# Sheet1.net
KiCad netlist of a schematic drawn in Altium Designer
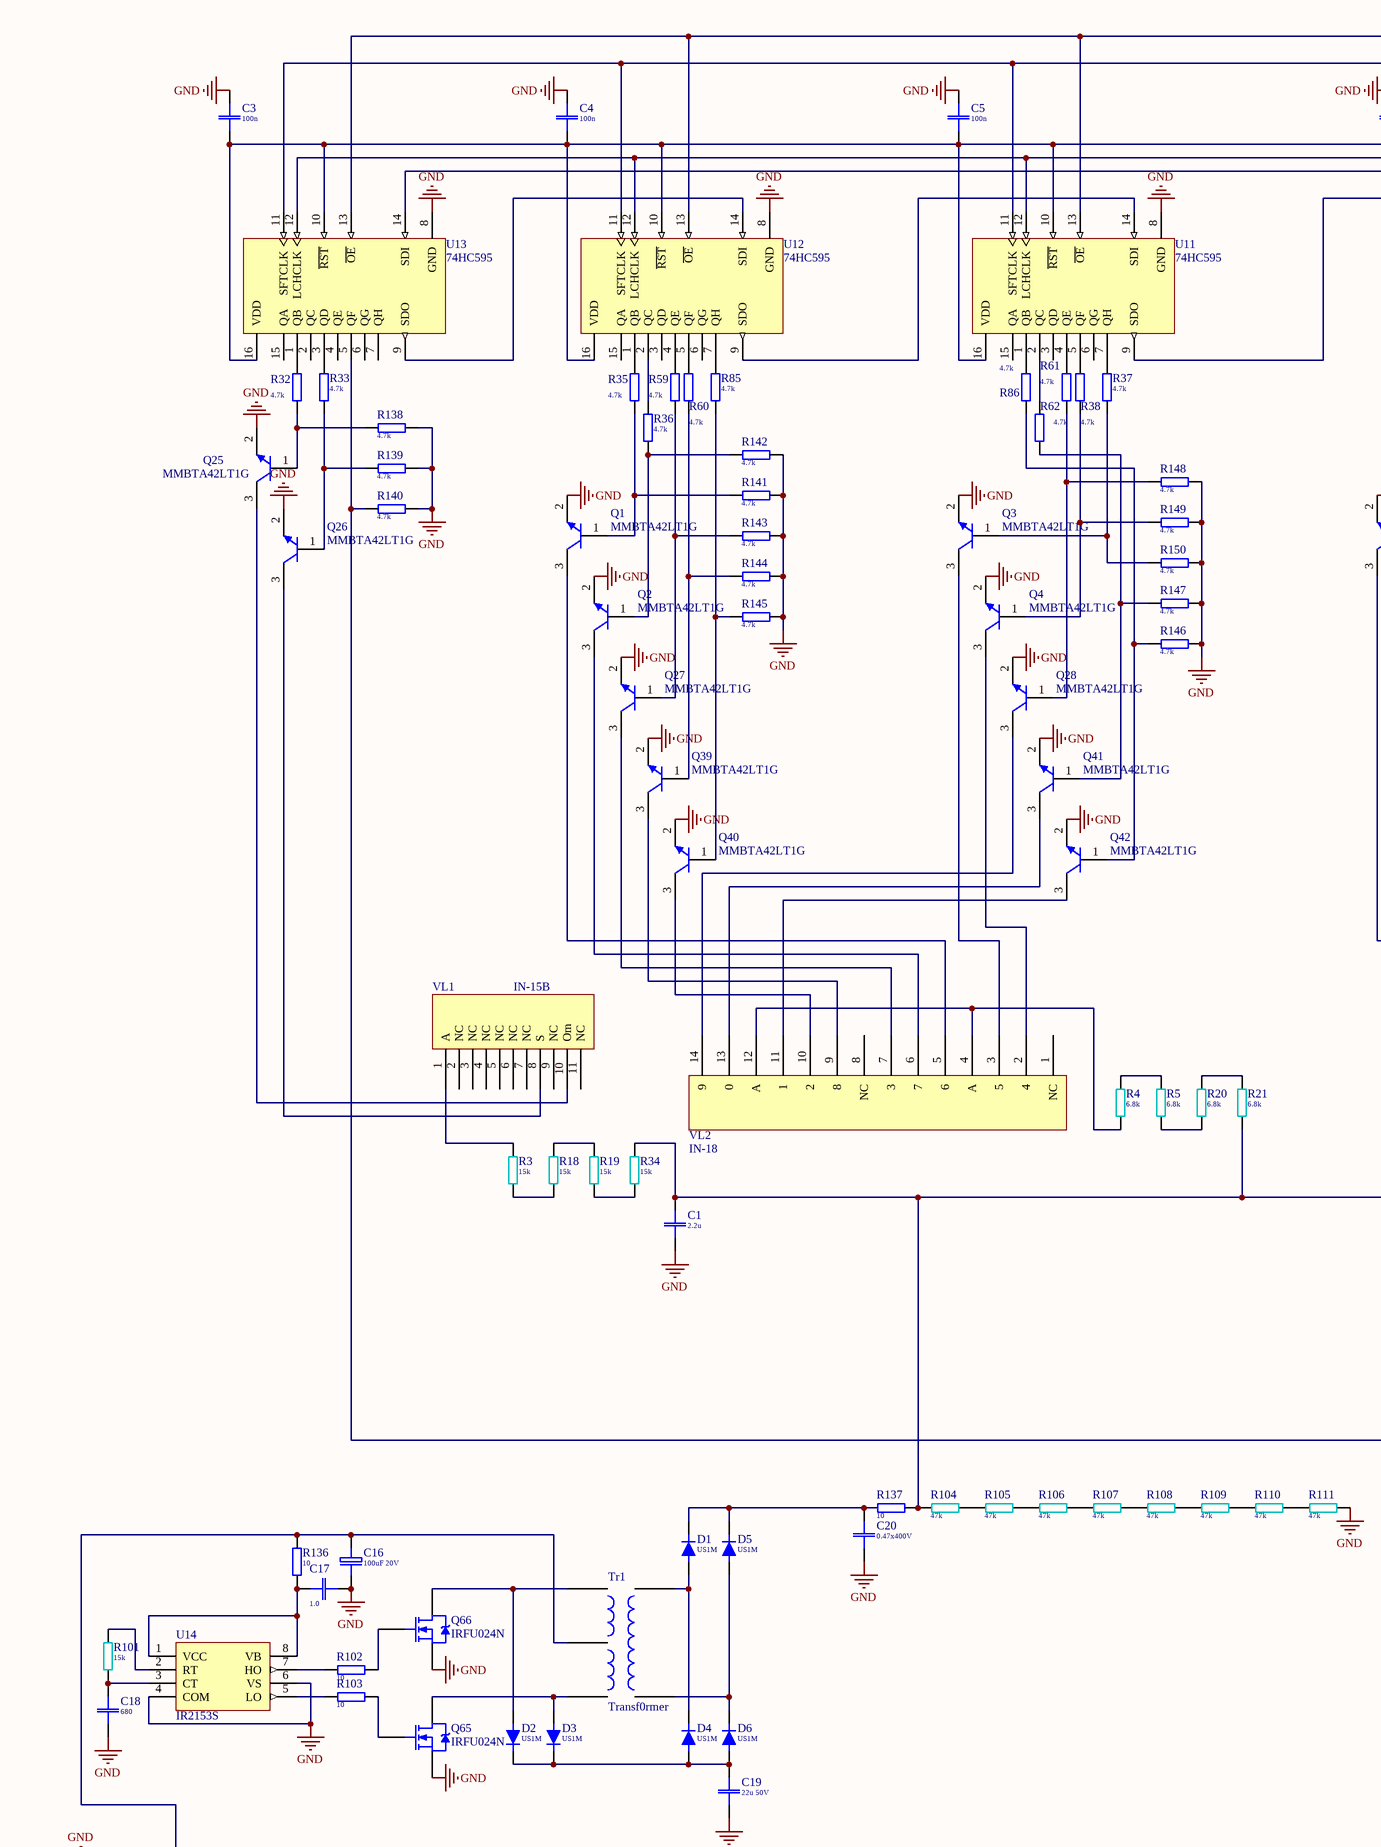
[diagram p0: Sheet1.SchDoc, top left]
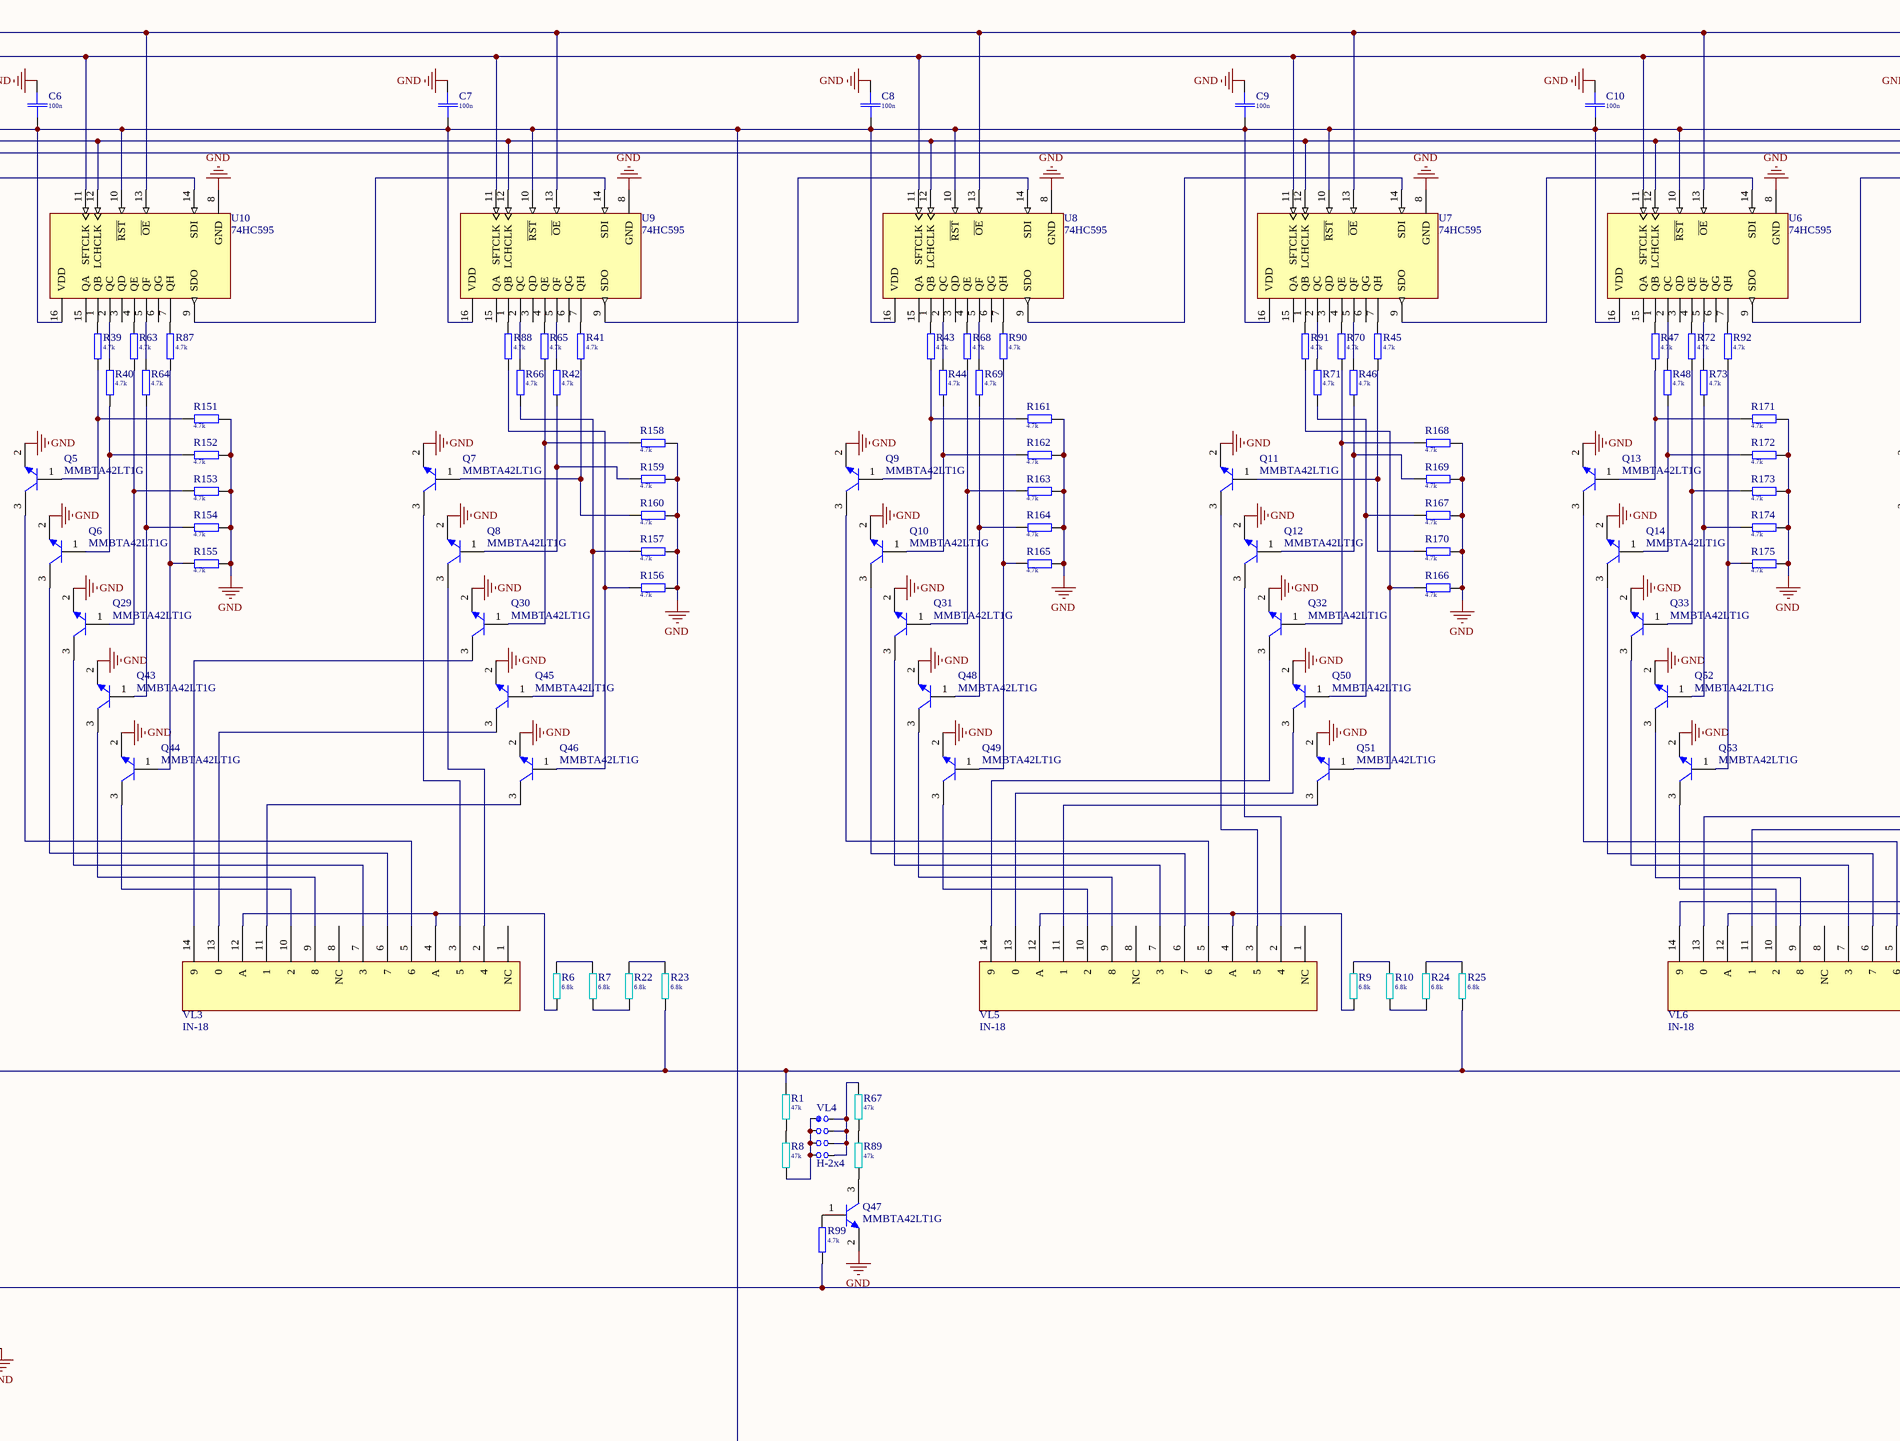
[diagram p1: Sheet1.SchDoc, top middle]
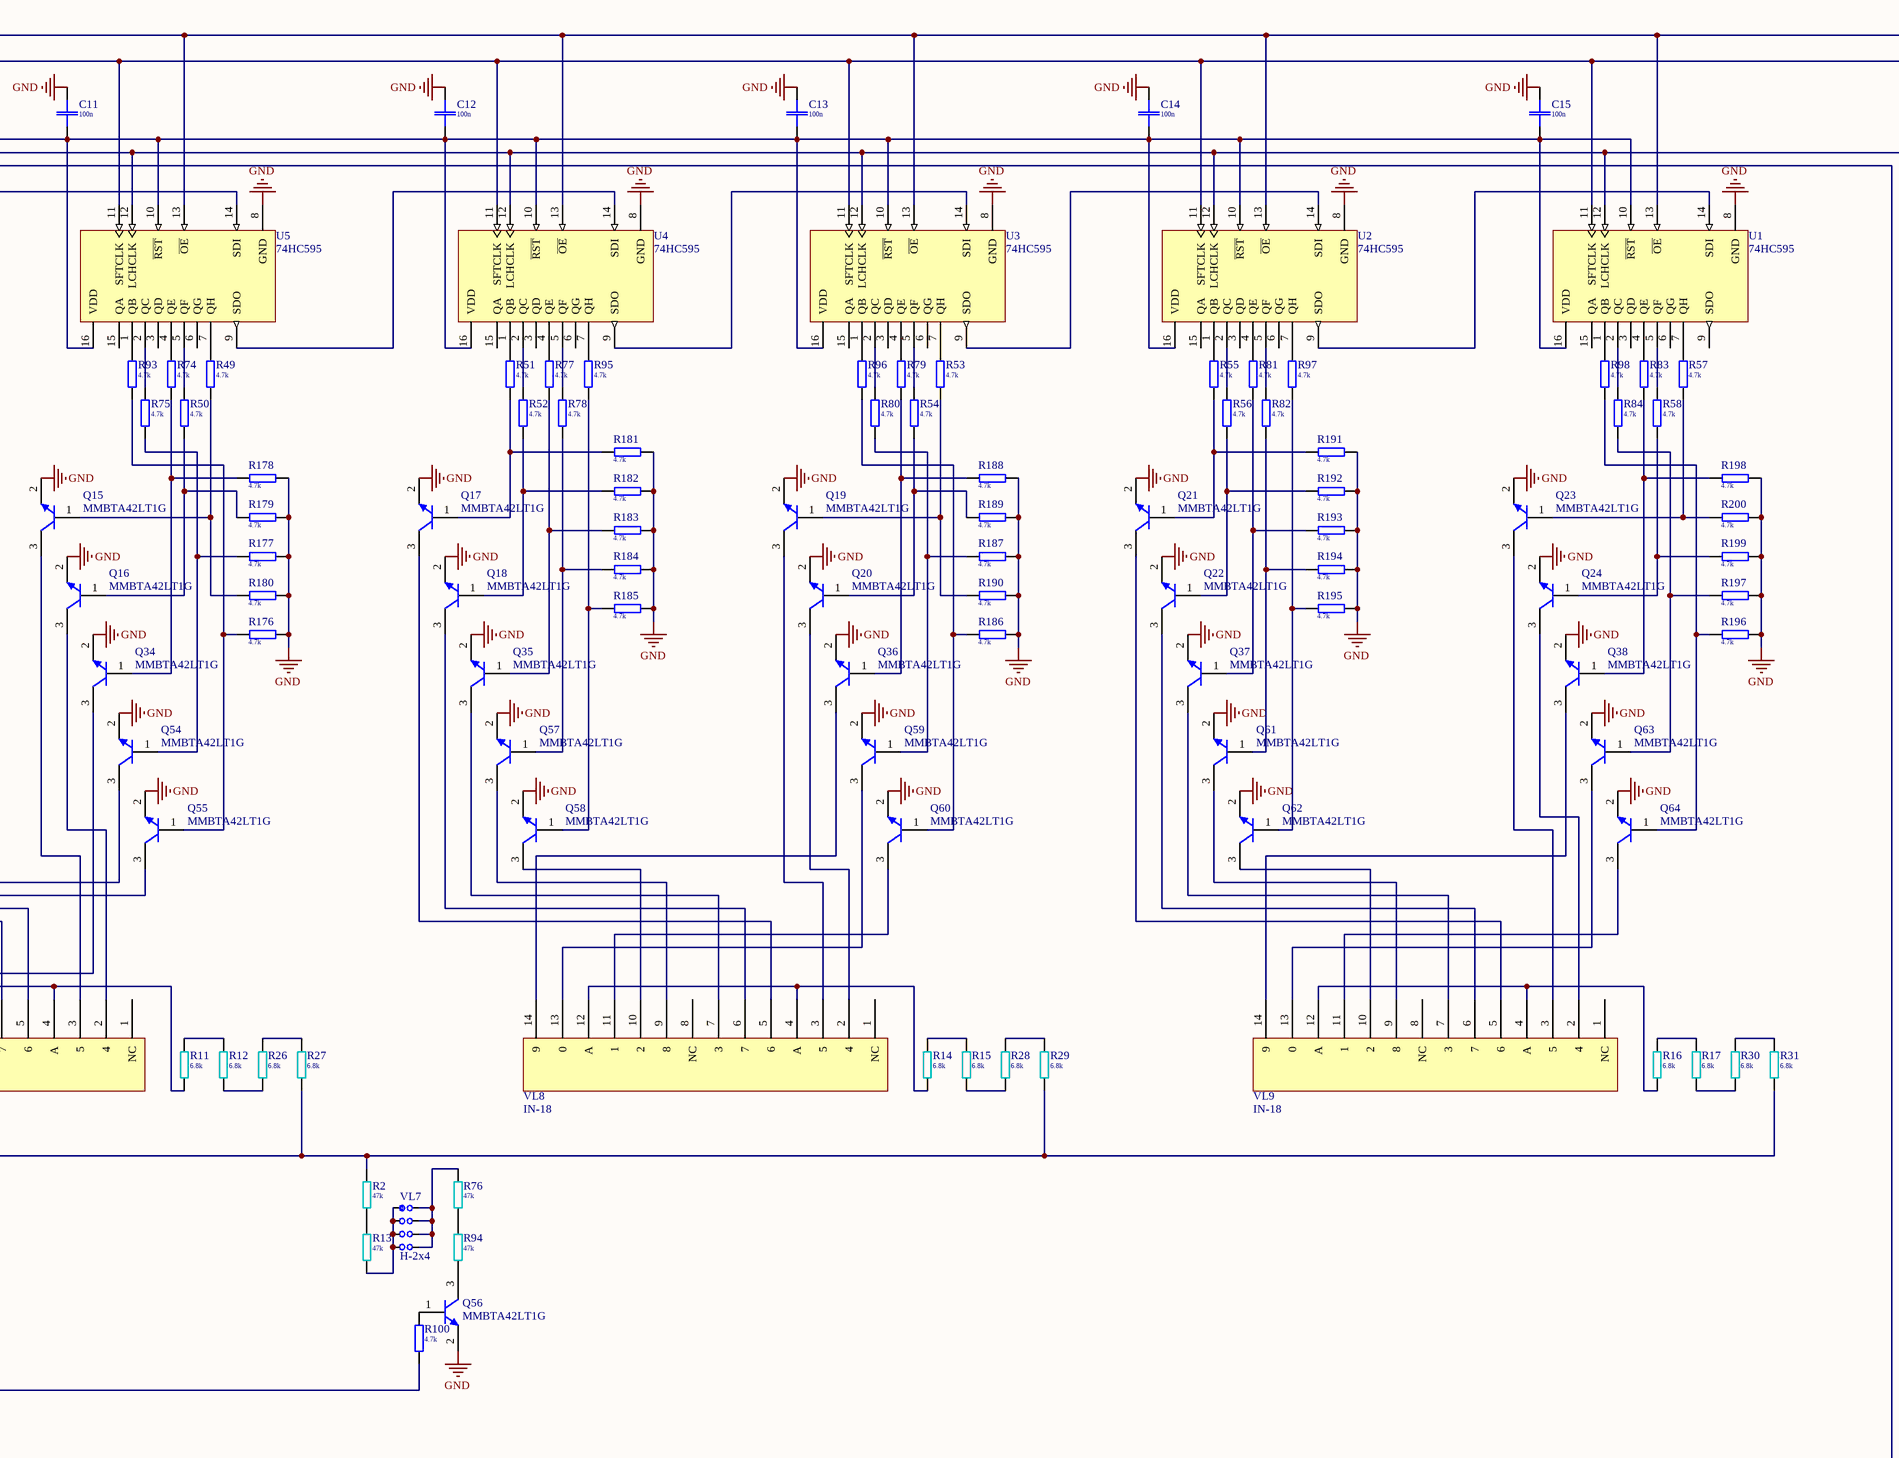
[diagram p2: Sheet1.SchDoc, top right]
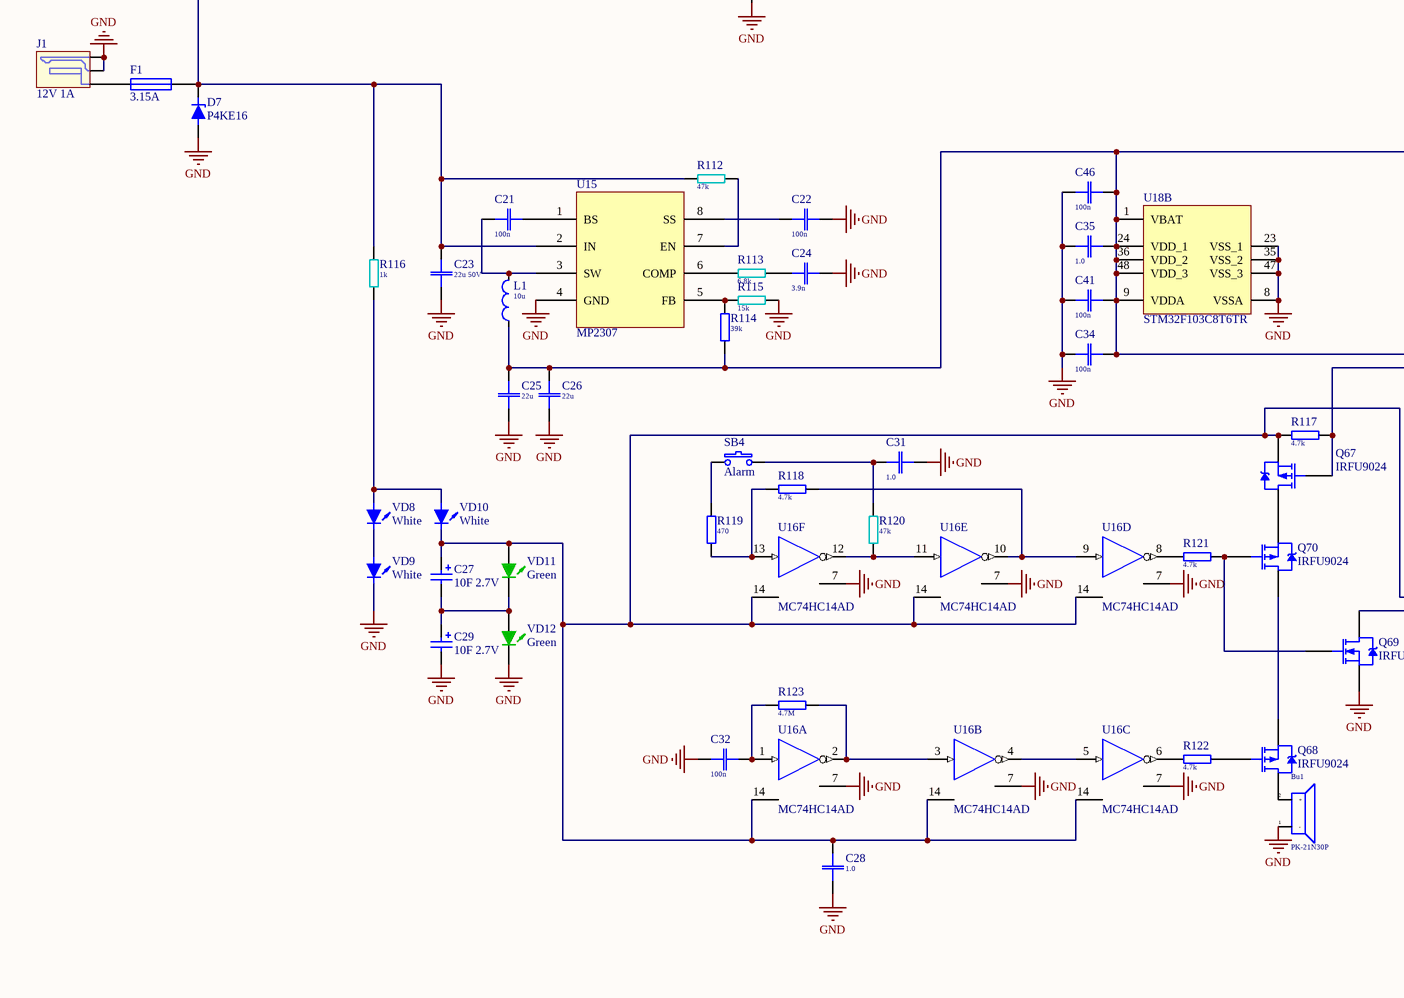
[diagram p3: Sheet1.SchDoc, bottom left]
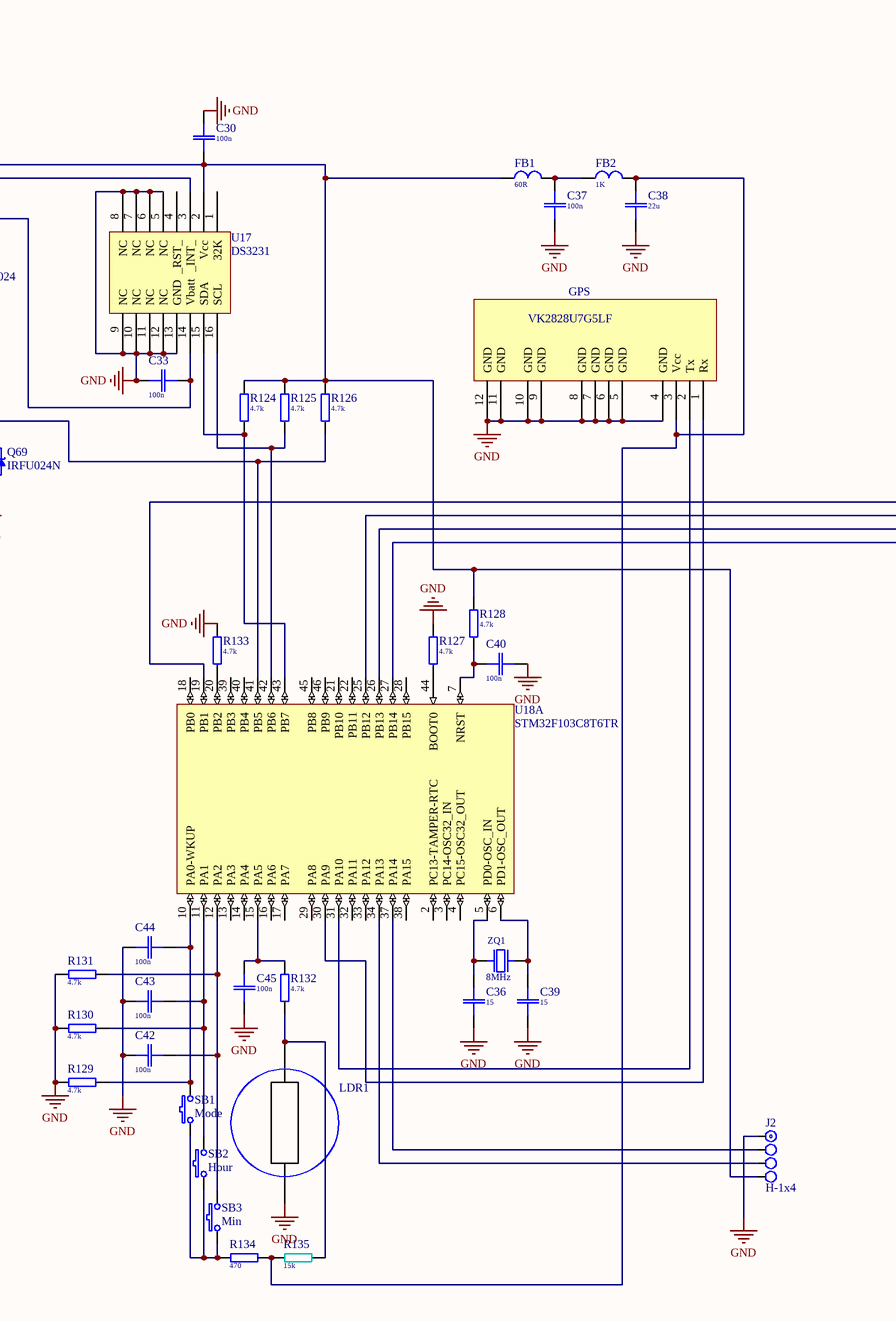
[diagram p4: Sheet1.SchDoc, bottom middle]

(export (version "E")
  (design (tool "Eeschema 10.0.6"))
  (components
    (comp (ref "Bu1")
      (value "PK-21N30P")
      (footprint "Buzzer")
      (libsource (lib "PCB_Project_4") (part "Buz PK-21N30P"))
    )
    (comp (ref "C1")
      (value "2.2u")
      (footprint "CBB22")
      (description "MER 1uF 250V")
      (libsource (lib "PCB_Project_2") (part "MER 1uF 250V"))
    )
    (comp (ref "C3")
      (value "100n")
      (footprint "C0805(2013)")
      (description "SMD-0805")
      (libsource (lib "SMD-RCL") (part "C-0805"))
    )
    (comp (ref "C4")
      (value "100n")
      (footprint "C0805(2013)")
      (description "SMD-0805")
      (libsource (lib "SMD-RCL") (part "C-0805"))
    )
    (comp (ref "C5")
      (value "100n")
      (footprint "C0805(2013)")
      (description "SMD-0805")
      (libsource (lib "SMD-RCL") (part "C-0805"))
    )
    (comp (ref "C6")
      (value "100n")
      (footprint "C0805(2013)")
      (description "SMD-0805")
      (libsource (lib "SMD-RCL") (part "C-0805"))
    )
    (comp (ref "C7")
      (value "100n")
      (footprint "C0805(2013)")
      (description "SMD-0805")
      (libsource (lib "SMD-RCL") (part "C-0805"))
    )
    (comp (ref "C8")
      (value "100n")
      (footprint "C0805(2013)")
      (description "SMD-0805")
      (libsource (lib "SMD-RCL") (part "C-0805"))
    )
    (comp (ref "C9")
      (value "100n")
      (footprint "C0805(2013)")
      (description "SMD-0805")
      (libsource (lib "SMD-RCL") (part "C-0805"))
    )
    (comp (ref "C10")
      (value "100n")
      (footprint "C0805(2013)")
      (description "SMD-0805")
      (libsource (lib "SMD-RCL") (part "C-0805"))
    )
    (comp (ref "C11")
      (value "100n")
      (footprint "C0805(2013)")
      (description "SMD-0805")
      (libsource (lib "SMD-RCL") (part "C-0805"))
    )
    (comp (ref "C12")
      (value "100n")
      (footprint "C0805(2013)")
      (description "SMD-0805")
      (libsource (lib "SMD-RCL") (part "C-0805"))
    )
    (comp (ref "C13")
      (value "100n")
      (footprint "C0805(2013)")
      (description "SMD-0805")
      (libsource (lib "SMD-RCL") (part "C-0805"))
    )
    (comp (ref "C14")
      (value "100n")
      (footprint "C0805(2013)")
      (description "SMD-0805")
      (libsource (lib "SMD-RCL") (part "C-0805"))
    )
    (comp (ref "C15")
      (value "100n")
      (footprint "C0805(2013)")
      (description "SMD-0805")
      (libsource (lib "SMD-RCL") (part "C-0805"))
    )
    (comp (ref "C16")
      (value "100uF 20V")
      (footprint "100.0x20V pol")
      (description "400V 105F")
      (libsource (lib "Cap-El") (part "1u-400V-105F"))
    )
    (comp (ref "C17")
      (value "1.0")
      (footprint "C0805(2013)")
      (description "SMD-0805")
      (libsource (lib "SMD-RCL") (part "C-0805"))
    )
    (comp (ref "C18")
      (value "680")
      (footprint "C0805(2013)")
      (description "SMD-0805")
      (libsource (lib "SMD-RCL") (part "C-0805"))
    )
    (comp (ref "C19")
      (value "22u 50V")
      (footprint "C1210(3225)")
      (description "SMD-1210 100V X7R 10%")
      (libsource (lib "SMD-RCL") (part "C-1210  100V 2.2u"))
    )
    (comp (ref "C20")
      (value "0.47x400V")
      (footprint "MKP 18x7 h14 R15.24")
      (description "MKS4 3.3u 63V")
      (fields (field (name "Comment") "3,3u"))
      (libsource (lib "Cap") (part "MKS4 3.3u 63V"))
    )
    (comp (ref "C21")
      (value "100n")
      (footprint "C0805(2013)")
      (description "SMD-0805")
      (libsource (lib "SMD-RCL") (part "C-0805"))
    )
    (comp (ref "C22")
      (value "100n")
      (footprint "C0805(2013)")
      (description "SMD-0805")
      (libsource (lib "SMD-RCL") (part "C-0805"))
    )
    (comp (ref "C23")
      (value "22u 50V")
      (footprint "C1210(3225)")
      (description "SMD-1210 100V X7R 10%")
      (libsource (lib "SMD-RCL") (part "C-1210  100V 2.2u"))
    )
    (comp (ref "C24")
      (value "3.9n")
      (footprint "C0805(2013)")
      (description "SMD-0805")
      (libsource (lib "SMD-RCL") (part "C-0805"))
    )
    (comp (ref "C25")
      (value "22u")
      (footprint "C1210(3225)")
      (description "SMD-1210 100V X7R 10%")
      (libsource (lib "SMD-RCL") (part "C-1210  100V 2.2u"))
    )
    (comp (ref "C26")
      (value "22u")
      (footprint "C1210(3225)")
      (description "SMD-1210 100V X7R 10%")
      (libsource (lib "SMD-RCL") (part "C-1210  100V 2.2u"))
    )
    (comp (ref "C27")
      (value "10F 2.7V")
      (footprint "10F2.7V")
      (description "Polarized Capacitor (Axial)")
      (fields (field (name "Comment") "Cap Pol2") (field (name "PUBLISHER") "Altium Limited"))
      (libsource (lib "Miscellaneous Devices") (part "Cap Pol2"))
    )
    (comp (ref "C28")
      (value "1.0")
      (footprint "C0805(2013)")
      (description "SMD-0805")
      (libsource (lib "SMD-RCL") (part "C-0805"))
    )
    (comp (ref "C29")
      (value "10F 2.7V")
      (footprint "10F2.7V")
      (description "Polarized Capacitor (Axial)")
      (fields (field (name "Comment") "Cap Pol2") (field (name "PUBLISHER") "Altium Limited"))
      (libsource (lib "Miscellaneous Devices") (part "Cap Pol2"))
    )
    (comp (ref "C30")
      (value "100n")
      (footprint "C0805(2013)")
      (description "SMD-0805")
      (libsource (lib "SMD-RCL") (part "C-0805"))
    )
    (comp (ref "C31")
      (value "1.0")
      (footprint "C0805(2013)")
      (description "SMD-0805")
      (libsource (lib "SMD-RCL") (part "C-0805"))
    )
    (comp (ref "C32")
      (value "100n")
      (footprint "C0805(2013)")
      (description "SMD-0805")
      (libsource (lib "SMD-RCL") (part "C-0805"))
    )
    (comp (ref "C33")
      (value "100n")
      (footprint "C0805(2013)")
      (description "SMD-0805")
      (libsource (lib "SMD-RCL") (part "C-0805"))
    )
    (comp (ref "C34")
      (value "100n")
      (footprint "C0805(2013)")
      (description "SMD-0805")
      (libsource (lib "SMD-RCL") (part "C-0805"))
    )
    (comp (ref "C35")
      (value "1.0")
      (footprint "C0805(2013)")
      (description "SMD-0805")
      (libsource (lib "SMD-RCL") (part "C-0805"))
    )
    (comp (ref "C36")
      (value "15")
      (footprint "C0805(2013)")
      (description "SMD-0805")
      (libsource (lib "SMD-RCL") (part "C-0805"))
    )
    (comp (ref "C37")
      (value "100n")
      (footprint "C0805(2013)")
      (description "SMD-0805")
      (libsource (lib "SMD-RCL") (part "C-0805"))
    )
    (comp (ref "C38")
      (value "22u")
      (footprint "C1210(3225)")
      (description "SMD-1210 100V X7R 10%")
      (libsource (lib "SMD-RCL") (part "C-1210  100V 2.2u"))
    )
    (comp (ref "C39")
      (value "15")
      (footprint "C0805(2013)")
      (description "SMD-0805")
      (libsource (lib "SMD-RCL") (part "C-0805"))
    )
    (comp (ref "C40")
      (value "100n")
      (footprint "C0805(2013)")
      (description "SMD-0805")
      (libsource (lib "SMD-RCL") (part "C-0805"))
    )
    (comp (ref "C41")
      (value "100n")
      (footprint "C0805(2013)")
      (description "SMD-0805")
      (libsource (lib "SMD-RCL") (part "C-0805"))
    )
    (comp (ref "C42")
      (value "100n")
      (footprint "C0805(2013)")
      (description "SMD-0805")
      (libsource (lib "SMD-RCL") (part "C-0805"))
    )
    (comp (ref "C43")
      (value "100n")
      (footprint "C0805(2013)")
      (description "SMD-0805")
      (libsource (lib "SMD-RCL") (part "C-0805"))
    )
    (comp (ref "C44")
      (value "100n")
      (footprint "C0805(2013)")
      (description "SMD-0805")
      (libsource (lib "SMD-RCL") (part "C-0805"))
    )
    (comp (ref "C45")
      (value "100n")
      (footprint "C0805(2013)")
      (description "SMD-0805")
      (libsource (lib "SMD-RCL") (part "C-0805"))
    )
    (comp (ref "C46")
      (value "100n")
      (footprint "C0805(2013)")
      (description "SMD-0805")
      (libsource (lib "SMD-RCL") (part "C-0805"))
    )
    (comp (ref "D1")
      (value "US1M")
      (footprint "DO-214AC (SMA)")
      (description "SMD SMA 1A 1000V 75nS")
      (libsource (lib "Diodes-Power") (part "US1M"))
    )
    (comp (ref "D2")
      (value "US1M")
      (footprint "DO-214AC (SMA)")
      (description "SMD SMA 1A 1000V 75nS")
      (libsource (lib "Diodes-Power") (part "US1M"))
    )
    (comp (ref "D3")
      (value "US1M")
      (footprint "DO-214AC (SMA)")
      (description "SMD SMA 1A 1000V 75nS")
      (libsource (lib "Diodes-Power") (part "US1M"))
    )
    (comp (ref "D4")
      (value "US1M")
      (footprint "DO-214AC (SMA)")
      (description "SMD SMA 1A 1000V 75nS")
      (libsource (lib "Diodes-Power") (part "US1M"))
    )
    (comp (ref "D5")
      (value "US1M")
      (footprint "DO-214AC (SMA)")
      (description "SMD SMA 1A 1000V 75nS")
      (libsource (lib "Diodes-Power") (part "US1M"))
    )
    (comp (ref "D6")
      (value "US1M")
      (footprint "DO-214AC (SMA)")
      (description "SMD SMA 1A 1000V 75nS")
      (libsource (lib "Diodes-Power") (part "US1M"))
    )
    (comp (ref "D7")
      (value "P4KE16")
      (footprint "DO-15-400")
      (description "TVS DO-15 600W 200V")
      (libsource (lib "Diodes") (part "P6KE200"))
    )
    (comp (ref "F1")
      (value "3.15A")
      (footprint "PIN-W2/E2.8")
      (description "Fuse")
      (fields (field (name "PUBLISHER") "Altium Limited"))
      (libsource (lib "Miscellaneous Devices") (part "Fuse 1"))
    )
    (comp (ref "FB1") (value "60R") (footprint "C1206") (libsource (lib "SMD-RCL") (part "L2")))
    (comp (ref "FB2") (value "1K") (footprint "C1206") (libsource (lib "SMD-RCL") (part "L2")))
    (comp (ref "GPS")
      (value "VK2828U7G5LF")
      (footprint "GPSmodule")
      (description "Amt02 GPS antenna")
      (libsource (lib "PCB_Project_4") (part "GPS_ant"))
    )
    (comp (ref "J1")
      (value "12V 1A")
      (footprint "Power-Jack")
      (description "Power-Jack")
      (libsource (lib "Connektor") (part "Power-Jack"))
    )
    (comp (ref "J2") (value "H-1x4") (footprint "J1x4") (libsource (lib "Connektor") (part "H-1x4")))
    (comp (ref "L1")
      (value "10u")
      (footprint "Dr-SD-75")
      (description "1.2A 0.15om 7.3x7.3x5mm")
      (libsource (lib "SMD-RCL") (part "L-SD-75 33uH"))
    )
    (comp (ref "LDR1")
      (value "LDR")
      (footprint "CAPPR250-630X1120")
      (libsource (lib "PCB_Project_2") (part "LDR"))
    )
    (comp (ref "Q1")
      (value "MMBTA42LT1G")
      (footprint "ONSC-SOT-23-3-318-08_V")
      (description "High Voltage Transistor, NPN Silicon, 3-Pin SOT-23, Pb-Free, Tape and Reel")
      (fields (field (name "MANUFACTURER") "On Semiconductor"))
      (libsource (lib "ON Semi General Purpose Transistors") (part "MMBTA42LT1G"))
    )
    (comp (ref "Q2")
      (value "MMBTA42LT1G")
      (footprint "ONSC-SOT-23-3-318-08_V")
      (description "High Voltage Transistor, NPN Silicon, 3-Pin SOT-23, Pb-Free, Tape and Reel")
      (fields (field (name "MANUFACTURER") "On Semiconductor"))
      (libsource (lib "ON Semi General Purpose Transistors") (part "MMBTA42LT1G"))
    )
    (comp (ref "Q3")
      (value "MMBTA42LT1G")
      (footprint "ONSC-SOT-23-3-318-08_V")
      (description "High Voltage Transistor, NPN Silicon, 3-Pin SOT-23, Pb-Free, Tape and Reel")
      (fields (field (name "MANUFACTURER") "On Semiconductor"))
      (libsource (lib "ON Semi General Purpose Transistors") (part "MMBTA42LT1G"))
    )
    (comp (ref "Q4")
      (value "MMBTA42LT1G")
      (footprint "ONSC-SOT-23-3-318-08_V")
      (description "High Voltage Transistor, NPN Silicon, 3-Pin SOT-23, Pb-Free, Tape and Reel")
      (fields (field (name "MANUFACTURER") "On Semiconductor"))
      (libsource (lib "ON Semi General Purpose Transistors") (part "MMBTA42LT1G"))
    )
    (comp (ref "Q5")
      (value "MMBTA42LT1G")
      (footprint "ONSC-SOT-23-3-318-08_V")
      (description "High Voltage Transistor, NPN Silicon, 3-Pin SOT-23, Pb-Free, Tape and Reel")
      (fields (field (name "MANUFACTURER") "On Semiconductor"))
      (libsource (lib "ON Semi General Purpose Transistors") (part "MMBTA42LT1G"))
    )
    (comp (ref "Q6")
      (value "MMBTA42LT1G")
      (footprint "ONSC-SOT-23-3-318-08_V")
      (description "High Voltage Transistor, NPN Silicon, 3-Pin SOT-23, Pb-Free, Tape and Reel")
      (fields (field (name "MANUFACTURER") "On Semiconductor"))
      (libsource (lib "ON Semi General Purpose Transistors") (part "MMBTA42LT1G"))
    )
    (comp (ref "Q7")
      (value "MMBTA42LT1G")
      (footprint "ONSC-SOT-23-3-318-08_V")
      (description "High Voltage Transistor, NPN Silicon, 3-Pin SOT-23, Pb-Free, Tape and Reel")
      (fields (field (name "MANUFACTURER") "On Semiconductor"))
      (libsource (lib "ON Semi General Purpose Transistors") (part "MMBTA42LT1G"))
    )
    (comp (ref "Q8")
      (value "MMBTA42LT1G")
      (footprint "ONSC-SOT-23-3-318-08_V")
      (description "High Voltage Transistor, NPN Silicon, 3-Pin SOT-23, Pb-Free, Tape and Reel")
      (fields (field (name "MANUFACTURER") "On Semiconductor"))
      (libsource (lib "ON Semi General Purpose Transistors") (part "MMBTA42LT1G"))
    )
    (comp (ref "Q9")
      (value "MMBTA42LT1G")
      (footprint "ONSC-SOT-23-3-318-08_V")
      (description "High Voltage Transistor, NPN Silicon, 3-Pin SOT-23, Pb-Free, Tape and Reel")
      (fields (field (name "MANUFACTURER") "On Semiconductor"))
      (libsource (lib "ON Semi General Purpose Transistors") (part "MMBTA42LT1G"))
    )
    (comp (ref "Q10")
      (value "MMBTA42LT1G")
      (footprint "ONSC-SOT-23-3-318-08_V")
      (description "High Voltage Transistor, NPN Silicon, 3-Pin SOT-23, Pb-Free, Tape and Reel")
      (fields (field (name "MANUFACTURER") "On Semiconductor"))
      (libsource (lib "ON Semi General Purpose Transistors") (part "MMBTA42LT1G"))
    )
    (comp (ref "Q11")
      (value "MMBTA42LT1G")
      (footprint "ONSC-SOT-23-3-318-08_V")
      (description "High Voltage Transistor, NPN Silicon, 3-Pin SOT-23, Pb-Free, Tape and Reel")
      (fields (field (name "MANUFACTURER") "On Semiconductor"))
      (libsource (lib "ON Semi General Purpose Transistors") (part "MMBTA42LT1G"))
    )
    (comp (ref "Q12")
      (value "MMBTA42LT1G")
      (footprint "ONSC-SOT-23-3-318-08_V")
      (description "High Voltage Transistor, NPN Silicon, 3-Pin SOT-23, Pb-Free, Tape and Reel")
      (fields (field (name "MANUFACTURER") "On Semiconductor"))
      (libsource (lib "ON Semi General Purpose Transistors") (part "MMBTA42LT1G"))
    )
    (comp (ref "Q13")
      (value "MMBTA42LT1G")
      (footprint "ONSC-SOT-23-3-318-08_V")
      (description "High Voltage Transistor, NPN Silicon, 3-Pin SOT-23, Pb-Free, Tape and Reel")
      (fields (field (name "MANUFACTURER") "On Semiconductor"))
      (libsource (lib "ON Semi General Purpose Transistors") (part "MMBTA42LT1G"))
    )
    (comp (ref "Q14")
      (value "MMBTA42LT1G")
      (footprint "ONSC-SOT-23-3-318-08_V")
      (description "High Voltage Transistor, NPN Silicon, 3-Pin SOT-23, Pb-Free, Tape and Reel")
      (fields (field (name "MANUFACTURER") "On Semiconductor"))
      (libsource (lib "ON Semi General Purpose Transistors") (part "MMBTA42LT1G"))
    )
    (comp (ref "Q15")
      (value "MMBTA42LT1G")
      (footprint "ONSC-SOT-23-3-318-08_V")
      (description "High Voltage Transistor, NPN Silicon, 3-Pin SOT-23, Pb-Free, Tape and Reel")
      (fields (field (name "MANUFACTURER") "On Semiconductor"))
      (libsource (lib "ON Semi General Purpose Transistors") (part "MMBTA42LT1G"))
    )
    (comp (ref "Q16")
      (value "MMBTA42LT1G")
      (footprint "ONSC-SOT-23-3-318-08_V")
      (description "High Voltage Transistor, NPN Silicon, 3-Pin SOT-23, Pb-Free, Tape and Reel")
      (fields (field (name "MANUFACTURER") "On Semiconductor"))
      (libsource (lib "ON Semi General Purpose Transistors") (part "MMBTA42LT1G"))
    )
    (comp (ref "Q17")
      (value "MMBTA42LT1G")
      (footprint "ONSC-SOT-23-3-318-08_V")
      (description "High Voltage Transistor, NPN Silicon, 3-Pin SOT-23, Pb-Free, Tape and Reel")
      (fields (field (name "MANUFACTURER") "On Semiconductor"))
      (libsource (lib "ON Semi General Purpose Transistors") (part "MMBTA42LT1G"))
    )
    (comp (ref "Q18")
      (value "MMBTA42LT1G")
      (footprint "ONSC-SOT-23-3-318-08_V")
      (description "High Voltage Transistor, NPN Silicon, 3-Pin SOT-23, Pb-Free, Tape and Reel")
      (fields (field (name "MANUFACTURER") "On Semiconductor"))
      (libsource (lib "ON Semi General Purpose Transistors") (part "MMBTA42LT1G"))
    )
    (comp (ref "Q19")
      (value "MMBTA42LT1G")
      (footprint "ONSC-SOT-23-3-318-08_V")
      (description "High Voltage Transistor, NPN Silicon, 3-Pin SOT-23, Pb-Free, Tape and Reel")
      (fields (field (name "MANUFACTURER") "On Semiconductor"))
      (libsource (lib "ON Semi General Purpose Transistors") (part "MMBTA42LT1G"))
    )
    (comp (ref "Q20")
      (value "MMBTA42LT1G")
      (footprint "ONSC-SOT-23-3-318-08_V")
      (description "High Voltage Transistor, NPN Silicon, 3-Pin SOT-23, Pb-Free, Tape and Reel")
      (fields (field (name "MANUFACTURER") "On Semiconductor"))
      (libsource (lib "ON Semi General Purpose Transistors") (part "MMBTA42LT1G"))
    )
    (comp (ref "Q21")
      (value "MMBTA42LT1G")
      (footprint "ONSC-SOT-23-3-318-08_V")
      (description "High Voltage Transistor, NPN Silicon, 3-Pin SOT-23, Pb-Free, Tape and Reel")
      (fields (field (name "MANUFACTURER") "On Semiconductor"))
      (libsource (lib "ON Semi General Purpose Transistors") (part "MMBTA42LT1G"))
    )
    (comp (ref "Q22")
      (value "MMBTA42LT1G")
      (footprint "ONSC-SOT-23-3-318-08_V")
      (description "High Voltage Transistor, NPN Silicon, 3-Pin SOT-23, Pb-Free, Tape and Reel")
      (fields (field (name "MANUFACTURER") "On Semiconductor"))
      (libsource (lib "ON Semi General Purpose Transistors") (part "MMBTA42LT1G"))
    )
    (comp (ref "Q23")
      (value "MMBTA42LT1G")
      (footprint "ONSC-SOT-23-3-318-08_V")
      (description "High Voltage Transistor, NPN Silicon, 3-Pin SOT-23, Pb-Free, Tape and Reel")
      (fields (field (name "MANUFACTURER") "On Semiconductor"))
      (libsource (lib "ON Semi General Purpose Transistors") (part "MMBTA42LT1G"))
    )
    (comp (ref "Q24")
      (value "MMBTA42LT1G")
      (footprint "ONSC-SOT-23-3-318-08_V")
      (description "High Voltage Transistor, NPN Silicon, 3-Pin SOT-23, Pb-Free, Tape and Reel")
      (fields (field (name "MANUFACTURER") "On Semiconductor"))
      (libsource (lib "ON Semi General Purpose Transistors") (part "MMBTA42LT1G"))
    )
    (comp (ref "Q25")
      (value "MMBTA42LT1G")
      (footprint "ONSC-SOT-23-3-318-08_V")
      (description "High Voltage Transistor, NPN Silicon, 3-Pin SOT-23, Pb-Free, Tape and Reel")
      (fields (field (name "MANUFACTURER") "On Semiconductor"))
      (libsource (lib "ON Semi General Purpose Transistors") (part "MMBTA42LT1G"))
    )
    (comp (ref "Q26")
      (value "MMBTA42LT1G")
      (footprint "ONSC-SOT-23-3-318-08_V")
      (description "High Voltage Transistor, NPN Silicon, 3-Pin SOT-23, Pb-Free, Tape and Reel")
      (fields (field (name "MANUFACTURER") "On Semiconductor"))
      (libsource (lib "ON Semi General Purpose Transistors") (part "MMBTA42LT1G"))
    )
    (comp (ref "Q27")
      (value "MMBTA42LT1G")
      (footprint "ONSC-SOT-23-3-318-08_V")
      (description "High Voltage Transistor, NPN Silicon, 3-Pin SOT-23, Pb-Free, Tape and Reel")
      (fields (field (name "MANUFACTURER") "On Semiconductor"))
      (libsource (lib "ON Semi General Purpose Transistors") (part "MMBTA42LT1G"))
    )
    (comp (ref "Q28")
      (value "MMBTA42LT1G")
      (footprint "ONSC-SOT-23-3-318-08_V")
      (description "High Voltage Transistor, NPN Silicon, 3-Pin SOT-23, Pb-Free, Tape and Reel")
      (fields (field (name "MANUFACTURER") "On Semiconductor"))
      (libsource (lib "ON Semi General Purpose Transistors") (part "MMBTA42LT1G"))
    )
    (comp (ref "Q29")
      (value "MMBTA42LT1G")
      (footprint "ONSC-SOT-23-3-318-08_V")
      (description "High Voltage Transistor, NPN Silicon, 3-Pin SOT-23, Pb-Free, Tape and Reel")
      (fields (field (name "MANUFACTURER") "On Semiconductor"))
      (libsource (lib "ON Semi General Purpose Transistors") (part "MMBTA42LT1G"))
    )
    (comp (ref "Q30")
      (value "MMBTA42LT1G")
      (footprint "ONSC-SOT-23-3-318-08_V")
      (description "High Voltage Transistor, NPN Silicon, 3-Pin SOT-23, Pb-Free, Tape and Reel")
      (fields (field (name "MANUFACTURER") "On Semiconductor"))
      (libsource (lib "ON Semi General Purpose Transistors") (part "MMBTA42LT1G"))
    )
    (comp (ref "Q31")
      (value "MMBTA42LT1G")
      (footprint "ONSC-SOT-23-3-318-08_V")
      (description "High Voltage Transistor, NPN Silicon, 3-Pin SOT-23, Pb-Free, Tape and Reel")
      (fields (field (name "MANUFACTURER") "On Semiconductor"))
      (libsource (lib "ON Semi General Purpose Transistors") (part "MMBTA42LT1G"))
    )
    (comp (ref "Q32")
      (value "MMBTA42LT1G")
      (footprint "ONSC-SOT-23-3-318-08_V")
      (description "High Voltage Transistor, NPN Silicon, 3-Pin SOT-23, Pb-Free, Tape and Reel")
      (fields (field (name "MANUFACTURER") "On Semiconductor"))
      (libsource (lib "ON Semi General Purpose Transistors") (part "MMBTA42LT1G"))
    )
    (comp (ref "Q33")
      (value "MMBTA42LT1G")
      (footprint "ONSC-SOT-23-3-318-08_V")
      (description "High Voltage Transistor, NPN Silicon, 3-Pin SOT-23, Pb-Free, Tape and Reel")
      (fields (field (name "MANUFACTURER") "On Semiconductor"))
      (libsource (lib "ON Semi General Purpose Transistors") (part "MMBTA42LT1G"))
    )
    (comp (ref "Q34")
      (value "MMBTA42LT1G")
      (footprint "ONSC-SOT-23-3-318-08_V")
      (description "High Voltage Transistor, NPN Silicon, 3-Pin SOT-23, Pb-Free, Tape and Reel")
      (fields (field (name "MANUFACTURER") "On Semiconductor"))
      (libsource (lib "ON Semi General Purpose Transistors") (part "MMBTA42LT1G"))
    )
    (comp (ref "Q35")
      (value "MMBTA42LT1G")
      (footprint "ONSC-SOT-23-3-318-08_V")
      (description "High Voltage Transistor, NPN Silicon, 3-Pin SOT-23, Pb-Free, Tape and Reel")
      (fields (field (name "MANUFACTURER") "On Semiconductor"))
      (libsource (lib "ON Semi General Purpose Transistors") (part "MMBTA42LT1G"))
    )
    (comp (ref "Q36")
      (value "MMBTA42LT1G")
      (footprint "ONSC-SOT-23-3-318-08_V")
      (description "High Voltage Transistor, NPN Silicon, 3-Pin SOT-23, Pb-Free, Tape and Reel")
      (fields (field (name "MANUFACTURER") "On Semiconductor"))
      (libsource (lib "ON Semi General Purpose Transistors") (part "MMBTA42LT1G"))
    )
    (comp (ref "Q37")
      (value "MMBTA42LT1G")
      (footprint "ONSC-SOT-23-3-318-08_V")
      (description "High Voltage Transistor, NPN Silicon, 3-Pin SOT-23, Pb-Free, Tape and Reel")
      (fields (field (name "MANUFACTURER") "On Semiconductor"))
      (libsource (lib "ON Semi General Purpose Transistors") (part "MMBTA42LT1G"))
    )
    (comp (ref "Q38")
      (value "MMBTA42LT1G")
      (footprint "ONSC-SOT-23-3-318-08_V")
      (description "High Voltage Transistor, NPN Silicon, 3-Pin SOT-23, Pb-Free, Tape and Reel")
      (fields (field (name "MANUFACTURER") "On Semiconductor"))
      (libsource (lib "ON Semi General Purpose Transistors") (part "MMBTA42LT1G"))
    )
    (comp (ref "Q39")
      (value "MMBTA42LT1G")
      (footprint "ONSC-SOT-23-3-318-08_V")
      (description "High Voltage Transistor, NPN Silicon, 3-Pin SOT-23, Pb-Free, Tape and Reel")
      (fields (field (name "MANUFACTURER") "On Semiconductor"))
      (libsource (lib "ON Semi General Purpose Transistors") (part "MMBTA42LT1G"))
    )
    (comp (ref "Q40")
      (value "MMBTA42LT1G")
      (footprint "ONSC-SOT-23-3-318-08_V")
      (description "High Voltage Transistor, NPN Silicon, 3-Pin SOT-23, Pb-Free, Tape and Reel")
      (fields (field (name "MANUFACTURER") "On Semiconductor"))
      (libsource (lib "ON Semi General Purpose Transistors") (part "MMBTA42LT1G"))
    )
    (comp (ref "Q41")
      (value "MMBTA42LT1G")
      (footprint "ONSC-SOT-23-3-318-08_V")
      (description "High Voltage Transistor, NPN Silicon, 3-Pin SOT-23, Pb-Free, Tape and Reel")
      (fields (field (name "MANUFACTURER") "On Semiconductor"))
      (libsource (lib "ON Semi General Purpose Transistors") (part "MMBTA42LT1G"))
    )
    (comp (ref "Q42")
      (value "MMBTA42LT1G")
      (footprint "ONSC-SOT-23-3-318-08_V")
      (description "High Voltage Transistor, NPN Silicon, 3-Pin SOT-23, Pb-Free, Tape and Reel")
      (fields (field (name "MANUFACTURER") "On Semiconductor"))
      (libsource (lib "ON Semi General Purpose Transistors") (part "MMBTA42LT1G"))
    )
    (comp (ref "Q43")
      (value "MMBTA42LT1G")
      (footprint "ONSC-SOT-23-3-318-08_V")
      (description "High Voltage Transistor, NPN Silicon, 3-Pin SOT-23, Pb-Free, Tape and Reel")
      (fields (field (name "MANUFACTURER") "On Semiconductor"))
      (libsource (lib "ON Semi General Purpose Transistors") (part "MMBTA42LT1G"))
    )
    (comp (ref "Q44")
      (value "MMBTA42LT1G")
      (footprint "ONSC-SOT-23-3-318-08_V")
      (description "High Voltage Transistor, NPN Silicon, 3-Pin SOT-23, Pb-Free, Tape and Reel")
      (fields (field (name "MANUFACTURER") "On Semiconductor"))
      (libsource (lib "ON Semi General Purpose Transistors") (part "MMBTA42LT1G"))
    )
    (comp (ref "Q45")
      (value "MMBTA42LT1G")
      (footprint "ONSC-SOT-23-3-318-08_V")
      (description "High Voltage Transistor, NPN Silicon, 3-Pin SOT-23, Pb-Free, Tape and Reel")
      (fields (field (name "MANUFACTURER") "On Semiconductor"))
      (libsource (lib "ON Semi General Purpose Transistors") (part "MMBTA42LT1G"))
    )
    (comp (ref "Q46")
      (value "MMBTA42LT1G")
      (footprint "ONSC-SOT-23-3-318-08_V")
      (description "High Voltage Transistor, NPN Silicon, 3-Pin SOT-23, Pb-Free, Tape and Reel")
      (fields (field (name "MANUFACTURER") "On Semiconductor"))
      (libsource (lib "ON Semi General Purpose Transistors") (part "MMBTA42LT1G"))
    )
    (comp (ref "Q47")
      (value "MMBTA42LT1G")
      (footprint "ONSC-SOT-23-3-318-08_V")
      (description "High Voltage Transistor, NPN Silicon, 3-Pin SOT-23, Pb-Free, Tape and Reel")
      (fields (field (name "MANUFACTURER") "On Semiconductor"))
      (libsource (lib "ON Semi General Purpose Transistors") (part "MMBTA42LT1G"))
    )
    (comp (ref "Q48")
      (value "MMBTA42LT1G")
      (footprint "ONSC-SOT-23-3-318-08_V")
      (description "High Voltage Transistor, NPN Silicon, 3-Pin SOT-23, Pb-Free, Tape and Reel")
      (fields (field (name "MANUFACTURER") "On Semiconductor"))
      (libsource (lib "ON Semi General Purpose Transistors") (part "MMBTA42LT1G"))
    )
    (comp (ref "Q49")
      (value "MMBTA42LT1G")
      (footprint "ONSC-SOT-23-3-318-08_V")
      (description "High Voltage Transistor, NPN Silicon, 3-Pin SOT-23, Pb-Free, Tape and Reel")
      (fields (field (name "MANUFACTURER") "On Semiconductor"))
      (libsource (lib "ON Semi General Purpose Transistors") (part "MMBTA42LT1G"))
    )
    (comp (ref "Q50")
      (value "MMBTA42LT1G")
      (footprint "ONSC-SOT-23-3-318-08_V")
      (description "High Voltage Transistor, NPN Silicon, 3-Pin SOT-23, Pb-Free, Tape and Reel")
      (fields (field (name "MANUFACTURER") "On Semiconductor"))
      (libsource (lib "ON Semi General Purpose Transistors") (part "MMBTA42LT1G"))
    )
    (comp (ref "Q51")
      (value "MMBTA42LT1G")
      (footprint "ONSC-SOT-23-3-318-08_V")
      (description "High Voltage Transistor, NPN Silicon, 3-Pin SOT-23, Pb-Free, Tape and Reel")
      (fields (field (name "MANUFACTURER") "On Semiconductor"))
      (libsource (lib "ON Semi General Purpose Transistors") (part "MMBTA42LT1G"))
    )
    (comp (ref "Q52")
      (value "MMBTA42LT1G")
      (footprint "ONSC-SOT-23-3-318-08_V")
      (description "High Voltage Transistor, NPN Silicon, 3-Pin SOT-23, Pb-Free, Tape and Reel")
      (fields (field (name "MANUFACTURER") "On Semiconductor"))
      (libsource (lib "ON Semi General Purpose Transistors") (part "MMBTA42LT1G"))
    )
    (comp (ref "Q53")
      (value "MMBTA42LT1G")
      (footprint "ONSC-SOT-23-3-318-08_V")
      (description "High Voltage Transistor, NPN Silicon, 3-Pin SOT-23, Pb-Free, Tape and Reel")
      (fields (field (name "MANUFACTURER") "On Semiconductor"))
      (libsource (lib "ON Semi General Purpose Transistors") (part "MMBTA42LT1G"))
    )
    (comp (ref "Q54")
      (value "MMBTA42LT1G")
      (footprint "ONSC-SOT-23-3-318-08_V")
      (description "High Voltage Transistor, NPN Silicon, 3-Pin SOT-23, Pb-Free, Tape and Reel")
      (fields (field (name "MANUFACTURER") "On Semiconductor"))
      (libsource (lib "ON Semi General Purpose Transistors") (part "MMBTA42LT1G"))
    )
    (comp (ref "Q55")
      (value "MMBTA42LT1G")
      (footprint "ONSC-SOT-23-3-318-08_V")
      (description "High Voltage Transistor, NPN Silicon, 3-Pin SOT-23, Pb-Free, Tape and Reel")
      (fields (field (name "MANUFACTURER") "On Semiconductor"))
      (libsource (lib "ON Semi General Purpose Transistors") (part "MMBTA42LT1G"))
    )
    (comp (ref "Q56")
      (value "MMBTA42LT1G")
      (footprint "ONSC-SOT-23-3-318-08_V")
      (description "High Voltage Transistor, NPN Silicon, 3-Pin SOT-23, Pb-Free, Tape and Reel")
      (fields (field (name "MANUFACTURER") "On Semiconductor"))
      (libsource (lib "ON Semi General Purpose Transistors") (part "MMBTA42LT1G"))
    )
    (comp (ref "Q57")
      (value "MMBTA42LT1G")
      (footprint "ONSC-SOT-23-3-318-08_V")
      (description "High Voltage Transistor, NPN Silicon, 3-Pin SOT-23, Pb-Free, Tape and Reel")
      (fields (field (name "MANUFACTURER") "On Semiconductor"))
      (libsource (lib "ON Semi General Purpose Transistors") (part "MMBTA42LT1G"))
    )
    (comp (ref "Q58")
      (value "MMBTA42LT1G")
      (footprint "ONSC-SOT-23-3-318-08_V")
      (description "High Voltage Transistor, NPN Silicon, 3-Pin SOT-23, Pb-Free, Tape and Reel")
      (fields (field (name "MANUFACTURER") "On Semiconductor"))
      (libsource (lib "ON Semi General Purpose Transistors") (part "MMBTA42LT1G"))
    )
    (comp (ref "Q59")
      (value "MMBTA42LT1G")
      (footprint "ONSC-SOT-23-3-318-08_V")
      (description "High Voltage Transistor, NPN Silicon, 3-Pin SOT-23, Pb-Free, Tape and Reel")
      (fields (field (name "MANUFACTURER") "On Semiconductor"))
      (libsource (lib "ON Semi General Purpose Transistors") (part "MMBTA42LT1G"))
    )
    (comp (ref "Q60")
      (value "MMBTA42LT1G")
      (footprint "ONSC-SOT-23-3-318-08_V")
      (description "High Voltage Transistor, NPN Silicon, 3-Pin SOT-23, Pb-Free, Tape and Reel")
      (fields (field (name "MANUFACTURER") "On Semiconductor"))
      (libsource (lib "ON Semi General Purpose Transistors") (part "MMBTA42LT1G"))
    )
    (comp (ref "Q61")
      (value "MMBTA42LT1G")
      (footprint "ONSC-SOT-23-3-318-08_V")
      (description "High Voltage Transistor, NPN Silicon, 3-Pin SOT-23, Pb-Free, Tape and Reel")
      (fields (field (name "MANUFACTURER") "On Semiconductor"))
      (libsource (lib "ON Semi General Purpose Transistors") (part "MMBTA42LT1G"))
    )
    (comp (ref "Q62")
      (value "MMBTA42LT1G")
      (footprint "ONSC-SOT-23-3-318-08_V")
      (description "High Voltage Transistor, NPN Silicon, 3-Pin SOT-23, Pb-Free, Tape and Reel")
      (fields (field (name "MANUFACTURER") "On Semiconductor"))
      (libsource (lib "ON Semi General Purpose Transistors") (part "MMBTA42LT1G"))
    )
    (comp (ref "Q63")
      (value "MMBTA42LT1G")
      (footprint "ONSC-SOT-23-3-318-08_V")
      (description "High Voltage Transistor, NPN Silicon, 3-Pin SOT-23, Pb-Free, Tape and Reel")
      (fields (field (name "MANUFACTURER") "On Semiconductor"))
      (libsource (lib "ON Semi General Purpose Transistors") (part "MMBTA42LT1G"))
    )
    (comp (ref "Q64")
      (value "MMBTA42LT1G")
      (footprint "ONSC-SOT-23-3-318-08_V")
      (description "High Voltage Transistor, NPN Silicon, 3-Pin SOT-23, Pb-Free, Tape and Reel")
      (fields (field (name "MANUFACTURER") "On Semiconductor"))
      (libsource (lib "ON Semi General Purpose Transistors") (part "MMBTA42LT1G"))
    )
    (comp (ref "Q65")
      (value "IRFU024N")
      (footprint "TO-251AA")
      (description "HEXFET Power MOSFET")
      (fields (field (name "PUBLISHER") "Altium Limited"))
      (libsource (lib "IR Discrete MOSFET - Power") (part "IRFU024N"))
    )
    (comp (ref "Q66")
      (value "IRFU024N")
      (footprint "TO-251AA")
      (description "HEXFET Power MOSFET")
      (fields (field (name "PUBLISHER") "Altium Limited"))
      (libsource (lib "IR Discrete MOSFET - Power") (part "IRFU024N"))
    )
    (comp (ref "Q67")
      (value "IRFU9024")
      (footprint "TO-251AA")
      (description "HEXFET Power MOSFET")
      (fields (field (name "PUBLISHER") "Altium Limited"))
      (libsource (lib "IR Discrete MOSFET - Power") (part "IRFU9024"))
    )
    (comp (ref "Q68")
      (value "IRFU9024")
      (footprint "TO-251AA")
      (description "HEXFET Power MOSFET")
      (fields (field (name "PUBLISHER") "Altium Limited"))
      (libsource (lib "IR Discrete MOSFET - Power") (part "IRFU9024"))
    )
    (comp (ref "Q69")
      (value "IRFU024N")
      (footprint "TO-251AA")
      (description "HEXFET Power MOSFET")
      (fields (field (name "PUBLISHER") "Altium Limited"))
      (libsource (lib "IR Discrete MOSFET - Power") (part "IRFU024N"))
    )
    (comp (ref "Q70")
      (value "IRFU9024")
      (footprint "TO-251AA")
      (description "HEXFET Power MOSFET")
      (fields (field (name "PUBLISHER") "Altium Limited"))
      (libsource (lib "IR Discrete MOSFET - Power") (part "IRFU9024"))
    )
    (comp (ref "R1")
      (value "47k")
      (footprint "R1206")
      (description "SMD 1206 0.125W 5% 200V")
      (libsource (lib "SMD-RCL") (part "R-1206"))
    )
    (comp (ref "R2")
      (value "47k")
      (footprint "R1206")
      (description "SMD 1206 0.125W 5% 200V")
      (libsource (lib "SMD-RCL") (part "R-1206"))
    )
    (comp (ref "R3")
      (value "15k")
      (footprint "R1206")
      (description "SMD 1206 0.125W 5% 200V")
      (libsource (lib "SMD-RCL") (part "R-1206"))
    )
    (comp (ref "R4")
      (value "6.8k")
      (footprint "R1206")
      (description "SMD 1206 0.125W 5% 200V")
      (libsource (lib "SMD-RCL") (part "R-1206"))
    )
    (comp (ref "R5")
      (value "6.8k")
      (footprint "R1206")
      (description "SMD 1206 0.125W 5% 200V")
      (libsource (lib "SMD-RCL") (part "R-1206"))
    )
    (comp (ref "R6")
      (value "6.8k")
      (footprint "R1206")
      (description "SMD 1206 0.125W 5% 200V")
      (libsource (lib "SMD-RCL") (part "R-1206"))
    )
    (comp (ref "R7")
      (value "6.8k")
      (footprint "R1206")
      (description "SMD 1206 0.125W 5% 200V")
      (libsource (lib "SMD-RCL") (part "R-1206"))
    )
    (comp (ref "R8")
      (value "47k")
      (footprint "R1206")
      (description "SMD 1206 0.125W 5% 200V")
      (libsource (lib "SMD-RCL") (part "R-1206"))
    )
    (comp (ref "R9")
      (value "6.8k")
      (footprint "R1206")
      (description "SMD 1206 0.125W 5% 200V")
      (libsource (lib "SMD-RCL") (part "R-1206"))
    )
    (comp (ref "R10")
      (value "6.8k")
      (footprint "R1206")
      (description "SMD 1206 0.125W 5% 200V")
      (libsource (lib "SMD-RCL") (part "R-1206"))
    )
    (comp (ref "R11")
      (value "6.8k")
      (footprint "R1206")
      (description "SMD 1206 0.125W 5% 200V")
      (libsource (lib "SMD-RCL") (part "R-1206"))
    )
    (comp (ref "R12")
      (value "6.8k")
      (footprint "R1206")
      (description "SMD 1206 0.125W 5% 200V")
      (libsource (lib "SMD-RCL") (part "R-1206"))
    )
    (comp (ref "R13")
      (value "47k")
      (footprint "R1206")
      (description "SMD 1206 0.125W 5% 200V")
      (libsource (lib "SMD-RCL") (part "R-1206"))
    )
    (comp (ref "R14")
      (value "6.8k")
      (footprint "R1206")
      (description "SMD 1206 0.125W 5% 200V")
      (libsource (lib "SMD-RCL") (part "R-1206"))
    )
    (comp (ref "R15")
      (value "6.8k")
      (footprint "R1206")
      (description "SMD 1206 0.125W 5% 200V")
      (libsource (lib "SMD-RCL") (part "R-1206"))
    )
    (comp (ref "R16")
      (value "6.8k")
      (footprint "R1206")
      (description "SMD 1206 0.125W 5% 200V")
      (libsource (lib "SMD-RCL") (part "R-1206"))
    )
    (comp (ref "R17")
      (value "6.8k")
      (footprint "R1206")
      (description "SMD 1206 0.125W 5% 200V")
      (libsource (lib "SMD-RCL") (part "R-1206"))
    )
    (comp (ref "R18")
      (value "15k")
      (footprint "R1206")
      (description "SMD 1206 0.125W 5% 200V")
      (libsource (lib "SMD-RCL") (part "R-1206"))
    )
    (comp (ref "R19")
      (value "15k")
      (footprint "R1206")
      (description "SMD 1206 0.125W 5% 200V")
      (libsource (lib "SMD-RCL") (part "R-1206"))
    )
    (comp (ref "R20")
      (value "6.8k")
      (footprint "R1206")
      (description "SMD 1206 0.125W 5% 200V")
      (libsource (lib "SMD-RCL") (part "R-1206"))
    )
    (comp (ref "R21")
      (value "6.8k")
      (footprint "R1206")
      (description "SMD 1206 0.125W 5% 200V")
      (libsource (lib "SMD-RCL") (part "R-1206"))
    )
    (comp (ref "R22")
      (value "6.8k")
      (footprint "R1206")
      (description "SMD 1206 0.125W 5% 200V")
      (libsource (lib "SMD-RCL") (part "R-1206"))
    )
    (comp (ref "R23")
      (value "6.8k")
      (footprint "R1206")
      (description "SMD 1206 0.125W 5% 200V")
      (libsource (lib "SMD-RCL") (part "R-1206"))
    )
    (comp (ref "R24")
      (value "6.8k")
      (footprint "R1206")
      (description "SMD 1206 0.125W 5% 200V")
      (libsource (lib "SMD-RCL") (part "R-1206"))
    )
    (comp (ref "R25")
      (value "6.8k")
      (footprint "R1206")
      (description "SMD 1206 0.125W 5% 200V")
      (libsource (lib "SMD-RCL") (part "R-1206"))
    )
    (comp (ref "R26")
      (value "6.8k")
      (footprint "R1206")
      (description "SMD 1206 0.125W 5% 200V")
      (libsource (lib "SMD-RCL") (part "R-1206"))
    )
    (comp (ref "R27")
      (value "6.8k")
      (footprint "R1206")
      (description "SMD 1206 0.125W 5% 200V")
      (libsource (lib "SMD-RCL") (part "R-1206"))
    )
    (comp (ref "R28")
      (value "6.8k")
      (footprint "R1206")
      (description "SMD 1206 0.125W 5% 200V")
      (libsource (lib "SMD-RCL") (part "R-1206"))
    )
    (comp (ref "R29")
      (value "6.8k")
      (footprint "R1206")
      (description "SMD 1206 0.125W 5% 200V")
      (libsource (lib "SMD-RCL") (part "R-1206"))
    )
    (comp (ref "R30")
      (value "6.8k")
      (footprint "R1206")
      (description "SMD 1206 0.125W 5% 200V")
      (libsource (lib "SMD-RCL") (part "R-1206"))
    )
    (comp (ref "R31")
      (value "6.8k")
      (footprint "R1206")
      (description "SMD 1206 0.125W 5% 200V")
      (libsource (lib "SMD-RCL") (part "R-1206"))
    )
    (comp (ref "R32")
      (value "4.7k")
      (footprint "R0805")
      (description "SMD 0805 0.1W 5% 150V")
      (libsource (lib "SMD-RCL") (part "R-0805"))
    )
    (comp (ref "R33")
      (value "4.7k")
      (footprint "R0805")
      (description "SMD 0805 0.1W 5% 150V")
      (libsource (lib "SMD-RCL") (part "R-0805"))
    )
    (comp (ref "R34")
      (value "15k")
      (footprint "R1206")
      (description "SMD 1206 0.125W 5% 200V")
      (libsource (lib "SMD-RCL") (part "R-1206"))
    )
    (comp (ref "R35")
      (value "4.7k")
      (footprint "R0805")
      (description "SMD 0805 0.1W 5% 150V")
      (libsource (lib "SMD-RCL") (part "R-0805"))
    )
    (comp (ref "R36")
      (value "4.7k")
      (footprint "R0805")
      (description "SMD 0805 0.1W 5% 150V")
      (libsource (lib "SMD-RCL") (part "R-0805"))
    )
    (comp (ref "R37")
      (value "4.7k")
      (footprint "R0805")
      (description "SMD 0805 0.1W 5% 150V")
      (libsource (lib "SMD-RCL") (part "R-0805"))
    )
    (comp (ref "R38")
      (value "4.7k")
      (footprint "R0805")
      (description "SMD 0805 0.1W 5% 150V")
      (libsource (lib "SMD-RCL") (part "R-0805"))
    )
    (comp (ref "R39")
      (value "4.7k")
      (footprint "R0805")
      (description "SMD 0805 0.1W 5% 150V")
      (libsource (lib "SMD-RCL") (part "R-0805"))
    )
    (comp (ref "R40")
      (value "4.7k")
      (footprint "R0805")
      (description "SMD 0805 0.1W 5% 150V")
      (libsource (lib "SMD-RCL") (part "R-0805"))
    )
    (comp (ref "R41")
      (value "4.7k")
      (footprint "R0805")
      (description "SMD 0805 0.1W 5% 150V")
      (libsource (lib "SMD-RCL") (part "R-0805"))
    )
    (comp (ref "R42")
      (value "4.7k")
      (footprint "R0805")
      (description "SMD 0805 0.1W 5% 150V")
      (libsource (lib "SMD-RCL") (part "R-0805"))
    )
    (comp (ref "R43")
      (value "4.7k")
      (footprint "R0805")
      (description "SMD 0805 0.1W 5% 150V")
      (libsource (lib "SMD-RCL") (part "R-0805"))
    )
    (comp (ref "R44")
      (value "4.7k")
      (footprint "R0805")
      (description "SMD 0805 0.1W 5% 150V")
      (libsource (lib "SMD-RCL") (part "R-0805"))
    )
    (comp (ref "R45")
      (value "4.7k")
      (footprint "R0805")
      (description "SMD 0805 0.1W 5% 150V")
      (libsource (lib "SMD-RCL") (part "R-0805"))
    )
    (comp (ref "R46")
      (value "4.7k")
      (footprint "R0805")
      (description "SMD 0805 0.1W 5% 150V")
      (libsource (lib "SMD-RCL") (part "R-0805"))
    )
    (comp (ref "R47")
      (value "4.7k")
      (footprint "R0805")
      (description "SMD 0805 0.1W 5% 150V")
      (libsource (lib "SMD-RCL") (part "R-0805"))
    )
    (comp (ref "R48")
      (value "4.7k")
      (footprint "R0805")
      (description "SMD 0805 0.1W 5% 150V")
      (libsource (lib "SMD-RCL") (part "R-0805"))
    )
    (comp (ref "R49")
      (value "4.7k")
      (footprint "R0805")
      (description "SMD 0805 0.1W 5% 150V")
      (libsource (lib "SMD-RCL") (part "R-0805"))
    )
    (comp (ref "R50")
      (value "4.7k")
      (footprint "R0805")
      (description "SMD 0805 0.1W 5% 150V")
      (libsource (lib "SMD-RCL") (part "R-0805"))
    )
    (comp (ref "R51")
      (value "4.7k")
      (footprint "R0805")
      (description "SMD 0805 0.1W 5% 150V")
      (libsource (lib "SMD-RCL") (part "R-0805"))
    )
    (comp (ref "R52")
      (value "4.7k")
      (footprint "R0805")
      (description "SMD 0805 0.1W 5% 150V")
      (libsource (lib "SMD-RCL") (part "R-0805"))
    )
    (comp (ref "R53")
      (value "4.7k")
      (footprint "R0805")
      (description "SMD 0805 0.1W 5% 150V")
      (libsource (lib "SMD-RCL") (part "R-0805"))
    )
    (comp (ref "R54")
      (value "4.7k")
      (footprint "R0805")
      (description "SMD 0805 0.1W 5% 150V")
      (libsource (lib "SMD-RCL") (part "R-0805"))
    )
    (comp (ref "R55")
      (value "4.7k")
      (footprint "R0805")
      (description "SMD 0805 0.1W 5% 150V")
      (libsource (lib "SMD-RCL") (part "R-0805"))
    )
    (comp (ref "R56")
      (value "4.7k")
      (footprint "R0805")
      (description "SMD 0805 0.1W 5% 150V")
      (libsource (lib "SMD-RCL") (part "R-0805"))
    )
    (comp (ref "R57")
      (value "4.7k")
      (footprint "R0805")
      (description "SMD 0805 0.1W 5% 150V")
      (libsource (lib "SMD-RCL") (part "R-0805"))
    )
    (comp (ref "R58")
      (value "4.7k")
      (footprint "R0805")
      (description "SMD 0805 0.1W 5% 150V")
      (libsource (lib "SMD-RCL") (part "R-0805"))
    )
    (comp (ref "R59")
      (value "4.7k")
      (footprint "R0805")
      (description "SMD 0805 0.1W 5% 150V")
      (libsource (lib "SMD-RCL") (part "R-0805"))
    )
    (comp (ref "R60")
      (value "4.7k")
      (footprint "R0805")
      (description "SMD 0805 0.1W 5% 150V")
      (libsource (lib "SMD-RCL") (part "R-0805"))
    )
    (comp (ref "R61")
      (value "4.7k")
      (footprint "R0805")
      (description "SMD 0805 0.1W 5% 150V")
      (libsource (lib "SMD-RCL") (part "R-0805"))
    )
    (comp (ref "R62")
      (value "4.7k")
      (footprint "R0805")
      (description "SMD 0805 0.1W 5% 150V")
      (libsource (lib "SMD-RCL") (part "R-0805"))
    )
    (comp (ref "R63")
      (value "4.7k")
      (footprint "R0805")
      (description "SMD 0805 0.1W 5% 150V")
      (libsource (lib "SMD-RCL") (part "R-0805"))
    )
    (comp (ref "R64")
      (value "4.7k")
      (footprint "R0805")
      (description "SMD 0805 0.1W 5% 150V")
      (libsource (lib "SMD-RCL") (part "R-0805"))
    )
    (comp (ref "R65")
      (value "4.7k")
      (footprint "R0805")
      (description "SMD 0805 0.1W 5% 150V")
      (libsource (lib "SMD-RCL") (part "R-0805"))
    )
    (comp (ref "R66")
      (value "4.7k")
      (footprint "R0805")
      (description "SMD 0805 0.1W 5% 150V")
      (libsource (lib "SMD-RCL") (part "R-0805"))
    )
    (comp (ref "R67")
      (value "47k")
      (footprint "R1206")
      (description "SMD 1206 0.125W 5% 200V")
      (libsource (lib "SMD-RCL") (part "R-1206"))
    )
    (comp (ref "R68")
      (value "4.7k")
      (footprint "R0805")
      (description "SMD 0805 0.1W 5% 150V")
      (libsource (lib "SMD-RCL") (part "R-0805"))
    )
    (comp (ref "R69")
      (value "4.7k")
      (footprint "R0805")
      (description "SMD 0805 0.1W 5% 150V")
      (libsource (lib "SMD-RCL") (part "R-0805"))
    )
    (comp (ref "R70")
      (value "4.7k")
      (footprint "R0805")
      (description "SMD 0805 0.1W 5% 150V")
      (libsource (lib "SMD-RCL") (part "R-0805"))
    )
    (comp (ref "R71")
      (value "4.7k")
      (footprint "R0805")
      (description "SMD 0805 0.1W 5% 150V")
      (libsource (lib "SMD-RCL") (part "R-0805"))
    )
    (comp (ref "R72")
      (value "4.7k")
      (footprint "R0805")
      (description "SMD 0805 0.1W 5% 150V")
      (libsource (lib "SMD-RCL") (part "R-0805"))
    )
    (comp (ref "R73")
      (value "4.7k")
      (footprint "R0805")
      (description "SMD 0805 0.1W 5% 150V")
      (libsource (lib "SMD-RCL") (part "R-0805"))
    )
    (comp (ref "R74")
      (value "4.7k")
      (footprint "R0805")
      (description "SMD 0805 0.1W 5% 150V")
      (libsource (lib "SMD-RCL") (part "R-0805"))
    )
    (comp (ref "R75")
      (value "4.7k")
      (footprint "R0805")
      (description "SMD 0805 0.1W 5% 150V")
      (libsource (lib "SMD-RCL") (part "R-0805"))
    )
    (comp (ref "R76")
      (value "47k")
      (footprint "R1206")
      (description "SMD 1206 0.125W 5% 200V")
      (libsource (lib "SMD-RCL") (part "R-1206"))
    )
    (comp (ref "R77")
      (value "4.7k")
      (footprint "R0805")
      (description "SMD 0805 0.1W 5% 150V")
      (libsource (lib "SMD-RCL") (part "R-0805"))
    )
    (comp (ref "R78")
      (value "4.7k")
      (footprint "R0805")
      (description "SMD 0805 0.1W 5% 150V")
      (libsource (lib "SMD-RCL") (part "R-0805"))
    )
    (comp (ref "R79")
      (value "4.7k")
      (footprint "R0805")
      (description "SMD 0805 0.1W 5% 150V")
      (libsource (lib "SMD-RCL") (part "R-0805"))
    )
    (comp (ref "R80")
      (value "4.7k")
      (footprint "R0805")
      (description "SMD 0805 0.1W 5% 150V")
      (libsource (lib "SMD-RCL") (part "R-0805"))
    )
    (comp (ref "R81")
      (value "4.7k")
      (footprint "R0805")
      (description "SMD 0805 0.1W 5% 150V")
      (libsource (lib "SMD-RCL") (part "R-0805"))
    )
    (comp (ref "R82")
      (value "4.7k")
      (footprint "R0805")
      (description "SMD 0805 0.1W 5% 150V")
      (libsource (lib "SMD-RCL") (part "R-0805"))
    )
    (comp (ref "R83")
      (value "4.7k")
      (footprint "R0805")
      (description "SMD 0805 0.1W 5% 150V")
      (libsource (lib "SMD-RCL") (part "R-0805"))
    )
    (comp (ref "R84")
      (value "4.7k")
      (footprint "R0805")
      (description "SMD 0805 0.1W 5% 150V")
      (libsource (lib "SMD-RCL") (part "R-0805"))
    )
    (comp (ref "R85")
      (value "4.7k")
      (footprint "R0805")
      (description "SMD 0805 0.1W 5% 150V")
      (libsource (lib "SMD-RCL") (part "R-0805"))
    )
    (comp (ref "R86")
      (value "4.7k")
      (footprint "R0805")
      (description "SMD 0805 0.1W 5% 150V")
      (libsource (lib "SMD-RCL") (part "R-0805"))
    )
    (comp (ref "R87")
      (value "4.7k")
      (footprint "R0805")
      (description "SMD 0805 0.1W 5% 150V")
      (libsource (lib "SMD-RCL") (part "R-0805"))
    )
    (comp (ref "R88")
      (value "4.7k")
      (footprint "R0805")
      (description "SMD 0805 0.1W 5% 150V")
      (libsource (lib "SMD-RCL") (part "R-0805"))
    )
    (comp (ref "R89")
      (value "47k")
      (footprint "R1206")
      (description "SMD 1206 0.125W 5% 200V")
      (libsource (lib "SMD-RCL") (part "R-1206"))
    )
    (comp (ref "R90")
      (value "4.7k")
      (footprint "R0805")
      (description "SMD 0805 0.1W 5% 150V")
      (libsource (lib "SMD-RCL") (part "R-0805"))
    )
    (comp (ref "R91")
      (value "4.7k")
      (footprint "R0805")
      (description "SMD 0805 0.1W 5% 150V")
      (libsource (lib "SMD-RCL") (part "R-0805"))
    )
    (comp (ref "R92")
      (value "4.7k")
      (footprint "R0805")
      (description "SMD 0805 0.1W 5% 150V")
      (libsource (lib "SMD-RCL") (part "R-0805"))
    )
    (comp (ref "R93")
      (value "4.7k")
      (footprint "R0805")
      (description "SMD 0805 0.1W 5% 150V")
      (libsource (lib "SMD-RCL") (part "R-0805"))
    )
    (comp (ref "R94")
      (value "47k")
      (footprint "R1206")
      (description "SMD 1206 0.125W 5% 200V")
      (libsource (lib "SMD-RCL") (part "R-1206"))
    )
    (comp (ref "R95")
      (value "4.7k")
      (footprint "R0805")
      (description "SMD 0805 0.1W 5% 150V")
      (libsource (lib "SMD-RCL") (part "R-0805"))
    )
    (comp (ref "R96")
      (value "4.7k")
      (footprint "R0805")
      (description "SMD 0805 0.1W 5% 150V")
      (libsource (lib "SMD-RCL") (part "R-0805"))
    )
    (comp (ref "R97")
      (value "4.7k")
      (footprint "R0805")
      (description "SMD 0805 0.1W 5% 150V")
      (libsource (lib "SMD-RCL") (part "R-0805"))
    )
    (comp (ref "R98")
      (value "4.7k")
      (footprint "R0805")
      (description "SMD 0805 0.1W 5% 150V")
      (libsource (lib "SMD-RCL") (part "R-0805"))
    )
    (comp (ref "R99")
      (value "4.7k")
      (footprint "R0805")
      (description "SMD 0805 0.1W 5% 150V")
      (libsource (lib "SMD-RCL") (part "R-0805"))
    )
    (comp (ref "R100")
      (value "4.7k")
      (footprint "R0805")
      (description "SMD 0805 0.1W 5% 150V")
      (libsource (lib "SMD-RCL") (part "R-0805"))
    )
    (comp (ref "R101")
      (value "15k")
      (footprint "R1206")
      (description "SMD 1206 0.125W 5% 200V")
      (libsource (lib "SMD-RCL") (part "R-1206"))
    )
    (comp (ref "R102")
      (value "10")
      (footprint "R0805")
      (description "SMD 0805 0.1W 5% 150V")
      (libsource (lib "SMD-RCL") (part "R-0805"))
    )
    (comp (ref "R103")
      (value "10")
      (footprint "R0805")
      (description "SMD 0805 0.1W 5% 150V")
      (libsource (lib "SMD-RCL") (part "R-0805"))
    )
    (comp (ref "R104")
      (value "47k")
      (footprint "R1206")
      (description "SMD 1206 0.125W 5% 200V")
      (libsource (lib "SMD-RCL") (part "R-1206"))
    )
    (comp (ref "R105")
      (value "47k")
      (footprint "R1206")
      (description "SMD 1206 0.125W 5% 200V")
      (libsource (lib "SMD-RCL") (part "R-1206"))
    )
    (comp (ref "R106")
      (value "47k")
      (footprint "R1206")
      (description "SMD 1206 0.125W 5% 200V")
      (libsource (lib "SMD-RCL") (part "R-1206"))
    )
    (comp (ref "R107")
      (value "47k")
      (footprint "R1206")
      (description "SMD 1206 0.125W 5% 200V")
      (libsource (lib "SMD-RCL") (part "R-1206"))
    )
    (comp (ref "R108")
      (value "47k")
      (footprint "R1206")
      (description "SMD 1206 0.125W 5% 200V")
      (libsource (lib "SMD-RCL") (part "R-1206"))
    )
    (comp (ref "R109")
      (value "47k")
      (footprint "R1206")
      (description "SMD 1206 0.125W 5% 200V")
      (libsource (lib "SMD-RCL") (part "R-1206"))
    )
    (comp (ref "R110")
      (value "47k")
      (footprint "R1206")
      (description "SMD 1206 0.125W 5% 200V")
      (libsource (lib "SMD-RCL") (part "R-1206"))
    )
    (comp (ref "R111")
      (value "47k")
      (footprint "R1206")
      (description "SMD 1206 0.125W 5% 200V")
      (libsource (lib "SMD-RCL") (part "R-1206"))
    )
    (comp (ref "R112")
      (value "47k")
      (footprint "R1206")
      (description "SMD 1206 0.125W 5% 200V")
      (libsource (lib "SMD-RCL") (part "R-1206"))
    )
    (comp (ref "R113")
      (value "6.8k")
      (footprint "R1206")
      (description "SMD 1206 0.125W 5% 200V")
      (libsource (lib "SMD-RCL") (part "R-1206"))
    )
    (comp (ref "R114")
      (value "39k")
      (footprint "R0805")
      (description "SMD 0805 0.1W 5% 150V")
      (libsource (lib "SMD-RCL") (part "R-0805"))
    )
    (comp (ref "R115")
      (value "15k")
      (footprint "R1206")
      (description "SMD 1206 0.125W 5% 200V")
      (libsource (lib "SMD-RCL") (part "R-1206"))
    )
    (comp (ref "R116")
      (value "1k")
      (footprint "R1206")
      (description "SMD 1206 0.125W 5% 200V")
      (libsource (lib "SMD-RCL") (part "R-1206"))
    )
    (comp (ref "R117")
      (value "4.7k")
      (footprint "R0805")
      (description "SMD 0805 0.1W 5% 150V")
      (libsource (lib "SMD-RCL") (part "R-0805"))
    )
    (comp (ref "R118")
      (value "4.7k")
      (footprint "R0805")
      (description "SMD 0805 0.1W 5% 150V")
      (libsource (lib "SMD-RCL") (part "R-0805"))
    )
    (comp (ref "R119")
      (value "470")
      (footprint "R0805")
      (description "SMD 0805 0.1W 5% 150V")
      (libsource (lib "SMD-RCL") (part "R-0805"))
    )
    (comp (ref "R120")
      (value "47k")
      (footprint "R1206")
      (description "SMD 1206 0.125W 5% 200V")
      (libsource (lib "SMD-RCL") (part "R-1206"))
    )
    (comp (ref "R121")
      (value "4.7k")
      (footprint "R0805")
      (description "SMD 0805 0.1W 5% 150V")
      (libsource (lib "SMD-RCL") (part "R-0805"))
    )
    (comp (ref "R122")
      (value "4.7k")
      (footprint "R0805")
      (description "SMD 0805 0.1W 5% 150V")
      (libsource (lib "SMD-RCL") (part "R-0805"))
    )
    (comp (ref "R123")
      (value "4.7M")
      (footprint "R0805")
      (description "SMD 0805 0.1W 5% 150V")
      (libsource (lib "SMD-RCL") (part "R-0805"))
    )
    (comp (ref "R124")
      (value "4.7k")
      (footprint "R0805")
      (description "SMD 0805 0.1W 5% 150V")
      (libsource (lib "SMD-RCL") (part "R-0805"))
    )
    (comp (ref "R125")
      (value "4.7k")
      (footprint "R0805")
      (description "SMD 0805 0.1W 5% 150V")
      (libsource (lib "SMD-RCL") (part "R-0805"))
    )
    (comp (ref "R126")
      (value "4.7k")
      (footprint "R0805")
      (description "SMD 0805 0.1W 5% 150V")
      (libsource (lib "SMD-RCL") (part "R-0805"))
    )
    (comp (ref "R127")
      (value "4.7k")
      (footprint "R0805")
      (description "SMD 0805 0.1W 5% 150V")
      (libsource (lib "SMD-RCL") (part "R-0805"))
    )
    (comp (ref "R128")
      (value "4.7k")
      (footprint "R0805")
      (description "SMD 0805 0.1W 5% 150V")
      (libsource (lib "SMD-RCL") (part "R-0805"))
    )
    (comp (ref "R129")
      (value "4.7k")
      (footprint "R0805")
      (description "SMD 0805 0.1W 5% 150V")
      (libsource (lib "SMD-RCL") (part "R-0805"))
    )
    (comp (ref "R130")
      (value "4.7k")
      (footprint "R0805")
      (description "SMD 0805 0.1W 5% 150V")
      (libsource (lib "SMD-RCL") (part "R-0805"))
    )
    (comp (ref "R131")
      (value "4.7k")
      (footprint "R0805")
      (description "SMD 0805 0.1W 5% 150V")
      (libsource (lib "SMD-RCL") (part "R-0805"))
    )
    (comp (ref "R132")
      (value "4.7k")
      (footprint "R0805")
      (description "SMD 0805 0.1W 5% 150V")
      (libsource (lib "SMD-RCL") (part "R-0805"))
    )
    (comp (ref "R133")
      (value "4.7k")
      (footprint "R0805")
      (description "SMD 0805 0.1W 5% 150V")
      (libsource (lib "SMD-RCL") (part "R-0805"))
    )
    (comp (ref "R134")
      (value "470")
      (footprint "R0805")
      (description "SMD 0805 0.1W 5% 150V")
      (libsource (lib "SMD-RCL") (part "R-0805"))
    )
    (comp (ref "R135")
      (value "15k")
      (footprint "R1206")
      (description "SMD 1206 0.125W 5% 200V")
      (libsource (lib "SMD-RCL") (part "R-1206"))
    )
    (comp (ref "R136")
      (value "10")
      (footprint "R0805")
      (description "SMD 0805 0.1W 5% 150V")
      (libsource (lib "SMD-RCL") (part "R-0805"))
    )
    (comp (ref "R137")
      (value "10")
      (footprint "R0805")
      (description "SMD 0805 0.1W 5% 150V")
      (libsource (lib "SMD-RCL") (part "R-0805"))
    )
    (comp (ref "R138")
      (value "4.7k")
      (footprint "R0805")
      (description "SMD 0805 0.1W 5% 150V")
      (libsource (lib "SMD-RCL") (part "R-0805"))
    )
    (comp (ref "R139")
      (value "4.7k")
      (footprint "R0805")
      (description "SMD 0805 0.1W 5% 150V")
      (libsource (lib "SMD-RCL") (part "R-0805"))
    )
    (comp (ref "R140")
      (value "4.7k")
      (footprint "R0805")
      (description "SMD 0805 0.1W 5% 150V")
      (libsource (lib "SMD-RCL") (part "R-0805"))
    )
    (comp (ref "R141")
      (value "4.7k")
      (footprint "R0805")
      (description "SMD 0805 0.1W 5% 150V")
      (libsource (lib "SMD-RCL") (part "R-0805"))
    )
    (comp (ref "R142")
      (value "4.7k")
      (footprint "R0805")
      (description "SMD 0805 0.1W 5% 150V")
      (libsource (lib "SMD-RCL") (part "R-0805"))
    )
    (comp (ref "R143")
      (value "4.7k")
      (footprint "R0805")
      (description "SMD 0805 0.1W 5% 150V")
      (libsource (lib "SMD-RCL") (part "R-0805"))
    )
    (comp (ref "R144")
      (value "4.7k")
      (footprint "R0805")
      (description "SMD 0805 0.1W 5% 150V")
      (libsource (lib "SMD-RCL") (part "R-0805"))
    )
    (comp (ref "R145")
      (value "4.7k")
      (footprint "R0805")
      (description "SMD 0805 0.1W 5% 150V")
      (libsource (lib "SMD-RCL") (part "R-0805"))
    )
    (comp (ref "R146")
      (value "4.7k")
      (footprint "R0805")
      (description "SMD 0805 0.1W 5% 150V")
      (libsource (lib "SMD-RCL") (part "R-0805"))
    )
    (comp (ref "R147")
      (value "4.7k")
      (footprint "R0805")
      (description "SMD 0805 0.1W 5% 150V")
      (libsource (lib "SMD-RCL") (part "R-0805"))
    )
    (comp (ref "R148")
      (value "4.7k")
      (footprint "R0805")
      (description "SMD 0805 0.1W 5% 150V")
      (libsource (lib "SMD-RCL") (part "R-0805"))
    )
    (comp (ref "R149")
      (value "4.7k")
      (footprint "R0805")
      (description "SMD 0805 0.1W 5% 150V")
      (libsource (lib "SMD-RCL") (part "R-0805"))
    )
    (comp (ref "R150")
      (value "4.7k")
      (footprint "R0805")
      (description "SMD 0805 0.1W 5% 150V")
      (libsource (lib "SMD-RCL") (part "R-0805"))
    )
    (comp (ref "R151")
      (value "4.7k")
      (footprint "R0805")
      (description "SMD 0805 0.1W 5% 150V")
      (libsource (lib "SMD-RCL") (part "R-0805"))
    )
    (comp (ref "R152")
      (value "4.7k")
      (footprint "R0805")
      (description "SMD 0805 0.1W 5% 150V")
      (libsource (lib "SMD-RCL") (part "R-0805"))
    )
    (comp (ref "R153")
      (value "4.7k")
      (footprint "R0805")
      (description "SMD 0805 0.1W 5% 150V")
      (libsource (lib "SMD-RCL") (part "R-0805"))
    )
    (comp (ref "R154")
      (value "4.7k")
      (footprint "R0805")
      (description "SMD 0805 0.1W 5% 150V")
      (libsource (lib "SMD-RCL") (part "R-0805"))
    )
    (comp (ref "R155")
      (value "4.7k")
      (footprint "R0805")
      (description "SMD 0805 0.1W 5% 150V")
      (libsource (lib "SMD-RCL") (part "R-0805"))
    )
    (comp (ref "R156")
      (value "4.7k")
      (footprint "R0805")
      (description "SMD 0805 0.1W 5% 150V")
      (libsource (lib "SMD-RCL") (part "R-0805"))
    )
    (comp (ref "R157")
      (value "4.7k")
      (footprint "R0805")
      (description "SMD 0805 0.1W 5% 150V")
      (libsource (lib "SMD-RCL") (part "R-0805"))
    )
    (comp (ref "R158")
      (value "4.7k")
      (footprint "R0805")
      (description "SMD 0805 0.1W 5% 150V")
      (libsource (lib "SMD-RCL") (part "R-0805"))
    )
    (comp (ref "R159")
      (value "4.7k")
      (footprint "R0805")
      (description "SMD 0805 0.1W 5% 150V")
      (libsource (lib "SMD-RCL") (part "R-0805"))
    )
    (comp (ref "R160")
      (value "4.7k")
      (footprint "R0805")
      (description "SMD 0805 0.1W 5% 150V")
      (libsource (lib "SMD-RCL") (part "R-0805"))
    )
    (comp (ref "R161")
      (value "4.7k")
      (footprint "R0805")
      (description "SMD 0805 0.1W 5% 150V")
      (libsource (lib "SMD-RCL") (part "R-0805"))
    )
    (comp (ref "R162")
      (value "4.7k")
      (footprint "R0805")
      (description "SMD 0805 0.1W 5% 150V")
      (libsource (lib "SMD-RCL") (part "R-0805"))
    )
    (comp (ref "R163")
      (value "4.7k")
      (footprint "R0805")
      (description "SMD 0805 0.1W 5% 150V")
      (libsource (lib "SMD-RCL") (part "R-0805"))
    )
    (comp (ref "R164")
      (value "4.7k")
      (footprint "R0805")
      (description "SMD 0805 0.1W 5% 150V")
      (libsource (lib "SMD-RCL") (part "R-0805"))
    )
    (comp (ref "R165")
      (value "4.7k")
      (footprint "R0805")
      (description "SMD 0805 0.1W 5% 150V")
      (libsource (lib "SMD-RCL") (part "R-0805"))
    )
    (comp (ref "R166")
      (value "4.7k")
      (footprint "R0805")
      (description "SMD 0805 0.1W 5% 150V")
      (libsource (lib "SMD-RCL") (part "R-0805"))
    )
    (comp (ref "R167")
      (value "4.7k")
      (footprint "R0805")
      (description "SMD 0805 0.1W 5% 150V")
      (libsource (lib "SMD-RCL") (part "R-0805"))
    )
    (comp (ref "R168")
      (value "4.7k")
      (footprint "R0805")
      (description "SMD 0805 0.1W 5% 150V")
      (libsource (lib "SMD-RCL") (part "R-0805"))
    )
    (comp (ref "R169")
      (value "4.7k")
      (footprint "R0805")
      (description "SMD 0805 0.1W 5% 150V")
      (libsource (lib "SMD-RCL") (part "R-0805"))
    )
    (comp (ref "R170")
      (value "4.7k")
      (footprint "R0805")
      (description "SMD 0805 0.1W 5% 150V")
      (libsource (lib "SMD-RCL") (part "R-0805"))
    )
    (comp (ref "R171")
      (value "4.7k")
      (footprint "R0805")
      (description "SMD 0805 0.1W 5% 150V")
      (libsource (lib "SMD-RCL") (part "R-0805"))
    )
    (comp (ref "R172")
      (value "4.7k")
      (footprint "R0805")
      (description "SMD 0805 0.1W 5% 150V")
      (libsource (lib "SMD-RCL") (part "R-0805"))
    )
    (comp (ref "R173")
      (value "4.7k")
      (footprint "R0805")
      (description "SMD 0805 0.1W 5% 150V")
      (libsource (lib "SMD-RCL") (part "R-0805"))
    )
    (comp (ref "R174")
      (value "4.7k")
      (footprint "R0805")
      (description "SMD 0805 0.1W 5% 150V")
      (libsource (lib "SMD-RCL") (part "R-0805"))
    )
    (comp (ref "R175")
      (value "4.7k")
      (footprint "R0805")
      (description "SMD 0805 0.1W 5% 150V")
      (libsource (lib "SMD-RCL") (part "R-0805"))
    )
    (comp (ref "R176")
      (value "4.7k")
      (footprint "R0805")
      (description "SMD 0805 0.1W 5% 150V")
      (libsource (lib "SMD-RCL") (part "R-0805"))
    )
    (comp (ref "R177")
      (value "4.7k")
      (footprint "R0805")
      (description "SMD 0805 0.1W 5% 150V")
      (libsource (lib "SMD-RCL") (part "R-0805"))
    )
    (comp (ref "R178")
      (value "4.7k")
      (footprint "R0805")
      (description "SMD 0805 0.1W 5% 150V")
      (libsource (lib "SMD-RCL") (part "R-0805"))
    )
    (comp (ref "R179")
      (value "4.7k")
      (footprint "R0805")
      (description "SMD 0805 0.1W 5% 150V")
      (libsource (lib "SMD-RCL") (part "R-0805"))
    )
    (comp (ref "R180")
      (value "4.7k")
      (footprint "R0805")
      (description "SMD 0805 0.1W 5% 150V")
      (libsource (lib "SMD-RCL") (part "R-0805"))
    )
    (comp (ref "R181")
      (value "4.7k")
      (footprint "R0805")
      (description "SMD 0805 0.1W 5% 150V")
      (libsource (lib "SMD-RCL") (part "R-0805"))
    )
    (comp (ref "R182")
      (value "4.7k")
      (footprint "R0805")
      (description "SMD 0805 0.1W 5% 150V")
      (libsource (lib "SMD-RCL") (part "R-0805"))
    )
    (comp (ref "R183")
      (value "4.7k")
      (footprint "R0805")
      (description "SMD 0805 0.1W 5% 150V")
      (libsource (lib "SMD-RCL") (part "R-0805"))
    )
    (comp (ref "R184")
      (value "4.7k")
      (footprint "R0805")
      (description "SMD 0805 0.1W 5% 150V")
      (libsource (lib "SMD-RCL") (part "R-0805"))
    )
    (comp (ref "R185")
      (value "4.7k")
      (footprint "R0805")
      (description "SMD 0805 0.1W 5% 150V")
      (libsource (lib "SMD-RCL") (part "R-0805"))
    )
    (comp (ref "R186")
      (value "4.7k")
      (footprint "R0805")
      (description "SMD 0805 0.1W 5% 150V")
      (libsource (lib "SMD-RCL") (part "R-0805"))
    )
    (comp (ref "R187")
      (value "4.7k")
      (footprint "R0805")
      (description "SMD 0805 0.1W 5% 150V")
      (libsource (lib "SMD-RCL") (part "R-0805"))
    )
    (comp (ref "R188")
      (value "4.7k")
      (footprint "R0805")
      (description "SMD 0805 0.1W 5% 150V")
      (libsource (lib "SMD-RCL") (part "R-0805"))
    )
    (comp (ref "R189")
      (value "4.7k")
      (footprint "R0805")
      (description "SMD 0805 0.1W 5% 150V")
      (libsource (lib "SMD-RCL") (part "R-0805"))
    )
    (comp (ref "R190")
      (value "4.7k")
      (footprint "R0805")
      (description "SMD 0805 0.1W 5% 150V")
      (libsource (lib "SMD-RCL") (part "R-0805"))
    )
    (comp (ref "R191")
      (value "4.7k")
      (footprint "R0805")
      (description "SMD 0805 0.1W 5% 150V")
      (libsource (lib "SMD-RCL") (part "R-0805"))
    )
    (comp (ref "R192")
      (value "4.7k")
      (footprint "R0805")
      (description "SMD 0805 0.1W 5% 150V")
      (libsource (lib "SMD-RCL") (part "R-0805"))
    )
    (comp (ref "R193")
      (value "4.7k")
      (footprint "R0805")
      (description "SMD 0805 0.1W 5% 150V")
      (libsource (lib "SMD-RCL") (part "R-0805"))
    )
    (comp (ref "R194")
      (value "4.7k")
      (footprint "R0805")
      (description "SMD 0805 0.1W 5% 150V")
      (libsource (lib "SMD-RCL") (part "R-0805"))
    )
    (comp (ref "R195")
      (value "4.7k")
      (footprint "R0805")
      (description "SMD 0805 0.1W 5% 150V")
      (libsource (lib "SMD-RCL") (part "R-0805"))
    )
    (comp (ref "R196")
      (value "4.7k")
      (footprint "R0805")
      (description "SMD 0805 0.1W 5% 150V")
      (libsource (lib "SMD-RCL") (part "R-0805"))
    )
    (comp (ref "R197")
      (value "4.7k")
      (footprint "R0805")
      (description "SMD 0805 0.1W 5% 150V")
      (libsource (lib "SMD-RCL") (part "R-0805"))
    )
    (comp (ref "R198")
      (value "4.7k")
      (footprint "R0805")
      (description "SMD 0805 0.1W 5% 150V")
      (libsource (lib "SMD-RCL") (part "R-0805"))
    )
    (comp (ref "R199")
      (value "4.7k")
      (footprint "R0805")
      (description "SMD 0805 0.1W 5% 150V")
      (libsource (lib "SMD-RCL") (part "R-0805"))
    )
    (comp (ref "R200")
      (value "4.7k")
      (footprint "R0805")
      (description "SMD 0805 0.1W 5% 150V")
      (libsource (lib "SMD-RCL") (part "R-0805"))
    )
    (comp (ref "SB1") (value "Mode") (footprint "TS-06") (libsource (lib "Devise") (part "Buton TS-06")))
    (comp (ref "SB2") (value "Hour") (footprint "TS-06") (libsource (lib "Devise") (part "Buton TS-06")))
    (comp (ref "SB3") (value "Min") (footprint "TS-06") (libsource (lib "Devise") (part "Buton TS-06")))
    (comp (ref "SB4") (value "Alarm") (footprint "TS-06") (libsource (lib "Devise") (part "Buton TS-06")))
    (comp (ref "Tr1")
      (value "Transf0rmer")
      (footprint "PCBComponent_1 - duplicate1")
      (libsource (lib "Schlib1") (part "Transf0rmer"))
    )
    (comp (ref "U1")
      (value "74HC595")
      (footprint "SO-16_N")
      (description "8-Bit Serial-Input/Serial-or-Parallel-Output Shift Register with Latched 3-State Outputs")
      (fields (field (name "PUBLISHER") "Altium Limited"))
      (libsource (lib "PCB_Project") (part "74HC595"))
    )
    (comp (ref "U2")
      (value "74HC595")
      (footprint "SO-16_N")
      (description "8-Bit Serial-Input/Serial-or-Parallel-Output Shift Register with Latched 3-State Outputs")
      (fields (field (name "PUBLISHER") "Altium Limited"))
      (libsource (lib "PCB_Project") (part "74HC595"))
    )
    (comp (ref "U3")
      (value "74HC595")
      (footprint "SO-16_N")
      (description "8-Bit Serial-Input/Serial-or-Parallel-Output Shift Register with Latched 3-State Outputs")
      (fields (field (name "PUBLISHER") "Altium Limited"))
      (libsource (lib "PCB_Project") (part "74HC595"))
    )
    (comp (ref "U4")
      (value "74HC595")
      (footprint "SO-16_N")
      (description "8-Bit Serial-Input/Serial-or-Parallel-Output Shift Register with Latched 3-State Outputs")
      (fields (field (name "PUBLISHER") "Altium Limited"))
      (libsource (lib "PCB_Project") (part "74HC595"))
    )
    (comp (ref "U5")
      (value "74HC595")
      (footprint "SO-16_N")
      (description "8-Bit Serial-Input/Serial-or-Parallel-Output Shift Register with Latched 3-State Outputs")
      (fields (field (name "PUBLISHER") "Altium Limited"))
      (libsource (lib "PCB_Project") (part "74HC595"))
    )
    (comp (ref "U6")
      (value "74HC595")
      (footprint "SO-16_N")
      (description "8-Bit Serial-Input/Serial-or-Parallel-Output Shift Register with Latched 3-State Outputs")
      (fields (field (name "PUBLISHER") "Altium Limited"))
      (libsource (lib "PCB_Project") (part "74HC595"))
    )
    (comp (ref "U7")
      (value "74HC595")
      (footprint "SO-16_N")
      (description "8-Bit Serial-Input/Serial-or-Parallel-Output Shift Register with Latched 3-State Outputs")
      (fields (field (name "PUBLISHER") "Altium Limited"))
      (libsource (lib "PCB_Project") (part "74HC595"))
    )
    (comp (ref "U8")
      (value "74HC595")
      (footprint "SO-16_N")
      (description "8-Bit Serial-Input/Serial-or-Parallel-Output Shift Register with Latched 3-State Outputs")
      (fields (field (name "PUBLISHER") "Altium Limited"))
      (libsource (lib "PCB_Project") (part "74HC595"))
    )
    (comp (ref "U9")
      (value "74HC595")
      (footprint "SO-16_N")
      (description "8-Bit Serial-Input/Serial-or-Parallel-Output Shift Register with Latched 3-State Outputs")
      (fields (field (name "PUBLISHER") "Altium Limited"))
      (libsource (lib "PCB_Project") (part "74HC595"))
    )
    (comp (ref "U10")
      (value "74HC595")
      (footprint "SO-16_N")
      (description "8-Bit Serial-Input/Serial-or-Parallel-Output Shift Register with Latched 3-State Outputs")
      (fields (field (name "PUBLISHER") "Altium Limited"))
      (libsource (lib "PCB_Project") (part "74HC595"))
    )
    (comp (ref "U11")
      (value "74HC595")
      (footprint "SO-16_N")
      (description "8-Bit Serial-Input/Serial-or-Parallel-Output Shift Register with Latched 3-State Outputs")
      (fields (field (name "PUBLISHER") "Altium Limited"))
      (libsource (lib "PCB_Project") (part "74HC595"))
    )
    (comp (ref "U12")
      (value "74HC595")
      (footprint "SO-16_N")
      (description "8-Bit Serial-Input/Serial-or-Parallel-Output Shift Register with Latched 3-State Outputs")
      (fields (field (name "PUBLISHER") "Altium Limited"))
      (libsource (lib "PCB_Project") (part "74HC595"))
    )
    (comp (ref "U13")
      (value "74HC595")
      (footprint "SO-16_N")
      (description "8-Bit Serial-Input/Serial-or-Parallel-Output Shift Register with Latched 3-State Outputs")
      (fields (field (name "PUBLISHER") "Altium Limited"))
      (libsource (lib "PCB_Project") (part "74HC595"))
    )
    (comp (ref "U14")
      (value "IR2153S")
      (footprint "SO-8_M")
      (description "Self-Oscillating Half-Bridge Driver")
      (fields (field (name "PUBLISHER") "Altium Limited"))
      (libsource (lib "IR Interface Bridge Driver") (part "IR2153S"))
    )
    (comp (ref "U15") (value "MP2307") (footprint "SO8_M") (libsource (lib "Schlib1") (part "MP2307")))
    (comp (ref "U16")
      (value "MC74HC14AD")
      (footprint "751A-02_N")
      (description "Hex Schmitt Trigger Inverter")
      (fields (field (name "PUBLISHER") "Altium Limited"))
      (libsource (lib "Motorola Logic Gate") (part "MC74HC14AD"))
    )
    (comp (ref "U17") (value "DS3231") (footprint "ADI-RW-16_M") (libsource (lib "Schlib1") (part "DS3231")))
    (comp (ref "U18")
      (value "STM32F103C8T6TR")
      (footprint "STM-LQFP48_N")
      (libsource (lib "") (part "STM32F103C8T6TR_1"))
    )
    (comp (ref "VD8")
      (value "White")
      (footprint "LED 3.1x1.4mm Duris E3")
      (description "30mA 1.94-2.8cd (20ma)")
      (libsource (lib "Ind LED-LCD") (part "LED 3x1.4mm Duris E3"))
    )
    (comp (ref "VD9")
      (value "White")
      (footprint "LED 3.1x1.4mm Duris E3")
      (description "30mA 1.94-2.8cd (20ma)")
      (libsource (lib "Ind LED-LCD") (part "LED 3x1.4mm Duris E3"))
    )
    (comp (ref "VD10")
      (value "White")
      (footprint "LED 3.1x1.4mm Duris E3")
      (description "30mA 1.94-2.8cd (20ma)")
      (libsource (lib "Ind LED-LCD") (part "LED 3x1.4mm Duris E3"))
    )
    (comp (ref "VD11")
      (value "Green")
      (footprint "C1210")
      (description "Green 565nm 15mcd")
      (libsource (lib "Ind LED-LCD") (part "Led 0805 KP-2012SGC"))
    )
    (comp (ref "VD12")
      (value "Green")
      (footprint "C1210")
      (description "Green 565nm 15mcd")
      (libsource (lib "Ind LED-LCD") (part "Led 0805 KP-2012SGC"))
    )
    (comp (ref "VL1") (value "IN-15B") (footprint "IN-12") (libsource (lib "PCB_Project_4") (part "IN-15B")))
    (comp (ref "VL2") (value "IN-18") (footprint "IN-18") (libsource (lib "PCB_Project_4") (part "IN-18")))
    (comp (ref "VL3") (value "IN-18") (footprint "IN-18") (libsource (lib "PCB_Project_4") (part "IN-18")))
    (comp (ref "VL4") (value "H-2x4") (footprint "J2x4") (libsource (lib "Connektor") (part "H-2x4")))
    (comp (ref "VL5") (value "IN-18") (footprint "IN-18") (libsource (lib "PCB_Project_4") (part "IN-18")))
    (comp (ref "VL6") (value "IN-18") (footprint "IN-18") (libsource (lib "PCB_Project_4") (part "IN-18")))
    (comp (ref "VL7") (value "H-2x4") (footprint "J2x4") (libsource (lib "Connektor") (part "H-2x4")))
    (comp (ref "VL8") (value "IN-18") (footprint "IN-18") (libsource (lib "PCB_Project_4") (part "IN-18")))
    (comp (ref "VL9") (value "IN-18") (footprint "IN-18") (libsource (lib "PCB_Project_4") (part "IN-18")))
    (comp (ref "ZQ1") (value "8MHz") (footprint "HC49S") (libsource (lib "Devise") (part "Q")))
  )
  (nets
    (net (code "1") (name "GND") (class "Default")
      (node (ref "Bu1") (pin "1") (pinfunction "-_1") (pintype "passive"))
      (node (ref "C1") (pin "2") (pinfunction "2_2") (pintype "passive"))
      (node (ref "C10") (pin "1") (pinfunction "1_1") (pintype "passive"))
      (node (ref "C11") (pin "1") (pinfunction "1_1") (pintype "passive"))
      (node (ref "C12") (pin "1") (pinfunction "1_1") (pintype "passive"))
      (node (ref "C13") (pin "1") (pinfunction "1_1") (pintype "passive"))
      (node (ref "C14") (pin "1") (pinfunction "1_1") (pintype "passive"))
      (node (ref "C15") (pin "1") (pinfunction "1_1") (pintype "passive"))
      (node (ref "C16") (pin "2") (pinfunction "2_2") (pintype "passive"))
      (node (ref "C17") (pin "2") (pinfunction "2_2") (pintype "passive"))
      (node (ref "C18") (pin "2") (pinfunction "2_2") (pintype "passive"))
      (node (ref "C19") (pin "2") (pinfunction "2_2") (pintype "passive"))
      (node (ref "C20") (pin "2") (pinfunction "2_2") (pintype "passive"))
      (node (ref "C22") (pin "2") (pinfunction "2_2") (pintype "passive"))
      (node (ref "C23") (pin "1") (pinfunction "1_1") (pintype "passive"))
      (node (ref "C24") (pin "2") (pinfunction "2_2") (pintype "passive"))
      (node (ref "C25") (pin "2") (pinfunction "2_2") (pintype "passive"))
      (node (ref "C26") (pin "2") (pinfunction "2_2") (pintype "passive"))
      (node (ref "C28") (pin "2") (pinfunction "2_2") (pintype "passive"))
      (node (ref "C29") (pin "2") (pinfunction "2_2") (pintype "passive"))
      (node (ref "C3") (pin "1") (pinfunction "1_1") (pintype "passive"))
      (node (ref "C30") (pin "1") (pinfunction "1_1") (pintype "passive"))
      (node (ref "C31") (pin "2") (pinfunction "2_2") (pintype "passive"))
      (node (ref "C32") (pin "1") (pinfunction "1_1") (pintype "passive"))
      (node (ref "C33") (pin "1") (pinfunction "1_1") (pintype "passive"))
      (node (ref "C34") (pin "1") (pinfunction "1_1") (pintype "passive"))
      (node (ref "C35") (pin "1") (pinfunction "1_1") (pintype "passive"))
      (node (ref "C36") (pin "2") (pinfunction "2_2") (pintype "passive"))
      (node (ref "C37") (pin "2") (pinfunction "2_2") (pintype "passive"))
      (node (ref "C38") (pin "2") (pinfunction "2_2") (pintype "passive"))
      (node (ref "C39") (pin "2") (pinfunction "2_2") (pintype "passive"))
      (node (ref "C4") (pin "1") (pinfunction "1_1") (pintype "passive"))
      (node (ref "C40") (pin "2") (pinfunction "2_2") (pintype "passive"))
      (node (ref "C41") (pin "1") (pinfunction "1_1") (pintype "passive"))
      (node (ref "C42") (pin "1") (pinfunction "1_1") (pintype "passive"))
      (node (ref "C43") (pin "1") (pinfunction "1_1") (pintype "passive"))
      (node (ref "C44") (pin "1") (pinfunction "1_1") (pintype "passive"))
      (node (ref "C45") (pin "2") (pinfunction "2_2") (pintype "passive"))
      (node (ref "C46") (pin "1") (pinfunction "1_1") (pintype "passive"))
      (node (ref "C5") (pin "1") (pinfunction "1_1") (pintype "passive"))
      (node (ref "C6") (pin "1") (pinfunction "1_1") (pintype "passive"))
      (node (ref "C7") (pin "1") (pinfunction "1_1") (pintype "passive"))
      (node (ref "C8") (pin "1") (pinfunction "1_1") (pintype "passive"))
      (node (ref "C9") (pin "1") (pinfunction "1_1") (pintype "passive"))
      (node (ref "D7") (pin "1") (pinfunction "A_1") (pintype "passive"))
      (node (ref "GPS") (pin "10") (pinfunction "GND_10") (pintype "passive"))
      (node (ref "GPS") (pin "11") (pinfunction "GND_11") (pintype "passive"))
      (node (ref "GPS") (pin "12") (pinfunction "GND_12") (pintype "passive"))
      (node (ref "GPS") (pin "4") (pinfunction "GND_4") (pintype "passive"))
      (node (ref "GPS") (pin "5") (pinfunction "GND_5") (pintype "passive"))
      (node (ref "GPS") (pin "6") (pinfunction "GND_6") (pintype "passive"))
      (node (ref "GPS") (pin "7") (pinfunction "GND_7") (pintype "passive"))
      (node (ref "GPS") (pin "8") (pinfunction "GND_8") (pintype "passive"))
      (node (ref "GPS") (pin "9") (pinfunction "GND_9") (pintype "passive"))
      (node (ref "J1") (pin "1") (pinfunction "1_1") (pintype "passive"))
      (node (ref "J1") (pin "2") (pinfunction "2_2") (pintype "passive"))
      (node (ref "J2") (pin "1") (pinfunction "1_1") (pintype "passive"))
      (node (ref "LDR1") (pin "1") (pinfunction "1_1") (pintype "passive"))
      (node (ref "Q1") (pin "2") (pinfunction "E_2") (pintype "passive"))
      (node (ref "Q10") (pin "2") (pinfunction "E_2") (pintype "passive"))
      (node (ref "Q11") (pin "2") (pinfunction "E_2") (pintype "passive"))
      (node (ref "Q12") (pin "2") (pinfunction "E_2") (pintype "passive"))
      (node (ref "Q13") (pin "2") (pinfunction "E_2") (pintype "passive"))
      (node (ref "Q14") (pin "2") (pinfunction "E_2") (pintype "passive"))
      (node (ref "Q15") (pin "2") (pinfunction "E_2") (pintype "passive"))
      (node (ref "Q16") (pin "2") (pinfunction "E_2") (pintype "passive"))
      (node (ref "Q17") (pin "2") (pinfunction "E_2") (pintype "passive"))
      (node (ref "Q18") (pin "2") (pinfunction "E_2") (pintype "passive"))
      (node (ref "Q19") (pin "2") (pinfunction "E_2") (pintype "passive"))
      (node (ref "Q2") (pin "2") (pinfunction "E_2") (pintype "passive"))
      (node (ref "Q20") (pin "2") (pinfunction "E_2") (pintype "passive"))
      (node (ref "Q21") (pin "2") (pinfunction "E_2") (pintype "passive"))
      (node (ref "Q22") (pin "2") (pinfunction "E_2") (pintype "passive"))
      (node (ref "Q23") (pin "2") (pinfunction "E_2") (pintype "passive"))
      (node (ref "Q24") (pin "2") (pinfunction "E_2") (pintype "passive"))
      (node (ref "Q25") (pin "2") (pinfunction "E_2") (pintype "passive"))
      (node (ref "Q26") (pin "2") (pinfunction "E_2") (pintype "passive"))
      (node (ref "Q27") (pin "2") (pinfunction "E_2") (pintype "passive"))
      (node (ref "Q28") (pin "2") (pinfunction "E_2") (pintype "passive"))
      (node (ref "Q29") (pin "2") (pinfunction "E_2") (pintype "passive"))
      (node (ref "Q3") (pin "2") (pinfunction "E_2") (pintype "passive"))
      (node (ref "Q30") (pin "2") (pinfunction "E_2") (pintype "passive"))
      (node (ref "Q31") (pin "2") (pinfunction "E_2") (pintype "passive"))
      (node (ref "Q32") (pin "2") (pinfunction "E_2") (pintype "passive"))
      (node (ref "Q33") (pin "2") (pinfunction "E_2") (pintype "passive"))
      (node (ref "Q34") (pin "2") (pinfunction "E_2") (pintype "passive"))
      (node (ref "Q35") (pin "2") (pinfunction "E_2") (pintype "passive"))
      (node (ref "Q36") (pin "2") (pinfunction "E_2") (pintype "passive"))
      (node (ref "Q37") (pin "2") (pinfunction "E_2") (pintype "passive"))
      (node (ref "Q38") (pin "2") (pinfunction "E_2") (pintype "passive"))
      (node (ref "Q39") (pin "2") (pinfunction "E_2") (pintype "passive"))
      (node (ref "Q4") (pin "2") (pinfunction "E_2") (pintype "passive"))
      (node (ref "Q40") (pin "2") (pinfunction "E_2") (pintype "passive"))
      (node (ref "Q41") (pin "2") (pinfunction "E_2") (pintype "passive"))
      (node (ref "Q42") (pin "2") (pinfunction "E_2") (pintype "passive"))
      (node (ref "Q43") (pin "2") (pinfunction "E_2") (pintype "passive"))
      (node (ref "Q44") (pin "2") (pinfunction "E_2") (pintype "passive"))
      (node (ref "Q45") (pin "2") (pinfunction "E_2") (pintype "passive"))
      (node (ref "Q46") (pin "2") (pinfunction "E_2") (pintype "passive"))
      (node (ref "Q47") (pin "2") (pinfunction "E_2") (pintype "passive"))
      (node (ref "Q48") (pin "2") (pinfunction "E_2") (pintype "passive"))
      (node (ref "Q49") (pin "2") (pinfunction "E_2") (pintype "passive"))
      (node (ref "Q5") (pin "2") (pinfunction "E_2") (pintype "passive"))
      (node (ref "Q50") (pin "2") (pinfunction "E_2") (pintype "passive"))
      (node (ref "Q51") (pin "2") (pinfunction "E_2") (pintype "passive"))
      (node (ref "Q52") (pin "2") (pinfunction "E_2") (pintype "passive"))
      (node (ref "Q53") (pin "2") (pinfunction "E_2") (pintype "passive"))
      (node (ref "Q54") (pin "2") (pinfunction "E_2") (pintype "passive"))
      (node (ref "Q55") (pin "2") (pinfunction "E_2") (pintype "passive"))
      (node (ref "Q56") (pin "2") (pinfunction "E_2") (pintype "passive"))
      (node (ref "Q57") (pin "2") (pinfunction "E_2") (pintype "passive"))
      (node (ref "Q58") (pin "2") (pinfunction "E_2") (pintype "passive"))
      (node (ref "Q59") (pin "2") (pinfunction "E_2") (pintype "passive"))
      (node (ref "Q6") (pin "2") (pinfunction "E_2") (pintype "passive"))
      (node (ref "Q60") (pin "2") (pinfunction "E_2") (pintype "passive"))
      (node (ref "Q61") (pin "2") (pinfunction "E_2") (pintype "passive"))
      (node (ref "Q62") (pin "2") (pinfunction "E_2") (pintype "passive"))
      (node (ref "Q63") (pin "2") (pinfunction "E_2") (pintype "passive"))
      (node (ref "Q64") (pin "2") (pinfunction "E_2") (pintype "passive"))
      (node (ref "Q65") (pin "3") (pinfunction "S_3") (pintype "passive"))
      (node (ref "Q66") (pin "3") (pinfunction "S_3") (pintype "passive"))
      (node (ref "Q69") (pin "3") (pinfunction "S_3") (pintype "passive"))
      (node (ref "Q7") (pin "2") (pinfunction "E_2") (pintype "passive"))
      (node (ref "Q8") (pin "2") (pinfunction "E_2") (pintype "passive"))
      (node (ref "Q9") (pin "2") (pinfunction "E_2") (pintype "passive"))
      (node (ref "R111") (pin "1") (pinfunction "1_1") (pintype "passive"))
      (node (ref "R115") (pin "1") (pinfunction "1_1") (pintype "passive"))
      (node (ref "R127") (pin "2") (pinfunction "2_2") (pintype "passive"))
      (node (ref "R129") (pin "2") (pinfunction "2_2") (pintype "passive"))
      (node (ref "R130") (pin "2") (pinfunction "2_2") (pintype "passive"))
      (node (ref "R131") (pin "2") (pinfunction "2_2") (pintype "passive"))
      (node (ref "R133") (pin "2") (pinfunction "2_2") (pintype "passive"))
      (node (ref "R138") (pin "2") (pinfunction "2_2") (pintype "passive"))
      (node (ref "R139") (pin "1") (pinfunction "1_1") (pintype "passive"))
      (node (ref "R140") (pin "2") (pinfunction "2_2") (pintype "passive"))
      (node (ref "R141") (pin "2") (pinfunction "2_2") (pintype "passive"))
      (node (ref "R142") (pin "2") (pinfunction "2_2") (pintype "passive"))
      (node (ref "R143") (pin "2") (pinfunction "2_2") (pintype "passive"))
      (node (ref "R144") (pin "2") (pinfunction "2_2") (pintype "passive"))
      (node (ref "R145") (pin "2") (pinfunction "2_2") (pintype "passive"))
      (node (ref "R146") (pin "2") (pinfunction "2_2") (pintype "passive"))
      (node (ref "R147") (pin "2") (pinfunction "2_2") (pintype "passive"))
      (node (ref "R148") (pin "2") (pinfunction "2_2") (pintype "passive"))
      (node (ref "R149") (pin "2") (pinfunction "2_2") (pintype "passive"))
      (node (ref "R150") (pin "2") (pinfunction "2_2") (pintype "passive"))
      (node (ref "R151") (pin "2") (pinfunction "2_2") (pintype "passive"))
      (node (ref "R152") (pin "2") (pinfunction "2_2") (pintype "passive"))
      (node (ref "R153") (pin "2") (pinfunction "2_2") (pintype "passive"))
      (node (ref "R154") (pin "2") (pinfunction "2_2") (pintype "passive"))
      (node (ref "R155") (pin "2") (pinfunction "2_2") (pintype "passive"))
      (node (ref "R156") (pin "2") (pinfunction "2_2") (pintype "passive"))
      (node (ref "R157") (pin "2") (pinfunction "2_2") (pintype "passive"))
      (node (ref "R158") (pin "2") (pinfunction "2_2") (pintype "passive"))
      (node (ref "R159") (pin "2") (pinfunction "2_2") (pintype "passive"))
      (node (ref "R160") (pin "2") (pinfunction "2_2") (pintype "passive"))
      (node (ref "R161") (pin "2") (pinfunction "2_2") (pintype "passive"))
      (node (ref "R162") (pin "2") (pinfunction "2_2") (pintype "passive"))
      (node (ref "R163") (pin "2") (pinfunction "2_2") (pintype "passive"))
      (node (ref "R164") (pin "2") (pinfunction "2_2") (pintype "passive"))
      (node (ref "R165") (pin "2") (pinfunction "2_2") (pintype "passive"))
      (node (ref "R166") (pin "2") (pinfunction "2_2") (pintype "passive"))
      (node (ref "R167") (pin "2") (pinfunction "2_2") (pintype "passive"))
      (node (ref "R168") (pin "2") (pinfunction "2_2") (pintype "passive"))
      (node (ref "R169") (pin "2") (pinfunction "2_2") (pintype "passive"))
      (node (ref "R170") (pin "2") (pinfunction "2_2") (pintype "passive"))
      (node (ref "R171") (pin "2") (pinfunction "2_2") (pintype "passive"))
      (node (ref "R172") (pin "2") (pinfunction "2_2") (pintype "passive"))
      (node (ref "R173") (pin "2") (pinfunction "2_2") (pintype "passive"))
      (node (ref "R174") (pin "2") (pinfunction "2_2") (pintype "passive"))
      (node (ref "R175") (pin "2") (pinfunction "2_2") (pintype "passive"))
      (node (ref "R176") (pin "2") (pinfunction "2_2") (pintype "passive"))
      (node (ref "R177") (pin "2") (pinfunction "2_2") (pintype "passive"))
      (node (ref "R178") (pin "2") (pinfunction "2_2") (pintype "passive"))
      (node (ref "R179") (pin "2") (pinfunction "2_2") (pintype "passive"))
      (node (ref "R180") (pin "2") (pinfunction "2_2") (pintype "passive"))
      (node (ref "R181") (pin "2") (pinfunction "2_2") (pintype "passive"))
      (node (ref "R182") (pin "2") (pinfunction "2_2") (pintype "passive"))
      (node (ref "R183") (pin "2") (pinfunction "2_2") (pintype "passive"))
      (node (ref "R184") (pin "2") (pinfunction "2_2") (pintype "passive"))
      (node (ref "R185") (pin "2") (pinfunction "2_2") (pintype "passive"))
      (node (ref "R186") (pin "2") (pinfunction "2_2") (pintype "passive"))
      (node (ref "R187") (pin "2") (pinfunction "2_2") (pintype "passive"))
      (node (ref "R188") (pin "2") (pinfunction "2_2") (pintype "passive"))
      (node (ref "R189") (pin "2") (pinfunction "2_2") (pintype "passive"))
      (node (ref "R190") (pin "2") (pinfunction "2_2") (pintype "passive"))
      (node (ref "R191") (pin "2") (pinfunction "2_2") (pintype "passive"))
      (node (ref "R192") (pin "2") (pinfunction "2_2") (pintype "passive"))
      (node (ref "R193") (pin "2") (pinfunction "2_2") (pintype "passive"))
      (node (ref "R194") (pin "2") (pinfunction "2_2") (pintype "passive"))
      (node (ref "R195") (pin "2") (pinfunction "2_2") (pintype "passive"))
      (node (ref "R196") (pin "2") (pinfunction "2_2") (pintype "passive"))
      (node (ref "R197") (pin "2") (pinfunction "2_2") (pintype "passive"))
      (node (ref "R198") (pin "2") (pinfunction "2_2") (pintype "passive"))
      (node (ref "R199") (pin "2") (pinfunction "2_2") (pintype "passive"))
      (node (ref "R200") (pin "2") (pinfunction "2_2") (pintype "passive"))
      (node (ref "U1") (pin "8") (pinfunction "GND_8") (pintype "power_in"))
      (node (ref "U10") (pin "8") (pinfunction "GND_8") (pintype "power_in"))
      (node (ref "U11") (pin "8") (pinfunction "GND_8") (pintype "power_in"))
      (node (ref "U12") (pin "8") (pinfunction "GND_8") (pintype "power_in"))
      (node (ref "U13") (pin "8") (pinfunction "GND_8") (pintype "power_in"))
      (node (ref "U14") (pin "4") (pinfunction "COM_4") (pintype "power_in"))
      (node (ref "U14") (pin "6") (pinfunction "VS_6") (pintype "power_in"))
      (node (ref "U15") (pin "4") (pinfunction "GND_4") (pintype "passive"))
      (node (ref "U16") (pin "7") (pinfunction "GND_7") (pintype "power_in"))
      (node (ref "U17") (pin "10") (pinfunction "NC_10") (pintype "passive"))
      (node (ref "U17") (pin "11") (pinfunction "NC_11") (pintype "passive"))
      (node (ref "U17") (pin "12") (pinfunction "NC_12") (pintype "passive"))
      (node (ref "U17") (pin "13") (pinfunction "GND_13") (pintype "passive"))
      (node (ref "U17") (pin "5") (pinfunction "NC_5") (pintype "passive"))
      (node (ref "U17") (pin "6") (pinfunction "NC_6") (pintype "passive"))
      (node (ref "U17") (pin "7") (pinfunction "NC_7") (pintype "passive"))
      (node (ref "U17") (pin "8") (pinfunction "NC_8") (pintype "passive"))
      (node (ref "U17") (pin "9") (pinfunction "NC_9") (pintype "passive"))
      (node (ref "U18") (pin "23") (pinfunction "VSS_1_23") (pintype "power_in"))
      (node (ref "U18") (pin "35") (pinfunction "VSS_2_35") (pintype "power_in"))
      (node (ref "U18") (pin "47") (pinfunction "VSS_3_47") (pintype "power_in"))
      (node (ref "U18") (pin "8") (pinfunction "VSSA_8") (pintype "power_in"))
      (node (ref "U2") (pin "8") (pinfunction "GND_8") (pintype "power_in"))
      (node (ref "U3") (pin "8") (pinfunction "GND_8") (pintype "power_in"))
      (node (ref "U4") (pin "8") (pinfunction "GND_8") (pintype "power_in"))
      (node (ref "U5") (pin "8") (pinfunction "GND_8") (pintype "power_in"))
      (node (ref "U6") (pin "8") (pinfunction "GND_8") (pintype "power_in"))
      (node (ref "U7") (pin "8") (pinfunction "GND_8") (pintype "power_in"))
      (node (ref "U8") (pin "8") (pinfunction "GND_8") (pintype "power_in"))
      (node (ref "U9") (pin "8") (pinfunction "GND_8") (pintype "power_in"))
      (node (ref "VD12") (pin "2") (pinfunction "K_2") (pintype "passive"))
      (node (ref "VD9") (pin "2") (pinfunction "K_2") (pintype "passive"))
    )
    (net (code "2") (name "Net-(Bu1-+)") (class "Default")
      (node (ref "Bu1") (pin "2") (pinfunction "+_2") (pintype "passive"))
      (node (ref "Q68") (pin "2") (pinfunction "D_2") (pintype "passive"))
    )
    (net (code "3") (name "Net-(C1-Pad1)") (class "Default")
      (node (ref "C1") (pin "1") (pinfunction "1_1") (pintype "passive"))
      (node (ref "R1") (pin "2") (pinfunction "2_2") (pintype "passive"))
      (node (ref "R104") (pin "2") (pinfunction "2_2") (pintype "passive"))
      (node (ref "R137") (pin "1") (pinfunction "1_1") (pintype "passive"))
      (node (ref "R2") (pin "2") (pinfunction "2_2") (pintype "passive"))
      (node (ref "R21") (pin "1") (pinfunction "1_1") (pintype "passive"))
      (node (ref "R23") (pin "1") (pinfunction "1_1") (pintype "passive"))
      (node (ref "R25") (pin "1") (pinfunction "1_1") (pintype "passive"))
      (node (ref "R27") (pin "1") (pinfunction "1_1") (pintype "passive"))
      (node (ref "R29") (pin "1") (pinfunction "1_1") (pintype "passive"))
      (node (ref "R31") (pin "1") (pinfunction "1_1") (pintype "passive"))
      (node (ref "R34") (pin "2") (pinfunction "2_2") (pintype "passive"))
    )
    (net (code "4") (name "Net-(C24-Pad1)") (class "Default")
      (node (ref "C24") (pin "1") (pinfunction "1_1") (pintype "passive"))
      (node (ref "R113") (pin "1") (pinfunction "1_1") (pintype "passive"))
    )
    (net (code "5") (name "Net-(C31-Pad1)") (class "Default")
      (node (ref "C31") (pin "1") (pinfunction "1_1") (pintype "passive"))
      (node (ref "R120") (pin "2") (pinfunction "2_2") (pintype "passive"))
      (node (ref "SB4") (pin "2") (pinfunction "2_2") (pintype "passive"))
    )
    (net (code "6") (name "Net-(C37-Pad1)") (class "Default")
      (node (ref "C37") (pin "1") (pinfunction "1_1") (pintype "passive"))
      (node (ref "FB1") (pin "2") (pinfunction "2_2") (pintype "passive"))
      (node (ref "FB2") (pin "1") (pinfunction "1_1") (pintype "passive"))
    )
    (net (code "7") (name "Net-(D1-A)") (class "Default")
      (node (ref "D1") (pin "1") (pinfunction "A_1") (pintype "passive"))
      (node (ref "D4") (pin "2") (pinfunction "K_2") (pintype "passive"))
      (node (ref "Tr1") (pin "5") (pinfunction "5_5") (pintype "passive"))
    )
    (net (code "8") (name "Net-(D1-K)") (class "Default")
      (node (ref "C20") (pin "1") (pinfunction "1_1") (pintype "passive"))
      (node (ref "D1") (pin "2") (pinfunction "K_2") (pintype "passive"))
      (node (ref "D5") (pin "2") (pinfunction "K_2") (pintype "passive"))
      (node (ref "R137") (pin "2") (pinfunction "2_2") (pintype "passive"))
    )
    (net (code "9") (name "Net-(D2-A)") (class "Default")
      (node (ref "D2") (pin "1") (pinfunction "A_1") (pintype "passive"))
      (node (ref "Q66") (pin "2") (pinfunction "D_2") (pintype "passive"))
      (node (ref "Tr1") (pin "3") (pinfunction "3_3") (pintype "passive"))
    )
    (net (code "10") (name "Net-(D2-K)") (class "Default")
      (node (ref "C19") (pin "1") (pinfunction "1_1") (pintype "passive"))
      (node (ref "D2") (pin "2") (pinfunction "K_2") (pintype "passive"))
      (node (ref "D3") (pin "2") (pinfunction "K_2") (pintype "passive"))
      (node (ref "D4") (pin "1") (pinfunction "A_1") (pintype "passive"))
      (node (ref "D6") (pin "1") (pinfunction "A_1") (pintype "passive"))
    )
    (net (code "11") (name "Net-(D3-A)") (class "Default")
      (node (ref "D3") (pin "1") (pinfunction "A_1") (pintype "passive"))
      (node (ref "Q65") (pin "2") (pinfunction "D_2") (pintype "passive"))
      (node (ref "Tr1") (pin "1") (pinfunction "1_1") (pintype "passive"))
    )
    (net (code "12") (name "Net-(D5-A)") (class "Default")
      (node (ref "D5") (pin "1") (pinfunction "A_1") (pintype "passive"))
      (node (ref "D6") (pin "2") (pinfunction "K_2") (pintype "passive"))
      (node (ref "Tr1") (pin "4") (pinfunction "4_4") (pintype "passive"))
    )
    (net (code "13") (name "Net-(D7-C)") (class "Default")
      (node (ref "C16") (pin "1") (pinfunction "1_1") (pintype "passive"))
      (node (ref "C23") (pin "2") (pinfunction "2_2") (pintype "passive"))
      (node (ref "D7") (pin "2") (pinfunction "C_2") (pintype "passive"))
      (node (ref "F1") (pin "2") (pinfunction "2_2") (pintype "passive"))
      (node (ref "R112") (pin "1") (pinfunction "1_1") (pintype "passive"))
      (node (ref "R116") (pin "2") (pinfunction "2_2") (pintype "passive"))
      (node (ref "R136") (pin "2") (pinfunction "2_2") (pintype "passive"))
      (node (ref "Tr1") (pin "2") (pinfunction "2_2") (pintype "passive"))
      (node (ref "U15") (pin "2") (pinfunction "IN_2") (pintype "passive"))
    )
    (net (code "14") (name "Net-(F1-Pad1)") (class "Default")
      (node (ref "F1") (pin "1") (pinfunction "1_1") (pintype "passive"))
      (node (ref "J1") (pin "3") (pinfunction "3_3") (pintype "passive"))
    )
    (net (code "15") (name "Net-(GPS-Rx)") (class "Default")
      (node (ref "GPS") (pin "1") (pinfunction "Rx_1") (pintype "passive"))
      (node (ref "U18") (pin "30") (pinfunction "PA9_30") (pintype "bidirectional"))
    )
    (net (code "16") (name "Net-(GPS-Tx)") (class "Default")
      (node (ref "GPS") (pin "2") (pinfunction "Tx_2") (pintype "passive"))
      (node (ref "U18") (pin "31") (pinfunction "PA10_31") (pintype "bidirectional"))
    )
    (net (code "17") (name "Net-(GPS-Vcc)") (class "Default")
      (node (ref "C38") (pin "1") (pinfunction "1_1") (pintype "passive"))
      (node (ref "FB2") (pin "2") (pinfunction "2_2") (pintype "passive"))
      (node (ref "GPS") (pin "3") (pinfunction "Vcc_3") (pintype "passive"))
      (node (ref "R134") (pin "1") (pinfunction "1_1") (pintype "passive"))
      (node (ref "R135") (pin "2") (pinfunction "2_2") (pintype "passive"))
    )
    (net (code "18") (name "Net-(LDR1-Pad2)") (class "Default")
      (node (ref "LDR1") (pin "2") (pinfunction "2_2") (pintype "passive"))
      (node (ref "R132") (pin "1") (pinfunction "1_1") (pintype "passive"))
      (node (ref "R135") (pin "1") (pinfunction "1_1") (pintype "passive"))
    )
    (net (code "19") (name "Net-(Q1-B)") (class "Default")
      (node (ref "Q1") (pin "1") (pinfunction "B_1") (pintype "passive"))
      (node (ref "R141") (pin "1") (pinfunction "1_1") (pintype "passive"))
      (node (ref "R35") (pin "1") (pinfunction "1_1") (pintype "passive"))
    )
    (net (code "20") (name "Net-(Q1-C)") (class "Default")
      (node (ref "Q1") (pin "3") (pinfunction "C_3") (pintype "passive"))
      (node (ref "VL2") (pin "5") (pinfunction "6_5") (pintype "passive"))
    )
    (net (code "21") (name "Net-(Q2-B)") (class "Default")
      (node (ref "Q2") (pin "1") (pinfunction "B_1") (pintype "passive"))
      (node (ref "R142") (pin "1") (pinfunction "1_1") (pintype "passive"))
      (node (ref "R36") (pin "1") (pinfunction "1_1") (pintype "passive"))
    )
    (net (code "22") (name "Net-(Q2-C)") (class "Default")
      (node (ref "Q2") (pin "3") (pinfunction "C_3") (pintype "passive"))
      (node (ref "VL2") (pin "6") (pinfunction "7_6") (pintype "passive"))
    )
    (net (code "23") (name "Net-(Q3-B)") (class "Default")
      (node (ref "Q3") (pin "1") (pinfunction "B_1") (pintype "passive"))
      (node (ref "R150") (pin "1") (pinfunction "1_1") (pintype "passive"))
      (node (ref "R37") (pin "1") (pinfunction "1_1") (pintype "passive"))
    )
    (net (code "24") (name "Net-(Q3-C)") (class "Default")
      (node (ref "Q3") (pin "3") (pinfunction "C_3") (pintype "passive"))
      (node (ref "VL2") (pin "3") (pinfunction "5_3") (pintype "passive"))
    )
    (net (code "25") (name "Net-(Q4-B)") (class "Default")
      (node (ref "Q4") (pin "1") (pinfunction "B_1") (pintype "passive"))
      (node (ref "R149") (pin "1") (pinfunction "1_1") (pintype "passive"))
      (node (ref "R38") (pin "1") (pinfunction "1_1") (pintype "passive"))
    )
    (net (code "26") (name "Net-(Q4-C)") (class "Default")
      (node (ref "Q4") (pin "3") (pinfunction "C_3") (pintype "passive"))
      (node (ref "VL2") (pin "2") (pinfunction "4_2") (pintype "passive"))
    )
    (net (code "27") (name "Net-(Q5-B)") (class "Default")
      (node (ref "Q5") (pin "1") (pinfunction "B_1") (pintype "passive"))
      (node (ref "R151") (pin "1") (pinfunction "1_1") (pintype "passive"))
      (node (ref "R39") (pin "1") (pinfunction "1_1") (pintype "passive"))
    )
    (net (code "28") (name "Net-(Q5-C)") (class "Default")
      (node (ref "Q5") (pin "3") (pinfunction "C_3") (pintype "passive"))
      (node (ref "VL3") (pin "5") (pinfunction "6_5") (pintype "passive"))
    )
    (net (code "29") (name "Net-(Q6-B)") (class "Default")
      (node (ref "Q6") (pin "1") (pinfunction "B_1") (pintype "passive"))
      (node (ref "R152") (pin "1") (pinfunction "1_1") (pintype "passive"))
      (node (ref "R40") (pin "1") (pinfunction "1_1") (pintype "passive"))
    )
    (net (code "30") (name "Net-(Q6-C)") (class "Default")
      (node (ref "Q6") (pin "3") (pinfunction "C_3") (pintype "passive"))
      (node (ref "VL3") (pin "6") (pinfunction "7_6") (pintype "passive"))
    )
    (net (code "31") (name "Net-(Q7-B)") (class "Default")
      (node (ref "Q7") (pin "1") (pinfunction "B_1") (pintype "passive"))
      (node (ref "R160") (pin "1") (pinfunction "1_1") (pintype "passive"))
      (node (ref "R41") (pin "1") (pinfunction "1_1") (pintype "passive"))
    )
    (net (code "32") (name "Net-(Q7-C)") (class "Default")
      (node (ref "Q7") (pin "3") (pinfunction "C_3") (pintype "passive"))
      (node (ref "VL3") (pin "3") (pinfunction "5_3") (pintype "passive"))
    )
    (net (code "33") (name "Net-(Q8-B)") (class "Default")
      (node (ref "Q8") (pin "1") (pinfunction "B_1") (pintype "passive"))
      (node (ref "R159") (pin "1") (pinfunction "1_1") (pintype "passive"))
      (node (ref "R42") (pin "1") (pinfunction "1_1") (pintype "passive"))
    )
    (net (code "34") (name "Net-(Q8-C)") (class "Default")
      (node (ref "Q8") (pin "3") (pinfunction "C_3") (pintype "passive"))
      (node (ref "VL3") (pin "2") (pinfunction "4_2") (pintype "passive"))
    )
    (net (code "35") (name "Net-(Q9-B)") (class "Default")
      (node (ref "Q9") (pin "1") (pinfunction "B_1") (pintype "passive"))
      (node (ref "R161") (pin "1") (pinfunction "1_1") (pintype "passive"))
      (node (ref "R43") (pin "1") (pinfunction "1_1") (pintype "passive"))
    )
    (net (code "36") (name "Net-(Q9-C)") (class "Default")
      (node (ref "Q9") (pin "3") (pinfunction "C_3") (pintype "passive"))
      (node (ref "VL5") (pin "5") (pinfunction "6_5") (pintype "passive"))
    )
    (net (code "37") (name "Net-(Q10-B)") (class "Default")
      (node (ref "Q10") (pin "1") (pinfunction "B_1") (pintype "passive"))
      (node (ref "R162") (pin "1") (pinfunction "1_1") (pintype "passive"))
      (node (ref "R44") (pin "1") (pinfunction "1_1") (pintype "passive"))
    )
    (net (code "38") (name "Net-(Q10-C)") (class "Default")
      (node (ref "Q10") (pin "3") (pinfunction "C_3") (pintype "passive"))
      (node (ref "VL5") (pin "6") (pinfunction "7_6") (pintype "passive"))
    )
    (net (code "39") (name "Net-(Q11-B)") (class "Default")
      (node (ref "Q11") (pin "1") (pinfunction "B_1") (pintype "passive"))
      (node (ref "R170") (pin "1") (pinfunction "1_1") (pintype "passive"))
      (node (ref "R45") (pin "1") (pinfunction "1_1") (pintype "passive"))
    )
    (net (code "40") (name "Net-(Q11-C)") (class "Default")
      (node (ref "Q11") (pin "3") (pinfunction "C_3") (pintype "passive"))
      (node (ref "VL5") (pin "3") (pinfunction "5_3") (pintype "passive"))
    )
    (net (code "41") (name "Net-(Q12-B)") (class "Default")
      (node (ref "Q12") (pin "1") (pinfunction "B_1") (pintype "passive"))
      (node (ref "R169") (pin "1") (pinfunction "1_1") (pintype "passive"))
      (node (ref "R46") (pin "1") (pinfunction "1_1") (pintype "passive"))
    )
    (net (code "42") (name "Net-(Q12-C)") (class "Default")
      (node (ref "Q12") (pin "3") (pinfunction "C_3") (pintype "passive"))
      (node (ref "VL5") (pin "2") (pinfunction "4_2") (pintype "passive"))
    )
    (net (code "43") (name "Net-(Q13-B)") (class "Default")
      (node (ref "Q13") (pin "1") (pinfunction "B_1") (pintype "passive"))
      (node (ref "R171") (pin "1") (pinfunction "1_1") (pintype "passive"))
      (node (ref "R47") (pin "1") (pinfunction "1_1") (pintype "passive"))
    )
    (net (code "44") (name "Net-(Q13-C)") (class "Default")
      (node (ref "Q13") (pin "3") (pinfunction "C_3") (pintype "passive"))
      (node (ref "VL6") (pin "5") (pinfunction "6_5") (pintype "passive"))
    )
    (net (code "45") (name "Net-(Q14-B)") (class "Default")
      (node (ref "Q14") (pin "1") (pinfunction "B_1") (pintype "passive"))
      (node (ref "R172") (pin "1") (pinfunction "1_1") (pintype "passive"))
      (node (ref "R48") (pin "1") (pinfunction "1_1") (pintype "passive"))
    )
    (net (code "46") (name "Net-(Q14-C)") (class "Default")
      (node (ref "Q14") (pin "3") (pinfunction "C_3") (pintype "passive"))
      (node (ref "VL6") (pin "6") (pinfunction "7_6") (pintype "passive"))
    )
    (net (code "47") (name "Net-(Q15-B)") (class "Default")
      (node (ref "Q15") (pin "1") (pinfunction "B_1") (pintype "passive"))
      (node (ref "R180") (pin "1") (pinfunction "1_1") (pintype "passive"))
      (node (ref "R49") (pin "1") (pinfunction "1_1") (pintype "passive"))
    )
    (net (code "48") (name "Net-(Q15-C)") (class "Default")
      (node (ref "Q15") (pin "3") (pinfunction "C_3") (pintype "passive"))
      (node (ref "VL6") (pin "3") (pinfunction "5_3") (pintype "passive"))
    )
    (net (code "49") (name "Net-(Q16-B)") (class "Default")
      (node (ref "Q16") (pin "1") (pinfunction "B_1") (pintype "passive"))
      (node (ref "R179") (pin "1") (pinfunction "1_1") (pintype "passive"))
      (node (ref "R50") (pin "1") (pinfunction "1_1") (pintype "passive"))
    )
    (net (code "50") (name "Net-(Q16-C)") (class "Default")
      (node (ref "Q16") (pin "3") (pinfunction "C_3") (pintype "passive"))
      (node (ref "VL6") (pin "2") (pinfunction "4_2") (pintype "passive"))
    )
    (net (code "51") (name "Net-(Q17-B)") (class "Default")
      (node (ref "Q17") (pin "1") (pinfunction "B_1") (pintype "passive"))
      (node (ref "R181") (pin "1") (pinfunction "1_1") (pintype "passive"))
      (node (ref "R51") (pin "1") (pinfunction "1_1") (pintype "passive"))
    )
    (net (code "52") (name "Net-(Q17-C)") (class "Default")
      (node (ref "Q17") (pin "3") (pinfunction "C_3") (pintype "passive"))
      (node (ref "VL8") (pin "5") (pinfunction "6_5") (pintype "passive"))
    )
    (net (code "53") (name "Net-(Q18-B)") (class "Default")
      (node (ref "Q18") (pin "1") (pinfunction "B_1") (pintype "passive"))
      (node (ref "R182") (pin "1") (pinfunction "1_1") (pintype "passive"))
      (node (ref "R52") (pin "1") (pinfunction "1_1") (pintype "passive"))
    )
    (net (code "54") (name "Net-(Q18-C)") (class "Default")
      (node (ref "Q18") (pin "3") (pinfunction "C_3") (pintype "passive"))
      (node (ref "VL8") (pin "6") (pinfunction "7_6") (pintype "passive"))
    )
    (net (code "55") (name "Net-(Q19-B)") (class "Default")
      (node (ref "Q19") (pin "1") (pinfunction "B_1") (pintype "passive"))
      (node (ref "R190") (pin "1") (pinfunction "1_1") (pintype "passive"))
      (node (ref "R53") (pin "1") (pinfunction "1_1") (pintype "passive"))
    )
    (net (code "56") (name "Net-(Q19-C)") (class "Default")
      (node (ref "Q19") (pin "3") (pinfunction "C_3") (pintype "passive"))
      (node (ref "VL8") (pin "3") (pinfunction "5_3") (pintype "passive"))
    )
    (net (code "57") (name "Net-(Q20-B)") (class "Default")
      (node (ref "Q20") (pin "1") (pinfunction "B_1") (pintype "passive"))
      (node (ref "R189") (pin "1") (pinfunction "1_1") (pintype "passive"))
      (node (ref "R54") (pin "1") (pinfunction "1_1") (pintype "passive"))
    )
    (net (code "58") (name "Net-(Q20-C)") (class "Default")
      (node (ref "Q20") (pin "3") (pinfunction "C_3") (pintype "passive"))
      (node (ref "VL8") (pin "2") (pinfunction "4_2") (pintype "passive"))
    )
    (net (code "59") (name "Net-(Q21-B)") (class "Default")
      (node (ref "Q21") (pin "1") (pinfunction "B_1") (pintype "passive"))
      (node (ref "R191") (pin "1") (pinfunction "1_1") (pintype "passive"))
      (node (ref "R55") (pin "1") (pinfunction "1_1") (pintype "passive"))
    )
    (net (code "60") (name "Net-(Q21-C)") (class "Default")
      (node (ref "Q21") (pin "3") (pinfunction "C_3") (pintype "passive"))
      (node (ref "VL9") (pin "5") (pinfunction "6_5") (pintype "passive"))
    )
    (net (code "61") (name "Net-(Q22-B)") (class "Default")
      (node (ref "Q22") (pin "1") (pinfunction "B_1") (pintype "passive"))
      (node (ref "R192") (pin "1") (pinfunction "1_1") (pintype "passive"))
      (node (ref "R56") (pin "1") (pinfunction "1_1") (pintype "passive"))
    )
    (net (code "62") (name "Net-(Q22-C)") (class "Default")
      (node (ref "Q22") (pin "3") (pinfunction "C_3") (pintype "passive"))
      (node (ref "VL9") (pin "6") (pinfunction "7_6") (pintype "passive"))
    )
    (net (code "63") (name "Net-(Q23-B)") (class "Default")
      (node (ref "Q23") (pin "1") (pinfunction "B_1") (pintype "passive"))
      (node (ref "R200") (pin "1") (pinfunction "1_1") (pintype "passive"))
      (node (ref "R57") (pin "1") (pinfunction "1_1") (pintype "passive"))
    )
    (net (code "64") (name "Net-(Q23-C)") (class "Default")
      (node (ref "Q23") (pin "3") (pinfunction "C_3") (pintype "passive"))
      (node (ref "VL9") (pin "3") (pinfunction "5_3") (pintype "passive"))
    )
    (net (code "65") (name "Net-(Q24-B)") (class "Default")
      (node (ref "Q24") (pin "1") (pinfunction "B_1") (pintype "passive"))
      (node (ref "R199") (pin "1") (pinfunction "1_1") (pintype "passive"))
      (node (ref "R58") (pin "1") (pinfunction "1_1") (pintype "passive"))
    )
    (net (code "66") (name "Net-(Q24-C)") (class "Default")
      (node (ref "Q24") (pin "3") (pinfunction "C_3") (pintype "passive"))
      (node (ref "VL9") (pin "2") (pinfunction "4_2") (pintype "passive"))
    )
    (net (code "67") (name "Net-(Q25-B)") (class "Default")
      (node (ref "Q25") (pin "1") (pinfunction "B_1") (pintype "passive"))
      (node (ref "R138") (pin "1") (pinfunction "1_1") (pintype "passive"))
      (node (ref "R32") (pin "2") (pinfunction "2_2") (pintype "passive"))
    )
    (net (code "68") (name "Net-(Q25-C)") (class "Default")
      (node (ref "Q25") (pin "3") (pinfunction "C_3") (pintype "passive"))
      (node (ref "VL1") (pin "10") (pinfunction "Om_10") (pintype "passive"))
    )
    (net (code "69") (name "Net-(Q26-B)") (class "Default")
      (node (ref "Q26") (pin "1") (pinfunction "B_1") (pintype "passive"))
      (node (ref "R139") (pin "2") (pinfunction "2_2") (pintype "passive"))
      (node (ref "R33") (pin "1") (pinfunction "1_1") (pintype "passive"))
    )
    (net (code "70") (name "Net-(Q26-C)") (class "Default")
      (node (ref "Q26") (pin "3") (pinfunction "C_3") (pintype "passive"))
      (node (ref "VL1") (pin "8") (pinfunction "S_8") (pintype "passive"))
    )
    (net (code "71") (name "Net-(Q27-B)") (class "Default")
      (node (ref "Q27") (pin "1") (pinfunction "B_1") (pintype "passive"))
      (node (ref "R143") (pin "1") (pinfunction "1_1") (pintype "passive"))
      (node (ref "R59") (pin "1") (pinfunction "1_1") (pintype "passive"))
    )
    (net (code "72") (name "Net-(Q27-C)") (class "Default")
      (node (ref "Q27") (pin "3") (pinfunction "C_3") (pintype "passive"))
      (node (ref "VL2") (pin "7") (pinfunction "3_7") (pintype "passive"))
    )
    (net (code "73") (name "Net-(Q28-B)") (class "Default")
      (node (ref "Q28") (pin "1") (pinfunction "B_1") (pintype "passive"))
      (node (ref "R148") (pin "1") (pinfunction "1_1") (pintype "passive"))
      (node (ref "R61") (pin "1") (pinfunction "1_1") (pintype "passive"))
    )
    (net (code "74") (name "Net-(Q28-C)") (class "Default")
      (node (ref "Q28") (pin "3") (pinfunction "C_3") (pintype "passive"))
      (node (ref "VL2") (pin "14") (pinfunction "9_14") (pintype "passive"))
    )
    (net (code "75") (name "Net-(Q29-B)") (class "Default")
      (node (ref "Q29") (pin "1") (pinfunction "B_1") (pintype "passive"))
      (node (ref "R153") (pin "1") (pinfunction "1_1") (pintype "passive"))
      (node (ref "R63") (pin "1") (pinfunction "1_1") (pintype "passive"))
    )
    (net (code "76") (name "Net-(Q29-C)") (class "Default")
      (node (ref "Q29") (pin "3") (pinfunction "C_3") (pintype "passive"))
      (node (ref "VL3") (pin "7") (pinfunction "3_7") (pintype "passive"))
    )
    (net (code "77") (name "Net-(Q30-B)") (class "Default")
      (node (ref "Q30") (pin "1") (pinfunction "B_1") (pintype "passive"))
      (node (ref "R158") (pin "1") (pinfunction "1_1") (pintype "passive"))
      (node (ref "R65") (pin "1") (pinfunction "1_1") (pintype "passive"))
    )
    (net (code "78") (name "Net-(Q30-C)") (class "Default")
      (node (ref "Q30") (pin "3") (pinfunction "C_3") (pintype "passive"))
      (node (ref "VL3") (pin "14") (pinfunction "9_14") (pintype "passive"))
    )
    (net (code "79") (name "Net-(Q31-B)") (class "Default")
      (node (ref "Q31") (pin "1") (pinfunction "B_1") (pintype "passive"))
      (node (ref "R163") (pin "1") (pinfunction "1_1") (pintype "passive"))
      (node (ref "R68") (pin "1") (pinfunction "1_1") (pintype "passive"))
    )
    (net (code "80") (name "Net-(Q31-C)") (class "Default")
      (node (ref "Q31") (pin "3") (pinfunction "C_3") (pintype "passive"))
      (node (ref "VL5") (pin "7") (pinfunction "3_7") (pintype "passive"))
    )
    (net (code "81") (name "Net-(Q32-B)") (class "Default")
      (node (ref "Q32") (pin "1") (pinfunction "B_1") (pintype "passive"))
      (node (ref "R168") (pin "1") (pinfunction "1_1") (pintype "passive"))
      (node (ref "R70") (pin "1") (pinfunction "1_1") (pintype "passive"))
    )
    (net (code "82") (name "Net-(Q32-C)") (class "Default")
      (node (ref "Q32") (pin "3") (pinfunction "C_3") (pintype "passive"))
      (node (ref "VL5") (pin "14") (pinfunction "9_14") (pintype "passive"))
    )
    (net (code "83") (name "Net-(Q33-B)") (class "Default")
      (node (ref "Q33") (pin "1") (pinfunction "B_1") (pintype "passive"))
      (node (ref "R173") (pin "1") (pinfunction "1_1") (pintype "passive"))
      (node (ref "R72") (pin "1") (pinfunction "1_1") (pintype "passive"))
    )
    (net (code "84") (name "Net-(Q33-C)") (class "Default")
      (node (ref "Q33") (pin "3") (pinfunction "C_3") (pintype "passive"))
      (node (ref "VL6") (pin "7") (pinfunction "3_7") (pintype "passive"))
    )
    (net (code "85") (name "Net-(Q34-B)") (class "Default")
      (node (ref "Q34") (pin "1") (pinfunction "B_1") (pintype "passive"))
      (node (ref "R178") (pin "1") (pinfunction "1_1") (pintype "passive"))
      (node (ref "R74") (pin "1") (pinfunction "1_1") (pintype "passive"))
    )
    (net (code "86") (name "Net-(Q34-C)") (class "Default")
      (node (ref "Q34") (pin "3") (pinfunction "C_3") (pintype "passive"))
      (node (ref "VL6") (pin "14") (pinfunction "9_14") (pintype "passive"))
    )
    (net (code "87") (name "Net-(Q35-B)") (class "Default")
      (node (ref "Q35") (pin "1") (pinfunction "B_1") (pintype "passive"))
      (node (ref "R183") (pin "1") (pinfunction "1_1") (pintype "passive"))
      (node (ref "R77") (pin "1") (pinfunction "1_1") (pintype "passive"))
    )
    (net (code "88") (name "Net-(Q35-C)") (class "Default")
      (node (ref "Q35") (pin "3") (pinfunction "C_3") (pintype "passive"))
      (node (ref "VL8") (pin "7") (pinfunction "3_7") (pintype "passive"))
    )
    (net (code "89") (name "Net-(Q36-B)") (class "Default")
      (node (ref "Q36") (pin "1") (pinfunction "B_1") (pintype "passive"))
      (node (ref "R188") (pin "1") (pinfunction "1_1") (pintype "passive"))
      (node (ref "R79") (pin "1") (pinfunction "1_1") (pintype "passive"))
    )
    (net (code "90") (name "Net-(Q36-C)") (class "Default")
      (node (ref "Q36") (pin "3") (pinfunction "C_3") (pintype "passive"))
      (node (ref "VL8") (pin "14") (pinfunction "9_14") (pintype "passive"))
    )
    (net (code "91") (name "Net-(Q37-B)") (class "Default")
      (node (ref "Q37") (pin "1") (pinfunction "B_1") (pintype "passive"))
      (node (ref "R193") (pin "1") (pinfunction "1_1") (pintype "passive"))
      (node (ref "R81") (pin "1") (pinfunction "1_1") (pintype "passive"))
    )
    (net (code "92") (name "Net-(Q37-C)") (class "Default")
      (node (ref "Q37") (pin "3") (pinfunction "C_3") (pintype "passive"))
      (node (ref "VL9") (pin "7") (pinfunction "3_7") (pintype "passive"))
    )
    (net (code "93") (name "Net-(Q38-B)") (class "Default")
      (node (ref "Q38") (pin "1") (pinfunction "B_1") (pintype "passive"))
      (node (ref "R198") (pin "1") (pinfunction "1_1") (pintype "passive"))
      (node (ref "R83") (pin "1") (pinfunction "1_1") (pintype "passive"))
    )
    (net (code "94") (name "Net-(Q38-C)") (class "Default")
      (node (ref "Q38") (pin "3") (pinfunction "C_3") (pintype "passive"))
      (node (ref "VL9") (pin "14") (pinfunction "9_14") (pintype "passive"))
    )
    (net (code "95") (name "Net-(Q39-B)") (class "Default")
      (node (ref "Q39") (pin "1") (pinfunction "B_1") (pintype "passive"))
      (node (ref "R144") (pin "1") (pinfunction "1_1") (pintype "passive"))
      (node (ref "R60") (pin "1") (pinfunction "1_1") (pintype "passive"))
    )
    (net (code "96") (name "Net-(Q39-C)") (class "Default")
      (node (ref "Q39") (pin "3") (pinfunction "C_3") (pintype "passive"))
      (node (ref "VL2") (pin "9") (pinfunction "8_9") (pintype "passive"))
    )
    (net (code "97") (name "Net-(Q40-B)") (class "Default")
      (node (ref "Q40") (pin "1") (pinfunction "B_1") (pintype "passive"))
      (node (ref "R145") (pin "1") (pinfunction "1_1") (pintype "passive"))
      (node (ref "R85") (pin "1") (pinfunction "1_1") (pintype "passive"))
    )
    (net (code "98") (name "Net-(Q40-C)") (class "Default")
      (node (ref "Q40") (pin "3") (pinfunction "C_3") (pintype "passive"))
      (node (ref "VL2") (pin "10") (pinfunction "2_10") (pintype "passive"))
    )
    (net (code "99") (name "Net-(Q41-B)") (class "Default")
      (node (ref "Q41") (pin "1") (pinfunction "B_1") (pintype "passive"))
      (node (ref "R147") (pin "1") (pinfunction "1_1") (pintype "passive"))
      (node (ref "R62") (pin "1") (pinfunction "1_1") (pintype "passive"))
    )
    (net (code "100") (name "Net-(Q41-C)") (class "Default")
      (node (ref "Q41") (pin "3") (pinfunction "C_3") (pintype "passive"))
      (node (ref "VL2") (pin "13") (pinfunction "0_13") (pintype "passive"))
    )
    (net (code "101") (name "Net-(Q42-B)") (class "Default")
      (node (ref "Q42") (pin "1") (pinfunction "B_1") (pintype "passive"))
      (node (ref "R146") (pin "1") (pinfunction "1_1") (pintype "passive"))
      (node (ref "R86") (pin "1") (pinfunction "1_1") (pintype "passive"))
    )
    (net (code "102") (name "Net-(Q42-C)") (class "Default")
      (node (ref "Q42") (pin "3") (pinfunction "C_3") (pintype "passive"))
      (node (ref "VL2") (pin "11") (pinfunction "1_11") (pintype "passive"))
    )
    (net (code "103") (name "Net-(Q43-B)") (class "Default")
      (node (ref "Q43") (pin "1") (pinfunction "B_1") (pintype "passive"))
      (node (ref "R154") (pin "1") (pinfunction "1_1") (pintype "passive"))
      (node (ref "R64") (pin "1") (pinfunction "1_1") (pintype "passive"))
    )
    (net (code "104") (name "Net-(Q43-C)") (class "Default")
      (node (ref "Q43") (pin "3") (pinfunction "C_3") (pintype "passive"))
      (node (ref "VL3") (pin "9") (pinfunction "8_9") (pintype "passive"))
    )
    (net (code "105") (name "Net-(Q44-B)") (class "Default")
      (node (ref "Q44") (pin "1") (pinfunction "B_1") (pintype "passive"))
      (node (ref "R155") (pin "1") (pinfunction "1_1") (pintype "passive"))
      (node (ref "R87") (pin "1") (pinfunction "1_1") (pintype "passive"))
    )
    (net (code "106") (name "Net-(Q44-C)") (class "Default")
      (node (ref "Q44") (pin "3") (pinfunction "C_3") (pintype "passive"))
      (node (ref "VL3") (pin "10") (pinfunction "2_10") (pintype "passive"))
    )
    (net (code "107") (name "Net-(Q45-B)") (class "Default")
      (node (ref "Q45") (pin "1") (pinfunction "B_1") (pintype "passive"))
      (node (ref "R157") (pin "1") (pinfunction "1_1") (pintype "passive"))
      (node (ref "R66") (pin "1") (pinfunction "1_1") (pintype "passive"))
    )
    (net (code "108") (name "Net-(Q45-C)") (class "Default")
      (node (ref "Q45") (pin "3") (pinfunction "C_3") (pintype "passive"))
      (node (ref "VL3") (pin "13") (pinfunction "0_13") (pintype "passive"))
    )
    (net (code "109") (name "Net-(Q46-B)") (class "Default")
      (node (ref "Q46") (pin "1") (pinfunction "B_1") (pintype "passive"))
      (node (ref "R156") (pin "1") (pinfunction "1_1") (pintype "passive"))
      (node (ref "R88") (pin "1") (pinfunction "1_1") (pintype "passive"))
    )
    (net (code "110") (name "Net-(Q46-C)") (class "Default")
      (node (ref "Q46") (pin "3") (pinfunction "C_3") (pintype "passive"))
      (node (ref "VL3") (pin "11") (pinfunction "1_11") (pintype "passive"))
    )
    (net (code "111") (name "Net-(Q47-B)") (class "Default")
      (node (ref "Q47") (pin "1") (pinfunction "B_1") (pintype "passive"))
      (node (ref "R99") (pin "2") (pinfunction "2_2") (pintype "passive"))
    )
    (net (code "112") (name "Net-(Q47-C)") (class "Default")
      (node (ref "Q47") (pin "3") (pinfunction "C_3") (pintype "passive"))
      (node (ref "R89") (pin "1") (pinfunction "1_1") (pintype "passive"))
    )
    (net (code "113") (name "Net-(Q48-B)") (class "Default")
      (node (ref "Q48") (pin "1") (pinfunction "B_1") (pintype "passive"))
      (node (ref "R164") (pin "1") (pinfunction "1_1") (pintype "passive"))
      (node (ref "R69") (pin "1") (pinfunction "1_1") (pintype "passive"))
    )
    (net (code "114") (name "Net-(Q48-C)") (class "Default")
      (node (ref "Q48") (pin "3") (pinfunction "C_3") (pintype "passive"))
      (node (ref "VL5") (pin "9") (pinfunction "8_9") (pintype "passive"))
    )
    (net (code "115") (name "Net-(Q49-B)") (class "Default")
      (node (ref "Q49") (pin "1") (pinfunction "B_1") (pintype "passive"))
      (node (ref "R165") (pin "1") (pinfunction "1_1") (pintype "passive"))
      (node (ref "R90") (pin "1") (pinfunction "1_1") (pintype "passive"))
    )
    (net (code "116") (name "Net-(Q49-C)") (class "Default")
      (node (ref "Q49") (pin "3") (pinfunction "C_3") (pintype "passive"))
      (node (ref "VL5") (pin "10") (pinfunction "2_10") (pintype "passive"))
    )
    (net (code "117") (name "Net-(Q50-B)") (class "Default")
      (node (ref "Q50") (pin "1") (pinfunction "B_1") (pintype "passive"))
      (node (ref "R167") (pin "1") (pinfunction "1_1") (pintype "passive"))
      (node (ref "R71") (pin "1") (pinfunction "1_1") (pintype "passive"))
    )
    (net (code "118") (name "Net-(Q50-C)") (class "Default")
      (node (ref "Q50") (pin "3") (pinfunction "C_3") (pintype "passive"))
      (node (ref "VL5") (pin "13") (pinfunction "0_13") (pintype "passive"))
    )
    (net (code "119") (name "Net-(Q51-B)") (class "Default")
      (node (ref "Q51") (pin "1") (pinfunction "B_1") (pintype "passive"))
      (node (ref "R166") (pin "1") (pinfunction "1_1") (pintype "passive"))
      (node (ref "R91") (pin "1") (pinfunction "1_1") (pintype "passive"))
    )
    (net (code "120") (name "Net-(Q51-C)") (class "Default")
      (node (ref "Q51") (pin "3") (pinfunction "C_3") (pintype "passive"))
      (node (ref "VL5") (pin "11") (pinfunction "1_11") (pintype "passive"))
    )
    (net (code "121") (name "Net-(Q52-B)") (class "Default")
      (node (ref "Q52") (pin "1") (pinfunction "B_1") (pintype "passive"))
      (node (ref "R174") (pin "1") (pinfunction "1_1") (pintype "passive"))
      (node (ref "R73") (pin "1") (pinfunction "1_1") (pintype "passive"))
    )
    (net (code "122") (name "Net-(Q52-C)") (class "Default")
      (node (ref "Q52") (pin "3") (pinfunction "C_3") (pintype "passive"))
      (node (ref "VL6") (pin "9") (pinfunction "8_9") (pintype "passive"))
    )
    (net (code "123") (name "Net-(Q53-B)") (class "Default")
      (node (ref "Q53") (pin "1") (pinfunction "B_1") (pintype "passive"))
      (node (ref "R175") (pin "1") (pinfunction "1_1") (pintype "passive"))
      (node (ref "R92") (pin "1") (pinfunction "1_1") (pintype "passive"))
    )
    (net (code "124") (name "Net-(Q53-C)") (class "Default")
      (node (ref "Q53") (pin "3") (pinfunction "C_3") (pintype "passive"))
      (node (ref "VL6") (pin "10") (pinfunction "2_10") (pintype "passive"))
    )
    (net (code "125") (name "Net-(Q54-B)") (class "Default")
      (node (ref "Q54") (pin "1") (pinfunction "B_1") (pintype "passive"))
      (node (ref "R177") (pin "1") (pinfunction "1_1") (pintype "passive"))
      (node (ref "R75") (pin "1") (pinfunction "1_1") (pintype "passive"))
    )
    (net (code "126") (name "Net-(Q54-C)") (class "Default")
      (node (ref "Q54") (pin "3") (pinfunction "C_3") (pintype "passive"))
      (node (ref "VL6") (pin "13") (pinfunction "0_13") (pintype "passive"))
    )
    (net (code "127") (name "Net-(Q55-B)") (class "Default")
      (node (ref "Q55") (pin "1") (pinfunction "B_1") (pintype "passive"))
      (node (ref "R176") (pin "1") (pinfunction "1_1") (pintype "passive"))
      (node (ref "R93") (pin "1") (pinfunction "1_1") (pintype "passive"))
    )
    (net (code "128") (name "Net-(Q55-C)") (class "Default")
      (node (ref "Q55") (pin "3") (pinfunction "C_3") (pintype "passive"))
      (node (ref "VL6") (pin "11") (pinfunction "1_11") (pintype "passive"))
    )
    (net (code "129") (name "Net-(Q56-B)") (class "Default")
      (node (ref "Q56") (pin "1") (pinfunction "B_1") (pintype "passive"))
      (node (ref "R100") (pin "2") (pinfunction "2_2") (pintype "passive"))
    )
    (net (code "130") (name "Net-(Q56-C)") (class "Default")
      (node (ref "Q56") (pin "3") (pinfunction "C_3") (pintype "passive"))
      (node (ref "R94") (pin "1") (pinfunction "1_1") (pintype "passive"))
    )
    (net (code "131") (name "Net-(Q57-B)") (class "Default")
      (node (ref "Q57") (pin "1") (pinfunction "B_1") (pintype "passive"))
      (node (ref "R184") (pin "1") (pinfunction "1_1") (pintype "passive"))
      (node (ref "R78") (pin "1") (pinfunction "1_1") (pintype "passive"))
    )
    (net (code "132") (name "Net-(Q57-C)") (class "Default")
      (node (ref "Q57") (pin "3") (pinfunction "C_3") (pintype "passive"))
      (node (ref "VL8") (pin "9") (pinfunction "8_9") (pintype "passive"))
    )
    (net (code "133") (name "Net-(Q58-B)") (class "Default")
      (node (ref "Q58") (pin "1") (pinfunction "B_1") (pintype "passive"))
      (node (ref "R185") (pin "1") (pinfunction "1_1") (pintype "passive"))
      (node (ref "R95") (pin "1") (pinfunction "1_1") (pintype "passive"))
    )
    (net (code "134") (name "Net-(Q58-C)") (class "Default")
      (node (ref "Q58") (pin "3") (pinfunction "C_3") (pintype "passive"))
      (node (ref "VL8") (pin "10") (pinfunction "2_10") (pintype "passive"))
    )
    (net (code "135") (name "Net-(Q59-B)") (class "Default")
      (node (ref "Q59") (pin "1") (pinfunction "B_1") (pintype "passive"))
      (node (ref "R187") (pin "1") (pinfunction "1_1") (pintype "passive"))
      (node (ref "R80") (pin "1") (pinfunction "1_1") (pintype "passive"))
    )
    (net (code "136") (name "Net-(Q59-C)") (class "Default")
      (node (ref "Q59") (pin "3") (pinfunction "C_3") (pintype "passive"))
      (node (ref "VL8") (pin "13") (pinfunction "0_13") (pintype "passive"))
    )
    (net (code "137") (name "Net-(Q60-B)") (class "Default")
      (node (ref "Q60") (pin "1") (pinfunction "B_1") (pintype "passive"))
      (node (ref "R186") (pin "1") (pinfunction "1_1") (pintype "passive"))
      (node (ref "R96") (pin "1") (pinfunction "1_1") (pintype "passive"))
    )
    (net (code "138") (name "Net-(Q60-C)") (class "Default")
      (node (ref "Q60") (pin "3") (pinfunction "C_3") (pintype "passive"))
      (node (ref "VL8") (pin "11") (pinfunction "1_11") (pintype "passive"))
    )
    (net (code "139") (name "Net-(Q61-B)") (class "Default")
      (node (ref "Q61") (pin "1") (pinfunction "B_1") (pintype "passive"))
      (node (ref "R194") (pin "1") (pinfunction "1_1") (pintype "passive"))
      (node (ref "R82") (pin "1") (pinfunction "1_1") (pintype "passive"))
    )
    (net (code "140") (name "Net-(Q61-C)") (class "Default")
      (node (ref "Q61") (pin "3") (pinfunction "C_3") (pintype "passive"))
      (node (ref "VL9") (pin "9") (pinfunction "8_9") (pintype "passive"))
    )
    (net (code "141") (name "Net-(Q62-B)") (class "Default")
      (node (ref "Q62") (pin "1") (pinfunction "B_1") (pintype "passive"))
      (node (ref "R195") (pin "1") (pinfunction "1_1") (pintype "passive"))
      (node (ref "R97") (pin "1") (pinfunction "1_1") (pintype "passive"))
    )
    (net (code "142") (name "Net-(Q62-C)") (class "Default")
      (node (ref "Q62") (pin "3") (pinfunction "C_3") (pintype "passive"))
      (node (ref "VL9") (pin "10") (pinfunction "2_10") (pintype "passive"))
    )
    (net (code "143") (name "Net-(Q63-B)") (class "Default")
      (node (ref "Q63") (pin "1") (pinfunction "B_1") (pintype "passive"))
      (node (ref "R197") (pin "1") (pinfunction "1_1") (pintype "passive"))
      (node (ref "R84") (pin "1") (pinfunction "1_1") (pintype "passive"))
    )
    (net (code "144") (name "Net-(Q63-C)") (class "Default")
      (node (ref "Q63") (pin "3") (pinfunction "C_3") (pintype "passive"))
      (node (ref "VL9") (pin "13") (pinfunction "0_13") (pintype "passive"))
    )
    (net (code "145") (name "Net-(Q64-B)") (class "Default")
      (node (ref "Q64") (pin "1") (pinfunction "B_1") (pintype "passive"))
      (node (ref "R196") (pin "1") (pinfunction "1_1") (pintype "passive"))
      (node (ref "R98") (pin "1") (pinfunction "1_1") (pintype "passive"))
    )
    (net (code "146") (name "Net-(Q64-C)") (class "Default")
      (node (ref "Q64") (pin "3") (pinfunction "C_3") (pintype "passive"))
      (node (ref "VL9") (pin "11") (pinfunction "1_11") (pintype "passive"))
    )
    (net (code "147") (name "Net-(Q65-G)") (class "Default")
      (node (ref "Q65") (pin "1") (pinfunction "G_1") (pintype "passive"))
      (node (ref "R103") (pin "1") (pinfunction "1_1") (pintype "passive"))
    )
    (net (code "148") (name "Net-(Q66-G)") (class "Default")
      (node (ref "Q66") (pin "1") (pinfunction "G_1") (pintype "passive"))
      (node (ref "R102") (pin "2") (pinfunction "2_2") (pintype "passive"))
    )
    (net (code "149") (name "Net-(Q67-D)") (class "Default")
      (node (ref "Q67") (pin "2") (pinfunction "D_2") (pintype "passive"))
      (node (ref "Q70") (pin "3") (pinfunction "S_3") (pintype "passive"))
    )
    (net (code "150") (name "Net-(Q67-G)") (class "Default")
      (node (ref "Q67") (pin "1") (pinfunction "G_1") (pintype "passive"))
      (node (ref "R117") (pin "1") (pinfunction "1_1") (pintype "passive"))
      (node (ref "U17") (pin "3") (pinfunction "_INT__3") (pintype "passive"))
    )
    (net (code "151") (name "Net-(Q68-G)") (class "Default")
      (node (ref "Q68") (pin "1") (pinfunction "G_1") (pintype "passive"))
      (node (ref "R122") (pin "1") (pinfunction "1_1") (pintype "passive"))
    )
    (net (code "152") (name "Net-(Q68-S)") (class "Default")
      (node (ref "Q68") (pin "3") (pinfunction "S_3") (pintype "passive"))
      (node (ref "Q70") (pin "2") (pinfunction "D_2") (pintype "passive"))
    )
    (net (code "153") (name "Net-(Q69-D)") (class "Default")
      (node (ref "Q69") (pin "2") (pinfunction "D_2") (pintype "passive"))
      (node (ref "R126") (pin "1") (pinfunction "1_1") (pintype "passive"))
      (node (ref "U18") (pin "41") (pinfunction "PB5_41") (pintype "bidirectional"))
    )
    (net (code "154") (name "Net-(Q69-G)") (class "Default")
      (node (ref "Q69") (pin "1") (pinfunction "G_1") (pintype "passive"))
      (node (ref "Q70") (pin "1") (pinfunction "G_1") (pintype "passive"))
      (node (ref "R121") (pin "1") (pinfunction "1_1") (pintype "passive"))
    )
    (net (code "155") (name "Net-(R1-Pad1)") (class "Default")
      (node (ref "R1") (pin "1") (pinfunction "1_1") (pintype "passive"))
      (node (ref "R8") (pin "2") (pinfunction "2_2") (pintype "passive"))
    )
    (net (code "156") (name "Net-(R4-Pad1)") (class "Default")
      (node (ref "R4") (pin "1") (pinfunction "1_1") (pintype "passive"))
      (node (ref "VL2") (pin "12") (pinfunction "A_12") (pintype "passive"))
      (node (ref "VL2") (pin "4") (pinfunction "A_4") (pintype "passive"))
    )
    (net (code "157") (name "Net-(R4-Pad2)") (class "Default")
      (node (ref "R4") (pin "2") (pinfunction "2_2") (pintype "passive"))
      (node (ref "R5") (pin "2") (pinfunction "2_2") (pintype "passive"))
    )
    (net (code "158") (name "Net-(R6-Pad1)") (class "Default")
      (node (ref "R6") (pin "1") (pinfunction "1_1") (pintype "passive"))
      (node (ref "VL3") (pin "12") (pinfunction "A_12") (pintype "passive"))
      (node (ref "VL3") (pin "4") (pinfunction "A_4") (pintype "passive"))
    )
    (net (code "159") (name "Net-(R6-Pad2)") (class "Default")
      (node (ref "R6") (pin "2") (pinfunction "2_2") (pintype "passive"))
      (node (ref "R7") (pin "2") (pinfunction "2_2") (pintype "passive"))
    )
    (net (code "160") (name "Net-(R8-Pad1)") (class "Default")
      (node (ref "R8") (pin "1") (pinfunction "1_1") (pintype "passive"))
      (node (ref "VL4") (pin "1") (pinfunction "1_1") (pintype "passive"))
      (node (ref "VL4") (pin "3") (pinfunction "3_3") (pintype "passive"))
      (node (ref "VL4") (pin "5") (pinfunction "5_5") (pintype "passive"))
      (node (ref "VL4") (pin "7") (pinfunction "7_7") (pintype "passive"))
    )
    (net (code "161") (name "Net-(R9-Pad1)") (class "Default")
      (node (ref "R9") (pin "1") (pinfunction "1_1") (pintype "passive"))
      (node (ref "VL5") (pin "12") (pinfunction "A_12") (pintype "passive"))
      (node (ref "VL5") (pin "4") (pinfunction "A_4") (pintype "passive"))
    )
    (net (code "162") (name "Net-(R10-Pad1)") (class "Default")
      (node (ref "R10") (pin "1") (pinfunction "1_1") (pintype "passive"))
      (node (ref "R24") (pin "1") (pinfunction "1_1") (pintype "passive"))
    )
    (net (code "163") (name "Net-(R10-Pad2)") (class "Default")
      (node (ref "R10") (pin "2") (pinfunction "2_2") (pintype "passive"))
      (node (ref "R9") (pin "2") (pinfunction "2_2") (pintype "passive"))
    )
    (net (code "164") (name "Net-(R11-Pad1)") (class "Default")
      (node (ref "R11") (pin "1") (pinfunction "1_1") (pintype "passive"))
      (node (ref "VL6") (pin "12") (pinfunction "A_12") (pintype "passive"))
      (node (ref "VL6") (pin "4") (pinfunction "A_4") (pintype "passive"))
    )
    (net (code "165") (name "Net-(R11-Pad2)") (class "Default")
      (node (ref "R11") (pin "2") (pinfunction "2_2") (pintype "passive"))
      (node (ref "R12") (pin "2") (pinfunction "2_2") (pintype "passive"))
    )
    (net (code "166") (name "Net-(R12-Pad1)") (class "Default")
      (node (ref "R12") (pin "1") (pinfunction "1_1") (pintype "passive"))
      (node (ref "R26") (pin "1") (pinfunction "1_1") (pintype "passive"))
    )
    (net (code "167") (name "Net-(R13-Pad1)") (class "Default")
      (node (ref "R13") (pin "1") (pinfunction "1_1") (pintype "passive"))
      (node (ref "VL7") (pin "1") (pinfunction "1_1") (pintype "passive"))
      (node (ref "VL7") (pin "3") (pinfunction "3_3") (pintype "passive"))
      (node (ref "VL7") (pin "5") (pinfunction "5_5") (pintype "passive"))
      (node (ref "VL7") (pin "7") (pinfunction "7_7") (pintype "passive"))
    )
    (net (code "168") (name "Net-(R13-Pad2)") (class "Default")
      (node (ref "R13") (pin "2") (pinfunction "2_2") (pintype "passive"))
      (node (ref "R2") (pin "1") (pinfunction "1_1") (pintype "passive"))
    )
    (net (code "169") (name "Net-(R14-Pad1)") (class "Default")
      (node (ref "R14") (pin "1") (pinfunction "1_1") (pintype "passive"))
      (node (ref "VL8") (pin "12") (pinfunction "A_12") (pintype "passive"))
      (node (ref "VL8") (pin "4") (pinfunction "A_4") (pintype "passive"))
    )
    (net (code "170") (name "Net-(R14-Pad2)") (class "Default")
      (node (ref "R14") (pin "2") (pinfunction "2_2") (pintype "passive"))
      (node (ref "R15") (pin "2") (pinfunction "2_2") (pintype "passive"))
    )
    (net (code "171") (name "Net-(R15-Pad1)") (class "Default")
      (node (ref "R15") (pin "1") (pinfunction "1_1") (pintype "passive"))
      (node (ref "R28") (pin "1") (pinfunction "1_1") (pintype "passive"))
    )
    (net (code "172") (name "Net-(R16-Pad1)") (class "Default")
      (node (ref "R16") (pin "1") (pinfunction "1_1") (pintype "passive"))
      (node (ref "VL9") (pin "12") (pinfunction "A_12") (pintype "passive"))
      (node (ref "VL9") (pin "4") (pinfunction "A_4") (pintype "passive"))
    )
    (net (code "173") (name "Net-(R16-Pad2)") (class "Default")
      (node (ref "R16") (pin "2") (pinfunction "2_2") (pintype "passive"))
      (node (ref "R17") (pin "2") (pinfunction "2_2") (pintype "passive"))
    )
    (net (code "174") (name "Net-(R17-Pad1)") (class "Default")
      (node (ref "R17") (pin "1") (pinfunction "1_1") (pintype "passive"))
      (node (ref "R30") (pin "1") (pinfunction "1_1") (pintype "passive"))
    )
    (net (code "175") (name "Net-(R18-Pad1)") (class "Default")
      (node (ref "R18") (pin "1") (pinfunction "1_1") (pintype "passive"))
      (node (ref "R3") (pin "1") (pinfunction "1_1") (pintype "passive"))
    )
    (net (code "176") (name "Net-(R18-Pad2)") (class "Default")
      (node (ref "R18") (pin "2") (pinfunction "2_2") (pintype "passive"))
      (node (ref "R19") (pin "2") (pinfunction "2_2") (pintype "passive"))
    )
    (net (code "177") (name "Net-(R19-Pad1)") (class "Default")
      (node (ref "R19") (pin "1") (pinfunction "1_1") (pintype "passive"))
      (node (ref "R34") (pin "1") (pinfunction "1_1") (pintype "passive"))
    )
    (net (code "178") (name "Net-(R20-Pad1)") (class "Default")
      (node (ref "R20") (pin "1") (pinfunction "1_1") (pintype "passive"))
      (node (ref "R5") (pin "1") (pinfunction "1_1") (pintype "passive"))
    )
    (net (code "179") (name "Net-(R20-Pad2)") (class "Default")
      (node (ref "R20") (pin "2") (pinfunction "2_2") (pintype "passive"))
      (node (ref "R21") (pin "2") (pinfunction "2_2") (pintype "passive"))
    )
    (net (code "180") (name "Net-(R22-Pad1)") (class "Default")
      (node (ref "R22") (pin "1") (pinfunction "1_1") (pintype "passive"))
      (node (ref "R7") (pin "1") (pinfunction "1_1") (pintype "passive"))
    )
    (net (code "181") (name "Net-(R22-Pad2)") (class "Default")
      (node (ref "R22") (pin "2") (pinfunction "2_2") (pintype "passive"))
      (node (ref "R23") (pin "2") (pinfunction "2_2") (pintype "passive"))
    )
    (net (code "182") (name "Net-(R24-Pad2)") (class "Default")
      (node (ref "R24") (pin "2") (pinfunction "2_2") (pintype "passive"))
      (node (ref "R25") (pin "2") (pinfunction "2_2") (pintype "passive"))
    )
    (net (code "183") (name "Net-(R26-Pad2)") (class "Default")
      (node (ref "R26") (pin "2") (pinfunction "2_2") (pintype "passive"))
      (node (ref "R27") (pin "2") (pinfunction "2_2") (pintype "passive"))
    )
    (net (code "184") (name "Net-(R28-Pad2)") (class "Default")
      (node (ref "R28") (pin "2") (pinfunction "2_2") (pintype "passive"))
      (node (ref "R29") (pin "2") (pinfunction "2_2") (pintype "passive"))
    )
    (net (code "185") (name "Net-(R30-Pad2)") (class "Default")
      (node (ref "R30") (pin "2") (pinfunction "2_2") (pintype "passive"))
      (node (ref "R31") (pin "2") (pinfunction "2_2") (pintype "passive"))
    )
    (net (code "186") (name "Net-(R67-Pad1)") (class "Default")
      (node (ref "R67") (pin "1") (pinfunction "1_1") (pintype "passive"))
      (node (ref "R89") (pin "2") (pinfunction "2_2") (pintype "passive"))
    )
    (net (code "187") (name "Net-(R67-Pad2)") (class "Default")
      (node (ref "R67") (pin "2") (pinfunction "2_2") (pintype "passive"))
      (node (ref "VL4") (pin "2") (pinfunction "2_2") (pintype "passive"))
      (node (ref "VL4") (pin "4") (pinfunction "4_4") (pintype "passive"))
      (node (ref "VL4") (pin "6") (pinfunction "6_6") (pintype "passive"))
      (node (ref "VL4") (pin "8") (pinfunction "8_8") (pintype "passive"))
    )
    (net (code "188") (name "Net-(R76-Pad1)") (class "Default")
      (node (ref "R76") (pin "1") (pinfunction "1_1") (pintype "passive"))
      (node (ref "R94") (pin "2") (pinfunction "2_2") (pintype "passive"))
    )
    (net (code "189") (name "Net-(R76-Pad2)") (class "Default")
      (node (ref "R76") (pin "2") (pinfunction "2_2") (pintype "passive"))
      (node (ref "VL7") (pin "2") (pinfunction "2_2") (pintype "passive"))
      (node (ref "VL7") (pin "4") (pinfunction "4_4") (pintype "passive"))
      (node (ref "VL7") (pin "6") (pinfunction "6_6") (pintype "passive"))
      (node (ref "VL7") (pin "8") (pinfunction "8_8") (pintype "passive"))
    )
    (net (code "190") (name "Net-(R104-Pad1)") (class "Default")
      (node (ref "R104") (pin "1") (pinfunction "1_1") (pintype "passive"))
      (node (ref "R105") (pin "2") (pinfunction "2_2") (pintype "passive"))
    )
    (net (code "191") (name "Net-(R105-Pad1)") (class "Default")
      (node (ref "R105") (pin "1") (pinfunction "1_1") (pintype "passive"))
      (node (ref "R106") (pin "2") (pinfunction "2_2") (pintype "passive"))
    )
    (net (code "192") (name "Net-(R106-Pad1)") (class "Default")
      (node (ref "R106") (pin "1") (pinfunction "1_1") (pintype "passive"))
      (node (ref "R107") (pin "2") (pinfunction "2_2") (pintype "passive"))
    )
    (net (code "193") (name "Net-(R107-Pad1)") (class "Default")
      (node (ref "R107") (pin "1") (pinfunction "1_1") (pintype "passive"))
      (node (ref "R108") (pin "2") (pinfunction "2_2") (pintype "passive"))
    )
    (net (code "194") (name "Net-(R108-Pad1)") (class "Default")
      (node (ref "R108") (pin "1") (pinfunction "1_1") (pintype "passive"))
      (node (ref "R109") (pin "2") (pinfunction "2_2") (pintype "passive"))
    )
    (net (code "195") (name "Net-(R109-Pad1)") (class "Default")
      (node (ref "R109") (pin "1") (pinfunction "1_1") (pintype "passive"))
      (node (ref "R110") (pin "2") (pinfunction "2_2") (pintype "passive"))
    )
    (net (code "196") (name "Net-(R110-Pad1)") (class "Default")
      (node (ref "R110") (pin "1") (pinfunction "1_1") (pintype "passive"))
      (node (ref "R111") (pin "2") (pinfunction "2_2") (pintype "passive"))
    )
    (net (code "197") (name "Net-(R119-Pad2)") (class "Default")
      (node (ref "R119") (pin "2") (pinfunction "2_2") (pintype "passive"))
      (node (ref "SB4") (pin "1") (pinfunction "1_1") (pintype "passive"))
    )
    (net (code "198") (name "Net-(R134-Pad2)") (class "Default")
      (node (ref "R134") (pin "2") (pinfunction "2_2") (pintype "passive"))
      (node (ref "SB1") (pin "1") (pinfunction "1_1") (pintype "passive"))
      (node (ref "SB2") (pin "1") (pinfunction "1_1") (pintype "passive"))
      (node (ref "SB3") (pin "1") (pinfunction "1_1") (pintype "passive"))
    )
    (net (code "199") (name "Net-(U1-LCHCLK)") (class "Default")
      (node (ref "U1") (pin "12") (pinfunction "LCHCLK_12") (pintype "input"))
      (node (ref "U10") (pin "12") (pinfunction "LCHCLK_12") (pintype "input"))
      (node (ref "U11") (pin "12") (pinfunction "LCHCLK_12") (pintype "input"))
      (node (ref "U12") (pin "12") (pinfunction "LCHCLK_12") (pintype "input"))
      (node (ref "U13") (pin "12") (pinfunction "LCHCLK_12") (pintype "input"))
      (node (ref "U18") (pin "26") (pinfunction "PB13_26") (pintype "bidirectional"))
      (node (ref "U2") (pin "12") (pinfunction "LCHCLK_12") (pintype "input"))
      (node (ref "U3") (pin "12") (pinfunction "LCHCLK_12") (pintype "input"))
      (node (ref "U4") (pin "12") (pinfunction "LCHCLK_12") (pintype "input"))
      (node (ref "U5") (pin "12") (pinfunction "LCHCLK_12") (pintype "input"))
      (node (ref "U6") (pin "12") (pinfunction "LCHCLK_12") (pintype "input"))
      (node (ref "U7") (pin "12") (pinfunction "LCHCLK_12") (pintype "input"))
      (node (ref "U8") (pin "12") (pinfunction "LCHCLK_12") (pintype "input"))
      (node (ref "U9") (pin "12") (pinfunction "LCHCLK_12") (pintype "input"))
    )
    (net (code "200") (name "Net-(U1-QB)") (class "Default")
      (node (ref "R98") (pin "2") (pinfunction "2_2") (pintype "passive"))
      (node (ref "U1") (pin "1") (pinfunction "QB_1") (pintype "tri_state"))
    )
    (net (code "201") (name "Net-(U1-QC)") (class "Default")
      (node (ref "R84") (pin "2") (pinfunction "2_2") (pintype "passive"))
      (node (ref "U1") (pin "2") (pinfunction "QC_2") (pintype "tri_state"))
    )
    (net (code "202") (name "Net-(U1-QE)") (class "Default")
      (node (ref "R83") (pin "2") (pinfunction "2_2") (pintype "passive"))
      (node (ref "U1") (pin "4") (pinfunction "QE_4") (pintype "tri_state"))
    )
    (net (code "203") (name "Net-(U1-QF)") (class "Default")
      (node (ref "R58") (pin "2") (pinfunction "2_2") (pintype "passive"))
      (node (ref "U1") (pin "5") (pinfunction "QF_5") (pintype "tri_state"))
    )
    (net (code "204") (name "Net-(U1-QH)") (class "Default")
      (node (ref "R57") (pin "2") (pinfunction "2_2") (pintype "passive"))
      (node (ref "U1") (pin "7") (pinfunction "QH_7") (pintype "tri_state"))
    )
    (net (code "205") (name "Net-(U1-SDI)") (class "Default")
      (node (ref "U1") (pin "14") (pinfunction "SDI_14") (pintype "input"))
      (node (ref "U2") (pin "9") (pinfunction "SDO_9") (pintype "output"))
    )
    (net (code "206") (name "Net-(U1-SFTCLK)") (class "Default")
      (node (ref "U1") (pin "11") (pinfunction "SFTCLK_11") (pintype "input"))
      (node (ref "U10") (pin "11") (pinfunction "SFTCLK_11") (pintype "input"))
      (node (ref "U11") (pin "11") (pinfunction "SFTCLK_11") (pintype "input"))
      (node (ref "U12") (pin "11") (pinfunction "SFTCLK_11") (pintype "input"))
      (node (ref "U13") (pin "11") (pinfunction "SFTCLK_11") (pintype "input"))
      (node (ref "U18") (pin "25") (pinfunction "PB12_25") (pintype "bidirectional"))
      (node (ref "U2") (pin "11") (pinfunction "SFTCLK_11") (pintype "input"))
      (node (ref "U3") (pin "11") (pinfunction "SFTCLK_11") (pintype "input"))
      (node (ref "U4") (pin "11") (pinfunction "SFTCLK_11") (pintype "input"))
      (node (ref "U5") (pin "11") (pinfunction "SFTCLK_11") (pintype "input"))
      (node (ref "U6") (pin "11") (pinfunction "SFTCLK_11") (pintype "input"))
      (node (ref "U7") (pin "11") (pinfunction "SFTCLK_11") (pintype "input"))
      (node (ref "U8") (pin "11") (pinfunction "SFTCLK_11") (pintype "input"))
      (node (ref "U9") (pin "11") (pinfunction "SFTCLK_11") (pintype "input"))
    )
    (net (code "207") (name "Net-(U1-VDD)") (class "Default")
      (node (ref "C10") (pin "2") (pinfunction "2_2") (pintype "passive"))
      (node (ref "C11") (pin "2") (pinfunction "2_2") (pintype "passive"))
      (node (ref "C12") (pin "2") (pinfunction "2_2") (pintype "passive"))
      (node (ref "C13") (pin "2") (pinfunction "2_2") (pintype "passive"))
      (node (ref "C14") (pin "2") (pinfunction "2_2") (pintype "passive"))
      (node (ref "C15") (pin "2") (pinfunction "2_2") (pintype "passive"))
      (node (ref "C25") (pin "1") (pinfunction "1_1") (pintype "passive"))
      (node (ref "C26") (pin "1") (pinfunction "1_1") (pintype "passive"))
      (node (ref "C3") (pin "2") (pinfunction "2_2") (pintype "passive"))
      (node (ref "C30") (pin "2") (pinfunction "2_2") (pintype "passive"))
      (node (ref "C34") (pin "2") (pinfunction "2_2") (pintype "passive"))
      (node (ref "C35") (pin "2") (pinfunction "2_2") (pintype "passive"))
      (node (ref "C4") (pin "2") (pinfunction "2_2") (pintype "passive"))
      (node (ref "C41") (pin "2") (pinfunction "2_2") (pintype "passive"))
      (node (ref "C46") (pin "2") (pinfunction "2_2") (pintype "passive"))
      (node (ref "C5") (pin "2") (pinfunction "2_2") (pintype "passive"))
      (node (ref "C6") (pin "2") (pinfunction "2_2") (pintype "passive"))
      (node (ref "C7") (pin "2") (pinfunction "2_2") (pintype "passive"))
      (node (ref "C8") (pin "2") (pinfunction "2_2") (pintype "passive"))
      (node (ref "C9") (pin "2") (pinfunction "2_2") (pintype "passive"))
      (node (ref "FB1") (pin "1") (pinfunction "1_1") (pintype "passive"))
      (node (ref "J2") (pin "4") (pinfunction "4_4") (pintype "passive"))
      (node (ref "L1") (pin "1") (pinfunction "1_1") (pintype "passive"))
      (node (ref "R114") (pin "1") (pinfunction "1_1") (pintype "passive"))
      (node (ref "R124") (pin "2") (pinfunction "2_2") (pintype "passive"))
      (node (ref "R125") (pin "2") (pinfunction "2_2") (pintype "passive"))
      (node (ref "R126") (pin "2") (pinfunction "2_2") (pintype "passive"))
      (node (ref "R128") (pin "2") (pinfunction "2_2") (pintype "passive"))
      (node (ref "U1") (pin "10") (pinfunction "~{RST}_10") (pintype "input"))
      (node (ref "U1") (pin "16") (pinfunction "VDD_16") (pintype "power_in"))
      (node (ref "U10") (pin "10") (pinfunction "~{RST}_10") (pintype "input"))
      (node (ref "U10") (pin "16") (pinfunction "VDD_16") (pintype "power_in"))
      (node (ref "U11") (pin "10") (pinfunction "~{RST}_10") (pintype "input"))
      (node (ref "U11") (pin "16") (pinfunction "VDD_16") (pintype "power_in"))
      (node (ref "U12") (pin "10") (pinfunction "~{RST}_10") (pintype "input"))
      (node (ref "U12") (pin "16") (pinfunction "VDD_16") (pintype "power_in"))
      (node (ref "U13") (pin "10") (pinfunction "~{RST}_10") (pintype "input"))
      (node (ref "U13") (pin "16") (pinfunction "VDD_16") (pintype "power_in"))
      (node (ref "U17") (pin "2") (pinfunction "Vcc_2") (pintype "passive"))
      (node (ref "U18") (pin "1") (pinfunction "VBAT_1") (pintype "power_in"))
      (node (ref "U18") (pin "24") (pinfunction "VDD_1_24") (pintype "power_in"))
      (node (ref "U18") (pin "36") (pinfunction "VDD_2_36") (pintype "power_in"))
      (node (ref "U18") (pin "48") (pinfunction "VDD_3_48") (pintype "power_in"))
      (node (ref "U18") (pin "9") (pinfunction "VDDA_9") (pintype "power_in"))
      (node (ref "U2") (pin "10") (pinfunction "~{RST}_10") (pintype "input"))
      (node (ref "U2") (pin "16") (pinfunction "VDD_16") (pintype "power_in"))
      (node (ref "U3") (pin "10") (pinfunction "~{RST}_10") (pintype "input"))
      (node (ref "U3") (pin "16") (pinfunction "VDD_16") (pintype "power_in"))
      (node (ref "U4") (pin "10") (pinfunction "~{RST}_10") (pintype "input"))
      (node (ref "U4") (pin "16") (pinfunction "VDD_16") (pintype "power_in"))
      (node (ref "U5") (pin "10") (pinfunction "~{RST}_10") (pintype "input"))
      (node (ref "U5") (pin "16") (pinfunction "VDD_16") (pintype "power_in"))
      (node (ref "U6") (pin "10") (pinfunction "~{RST}_10") (pintype "input"))
      (node (ref "U6") (pin "16") (pinfunction "VDD_16") (pintype "power_in"))
      (node (ref "U7") (pin "10") (pinfunction "~{RST}_10") (pintype "input"))
      (node (ref "U7") (pin "16") (pinfunction "VDD_16") (pintype "power_in"))
      (node (ref "U8") (pin "10") (pinfunction "~{RST}_10") (pintype "input"))
      (node (ref "U8") (pin "16") (pinfunction "VDD_16") (pintype "power_in"))
      (node (ref "U9") (pin "10") (pinfunction "~{RST}_10") (pintype "input"))
      (node (ref "U9") (pin "16") (pinfunction "VDD_16") (pintype "power_in"))
    )
    (net (code "208") (name "Net-(U1-~{OE})") (class "Default")
      (node (ref "U1") (pin "13") (pinfunction "~{OE}_13") (pintype "input"))
      (node (ref "U10") (pin "13") (pinfunction "~{OE}_13") (pintype "input"))
      (node (ref "U11") (pin "13") (pinfunction "~{OE}_13") (pintype "input"))
      (node (ref "U12") (pin "13") (pinfunction "~{OE}_13") (pintype "input"))
      (node (ref "U13") (pin "13") (pinfunction "~{OE}_13") (pintype "input"))
      (node (ref "U18") (pin "19") (pinfunction "PB1_19") (pintype "bidirectional"))
      (node (ref "U2") (pin "13") (pinfunction "~{OE}_13") (pintype "input"))
      (node (ref "U3") (pin "13") (pinfunction "~{OE}_13") (pintype "input"))
      (node (ref "U4") (pin "13") (pinfunction "~{OE}_13") (pintype "input"))
      (node (ref "U5") (pin "13") (pinfunction "~{OE}_13") (pintype "input"))
      (node (ref "U6") (pin "13") (pinfunction "~{OE}_13") (pintype "input"))
      (node (ref "U7") (pin "13") (pinfunction "~{OE}_13") (pintype "input"))
      (node (ref "U8") (pin "13") (pinfunction "~{OE}_13") (pintype "input"))
      (node (ref "U9") (pin "13") (pinfunction "~{OE}_13") (pintype "input"))
    )
    (net (code "209") (name "Net-(U2-QB)") (class "Default")
      (node (ref "R55") (pin "2") (pinfunction "2_2") (pintype "passive"))
      (node (ref "U2") (pin "1") (pinfunction "QB_1") (pintype "tri_state"))
    )
    (net (code "210") (name "Net-(U2-QC)") (class "Default")
      (node (ref "R56") (pin "2") (pinfunction "2_2") (pintype "passive"))
      (node (ref "U2") (pin "2") (pinfunction "QC_2") (pintype "tri_state"))
    )
    (net (code "211") (name "Net-(U2-QE)") (class "Default")
      (node (ref "R81") (pin "2") (pinfunction "2_2") (pintype "passive"))
      (node (ref "U2") (pin "4") (pinfunction "QE_4") (pintype "tri_state"))
    )
    (net (code "212") (name "Net-(U2-QF)") (class "Default")
      (node (ref "R82") (pin "2") (pinfunction "2_2") (pintype "passive"))
      (node (ref "U2") (pin "5") (pinfunction "QF_5") (pintype "tri_state"))
    )
    (net (code "213") (name "Net-(U2-QH)") (class "Default")
      (node (ref "R97") (pin "2") (pinfunction "2_2") (pintype "passive"))
      (node (ref "U2") (pin "7") (pinfunction "QH_7") (pintype "tri_state"))
    )
    (net (code "214") (name "Net-(U2-SDI)") (class "Default")
      (node (ref "U2") (pin "14") (pinfunction "SDI_14") (pintype "input"))
      (node (ref "U3") (pin "9") (pinfunction "SDO_9") (pintype "output"))
    )
    (net (code "215") (name "Net-(U3-QB)") (class "Default")
      (node (ref "R96") (pin "2") (pinfunction "2_2") (pintype "passive"))
      (node (ref "U3") (pin "1") (pinfunction "QB_1") (pintype "tri_state"))
    )
    (net (code "216") (name "Net-(U3-QC)") (class "Default")
      (node (ref "R80") (pin "2") (pinfunction "2_2") (pintype "passive"))
      (node (ref "U3") (pin "2") (pinfunction "QC_2") (pintype "tri_state"))
    )
    (net (code "217") (name "Net-(U3-QE)") (class "Default")
      (node (ref "R79") (pin "2") (pinfunction "2_2") (pintype "passive"))
      (node (ref "U3") (pin "4") (pinfunction "QE_4") (pintype "tri_state"))
    )
    (net (code "218") (name "Net-(U3-QF)") (class "Default")
      (node (ref "R54") (pin "2") (pinfunction "2_2") (pintype "passive"))
      (node (ref "U3") (pin "5") (pinfunction "QF_5") (pintype "tri_state"))
    )
    (net (code "219") (name "Net-(U3-QH)") (class "Default")
      (node (ref "R53") (pin "2") (pinfunction "2_2") (pintype "passive"))
      (node (ref "U3") (pin "7") (pinfunction "QH_7") (pintype "tri_state"))
    )
    (net (code "220") (name "Net-(U3-SDI)") (class "Default")
      (node (ref "U3") (pin "14") (pinfunction "SDI_14") (pintype "input"))
      (node (ref "U4") (pin "9") (pinfunction "SDO_9") (pintype "output"))
    )
    (net (code "221") (name "Net-(U4-QB)") (class "Default")
      (node (ref "R51") (pin "2") (pinfunction "2_2") (pintype "passive"))
      (node (ref "U4") (pin "1") (pinfunction "QB_1") (pintype "tri_state"))
    )
    (net (code "222") (name "Net-(U4-QC)") (class "Default")
      (node (ref "R52") (pin "2") (pinfunction "2_2") (pintype "passive"))
      (node (ref "U4") (pin "2") (pinfunction "QC_2") (pintype "tri_state"))
    )
    (net (code "223") (name "Net-(U4-QE)") (class "Default")
      (node (ref "R77") (pin "2") (pinfunction "2_2") (pintype "passive"))
      (node (ref "U4") (pin "4") (pinfunction "QE_4") (pintype "tri_state"))
    )
    (net (code "224") (name "Net-(U4-QF)") (class "Default")
      (node (ref "R78") (pin "2") (pinfunction "2_2") (pintype "passive"))
      (node (ref "U4") (pin "5") (pinfunction "QF_5") (pintype "tri_state"))
    )
    (net (code "225") (name "Net-(U4-QH)") (class "Default")
      (node (ref "R95") (pin "2") (pinfunction "2_2") (pintype "passive"))
      (node (ref "U4") (pin "7") (pinfunction "QH_7") (pintype "tri_state"))
    )
    (net (code "226") (name "Net-(U4-SDI)") (class "Default")
      (node (ref "U4") (pin "14") (pinfunction "SDI_14") (pintype "input"))
      (node (ref "U5") (pin "9") (pinfunction "SDO_9") (pintype "output"))
    )
    (net (code "227") (name "Net-(U5-QB)") (class "Default")
      (node (ref "R93") (pin "2") (pinfunction "2_2") (pintype "passive"))
      (node (ref "U5") (pin "1") (pinfunction "QB_1") (pintype "tri_state"))
    )
    (net (code "228") (name "Net-(U5-QC)") (class "Default")
      (node (ref "R75") (pin "2") (pinfunction "2_2") (pintype "passive"))
      (node (ref "U5") (pin "2") (pinfunction "QC_2") (pintype "tri_state"))
    )
    (net (code "229") (name "Net-(U5-QE)") (class "Default")
      (node (ref "R74") (pin "2") (pinfunction "2_2") (pintype "passive"))
      (node (ref "U5") (pin "4") (pinfunction "QE_4") (pintype "tri_state"))
    )
    (net (code "230") (name "Net-(U5-QF)") (class "Default")
      (node (ref "R50") (pin "2") (pinfunction "2_2") (pintype "passive"))
      (node (ref "U5") (pin "5") (pinfunction "QF_5") (pintype "tri_state"))
    )
    (net (code "231") (name "Net-(U5-QH)") (class "Default")
      (node (ref "R49") (pin "2") (pinfunction "2_2") (pintype "passive"))
      (node (ref "U5") (pin "7") (pinfunction "QH_7") (pintype "tri_state"))
    )
    (net (code "232") (name "Net-(U5-SDI)") (class "Default")
      (node (ref "U5") (pin "14") (pinfunction "SDI_14") (pintype "input"))
      (node (ref "U6") (pin "9") (pinfunction "SDO_9") (pintype "output"))
    )
    (net (code "233") (name "Net-(U6-QB)") (class "Default")
      (node (ref "R47") (pin "2") (pinfunction "2_2") (pintype "passive"))
      (node (ref "U6") (pin "1") (pinfunction "QB_1") (pintype "tri_state"))
    )
    (net (code "234") (name "Net-(U6-QC)") (class "Default")
      (node (ref "R48") (pin "2") (pinfunction "2_2") (pintype "passive"))
      (node (ref "U6") (pin "2") (pinfunction "QC_2") (pintype "tri_state"))
    )
    (net (code "235") (name "Net-(U6-QE)") (class "Default")
      (node (ref "R72") (pin "2") (pinfunction "2_2") (pintype "passive"))
      (node (ref "U6") (pin "4") (pinfunction "QE_4") (pintype "tri_state"))
    )
    (net (code "236") (name "Net-(U6-QF)") (class "Default")
      (node (ref "R73") (pin "2") (pinfunction "2_2") (pintype "passive"))
      (node (ref "U6") (pin "5") (pinfunction "QF_5") (pintype "tri_state"))
    )
    (net (code "237") (name "Net-(U6-QH)") (class "Default")
      (node (ref "R92") (pin "2") (pinfunction "2_2") (pintype "passive"))
      (node (ref "U6") (pin "7") (pinfunction "QH_7") (pintype "tri_state"))
    )
    (net (code "238") (name "Net-(U6-SDI)") (class "Default")
      (node (ref "U6") (pin "14") (pinfunction "SDI_14") (pintype "input"))
      (node (ref "U7") (pin "9") (pinfunction "SDO_9") (pintype "output"))
    )
    (net (code "239") (name "Net-(U7-QB)") (class "Default")
      (node (ref "R91") (pin "2") (pinfunction "2_2") (pintype "passive"))
      (node (ref "U7") (pin "1") (pinfunction "QB_1") (pintype "tri_state"))
    )
    (net (code "240") (name "Net-(U7-QC)") (class "Default")
      (node (ref "R71") (pin "2") (pinfunction "2_2") (pintype "passive"))
      (node (ref "U7") (pin "2") (pinfunction "QC_2") (pintype "tri_state"))
    )
    (net (code "241") (name "Net-(U7-QE)") (class "Default")
      (node (ref "R70") (pin "2") (pinfunction "2_2") (pintype "passive"))
      (node (ref "U7") (pin "4") (pinfunction "QE_4") (pintype "tri_state"))
    )
    (net (code "242") (name "Net-(U7-QF)") (class "Default")
      (node (ref "R46") (pin "2") (pinfunction "2_2") (pintype "passive"))
      (node (ref "U7") (pin "5") (pinfunction "QF_5") (pintype "tri_state"))
    )
    (net (code "243") (name "Net-(U7-QH)") (class "Default")
      (node (ref "R45") (pin "2") (pinfunction "2_2") (pintype "passive"))
      (node (ref "U7") (pin "7") (pinfunction "QH_7") (pintype "tri_state"))
    )
    (net (code "244") (name "Net-(U7-SDI)") (class "Default")
      (node (ref "U7") (pin "14") (pinfunction "SDI_14") (pintype "input"))
      (node (ref "U8") (pin "9") (pinfunction "SDO_9") (pintype "output"))
    )
    (net (code "245") (name "Net-(U8-QB)") (class "Default")
      (node (ref "R43") (pin "2") (pinfunction "2_2") (pintype "passive"))
      (node (ref "U8") (pin "1") (pinfunction "QB_1") (pintype "tri_state"))
    )
    (net (code "246") (name "Net-(U8-QC)") (class "Default")
      (node (ref "R44") (pin "2") (pinfunction "2_2") (pintype "passive"))
      (node (ref "U8") (pin "2") (pinfunction "QC_2") (pintype "tri_state"))
    )
    (net (code "247") (name "Net-(U8-QE)") (class "Default")
      (node (ref "R68") (pin "2") (pinfunction "2_2") (pintype "passive"))
      (node (ref "U8") (pin "4") (pinfunction "QE_4") (pintype "tri_state"))
    )
    (net (code "248") (name "Net-(U8-QF)") (class "Default")
      (node (ref "R69") (pin "2") (pinfunction "2_2") (pintype "passive"))
      (node (ref "U8") (pin "5") (pinfunction "QF_5") (pintype "tri_state"))
    )
    (net (code "249") (name "Net-(U8-QH)") (class "Default")
      (node (ref "R90") (pin "2") (pinfunction "2_2") (pintype "passive"))
      (node (ref "U8") (pin "7") (pinfunction "QH_7") (pintype "tri_state"))
    )
    (net (code "250") (name "Net-(U8-SDI)") (class "Default")
      (node (ref "U8") (pin "14") (pinfunction "SDI_14") (pintype "input"))
      (node (ref "U9") (pin "9") (pinfunction "SDO_9") (pintype "output"))
    )
    (net (code "251") (name "Net-(U9-QB)") (class "Default")
      (node (ref "R88") (pin "2") (pinfunction "2_2") (pintype "passive"))
      (node (ref "U9") (pin "1") (pinfunction "QB_1") (pintype "tri_state"))
    )
    (net (code "252") (name "Net-(U9-QC)") (class "Default")
      (node (ref "R66") (pin "2") (pinfunction "2_2") (pintype "passive"))
      (node (ref "U9") (pin "2") (pinfunction "QC_2") (pintype "tri_state"))
    )
    (net (code "253") (name "Net-(U9-QE)") (class "Default")
      (node (ref "R65") (pin "2") (pinfunction "2_2") (pintype "passive"))
      (node (ref "U9") (pin "4") (pinfunction "QE_4") (pintype "tri_state"))
    )
    (net (code "254") (name "Net-(U9-QF)") (class "Default")
      (node (ref "R42") (pin "2") (pinfunction "2_2") (pintype "passive"))
      (node (ref "U9") (pin "5") (pinfunction "QF_5") (pintype "tri_state"))
    )
    (net (code "255") (name "Net-(U9-QH)") (class "Default")
      (node (ref "R41") (pin "2") (pinfunction "2_2") (pintype "passive"))
      (node (ref "U9") (pin "7") (pinfunction "QH_7") (pintype "tri_state"))
    )
    (net (code "256") (name "Net-(U10-QB)") (class "Default")
      (node (ref "R39") (pin "2") (pinfunction "2_2") (pintype "passive"))
      (node (ref "U10") (pin "1") (pinfunction "QB_1") (pintype "tri_state"))
    )
    (net (code "257") (name "Net-(U10-QC)") (class "Default")
      (node (ref "R40") (pin "2") (pinfunction "2_2") (pintype "passive"))
      (node (ref "U10") (pin "2") (pinfunction "QC_2") (pintype "tri_state"))
    )
    (net (code "258") (name "Net-(U10-QE)") (class "Default")
      (node (ref "R63") (pin "2") (pinfunction "2_2") (pintype "passive"))
      (node (ref "U10") (pin "4") (pinfunction "QE_4") (pintype "tri_state"))
    )
    (net (code "259") (name "Net-(U10-QF)") (class "Default")
      (node (ref "R64") (pin "2") (pinfunction "2_2") (pintype "passive"))
      (node (ref "U10") (pin "5") (pinfunction "QF_5") (pintype "tri_state"))
    )
    (net (code "260") (name "Net-(U10-QH)") (class "Default")
      (node (ref "R87") (pin "2") (pinfunction "2_2") (pintype "passive"))
      (node (ref "U10") (pin "7") (pinfunction "QH_7") (pintype "tri_state"))
    )
    (net (code "261") (name "Net-(U10-SDI)") (class "Default")
      (node (ref "U10") (pin "14") (pinfunction "SDI_14") (pintype "input"))
      (node (ref "U11") (pin "9") (pinfunction "SDO_9") (pintype "output"))
    )
    (net (code "262") (name "Net-(U10-SDO)") (class "Default")
      (node (ref "U10") (pin "9") (pinfunction "SDO_9") (pintype "output"))
      (node (ref "U9") (pin "14") (pinfunction "SDI_14") (pintype "input"))
    )
    (net (code "263") (name "Net-(U11-QB)") (class "Default")
      (node (ref "R86") (pin "2") (pinfunction "2_2") (pintype "passive"))
      (node (ref "U11") (pin "1") (pinfunction "QB_1") (pintype "tri_state"))
    )
    (net (code "264") (name "Net-(U11-QC)") (class "Default")
      (node (ref "R62") (pin "2") (pinfunction "2_2") (pintype "passive"))
      (node (ref "U11") (pin "2") (pinfunction "QC_2") (pintype "tri_state"))
    )
    (net (code "265") (name "Net-(U11-QE)") (class "Default")
      (node (ref "R61") (pin "2") (pinfunction "2_2") (pintype "passive"))
      (node (ref "U11") (pin "4") (pinfunction "QE_4") (pintype "tri_state"))
    )
    (net (code "266") (name "Net-(U11-QF)") (class "Default")
      (node (ref "R38") (pin "2") (pinfunction "2_2") (pintype "passive"))
      (node (ref "U11") (pin "5") (pinfunction "QF_5") (pintype "tri_state"))
    )
    (net (code "267") (name "Net-(U11-QH)") (class "Default")
      (node (ref "R37") (pin "2") (pinfunction "2_2") (pintype "passive"))
      (node (ref "U11") (pin "7") (pinfunction "QH_7") (pintype "tri_state"))
    )
    (net (code "268") (name "Net-(U11-SDI)") (class "Default")
      (node (ref "U11") (pin "14") (pinfunction "SDI_14") (pintype "input"))
      (node (ref "U12") (pin "9") (pinfunction "SDO_9") (pintype "output"))
    )
    (net (code "269") (name "Net-(U12-QB)") (class "Default")
      (node (ref "R35") (pin "2") (pinfunction "2_2") (pintype "passive"))
      (node (ref "U12") (pin "1") (pinfunction "QB_1") (pintype "tri_state"))
    )
    (net (code "270") (name "Net-(U12-QC)") (class "Default")
      (node (ref "R36") (pin "2") (pinfunction "2_2") (pintype "passive"))
      (node (ref "U12") (pin "2") (pinfunction "QC_2") (pintype "tri_state"))
    )
    (net (code "271") (name "Net-(U12-QE)") (class "Default")
      (node (ref "R59") (pin "2") (pinfunction "2_2") (pintype "passive"))
      (node (ref "U12") (pin "4") (pinfunction "QE_4") (pintype "tri_state"))
    )
    (net (code "272") (name "Net-(U12-QF)") (class "Default")
      (node (ref "R60") (pin "2") (pinfunction "2_2") (pintype "passive"))
      (node (ref "U12") (pin "5") (pinfunction "QF_5") (pintype "tri_state"))
    )
    (net (code "273") (name "Net-(U12-QH)") (class "Default")
      (node (ref "R85") (pin "2") (pinfunction "2_2") (pintype "passive"))
      (node (ref "U12") (pin "7") (pinfunction "QH_7") (pintype "tri_state"))
    )
    (net (code "274") (name "Net-(U12-SDI)") (class "Default")
      (node (ref "U12") (pin "14") (pinfunction "SDI_14") (pintype "input"))
      (node (ref "U13") (pin "9") (pinfunction "SDO_9") (pintype "output"))
    )
    (net (code "275") (name "Net-(U13-QB)") (class "Default")
      (node (ref "R32") (pin "1") (pinfunction "1_1") (pintype "passive"))
      (node (ref "U13") (pin "1") (pinfunction "QB_1") (pintype "tri_state"))
    )
    (net (code "276") (name "Net-(U13-QD)") (class "Default")
      (node (ref "R33") (pin "2") (pinfunction "2_2") (pintype "passive"))
      (node (ref "U13") (pin "3") (pinfunction "QD_3") (pintype "tri_state"))
    )
    (net (code "277") (name "Net-(U13-QF)") (class "Default")
      (node (ref "R100") (pin "1") (pinfunction "1_1") (pintype "passive"))
      (node (ref "R140") (pin "1") (pinfunction "1_1") (pintype "passive"))
      (node (ref "R99") (pin "1") (pinfunction "1_1") (pintype "passive"))
      (node (ref "U13") (pin "5") (pinfunction "QF_5") (pintype "tri_state"))
    )
    (net (code "278") (name "Net-(U13-SDI)") (class "Default")
      (node (ref "U13") (pin "14") (pinfunction "SDI_14") (pintype "input"))
      (node (ref "U18") (pin "27") (pinfunction "PB14_27") (pintype "bidirectional"))
    )
    (net (code "279") (name "Net-(U14-CT)") (class "Default")
      (node (ref "C18") (pin "1") (pinfunction "1_1") (pintype "passive"))
      (node (ref "R101") (pin "1") (pinfunction "1_1") (pintype "passive"))
      (node (ref "U14") (pin "3") (pinfunction "CT_3") (pintype "passive"))
    )
    (net (code "280") (name "Net-(U14-HO)") (class "Default")
      (node (ref "R102") (pin "1") (pinfunction "1_1") (pintype "passive"))
      (node (ref "U14") (pin "7") (pinfunction "HO_7") (pintype "output"))
    )
    (net (code "281") (name "Net-(U14-LO)") (class "Default")
      (node (ref "R103") (pin "2") (pinfunction "2_2") (pintype "passive"))
      (node (ref "U14") (pin "5") (pinfunction "LO_5") (pintype "output"))
    )
    (net (code "282") (name "Net-(U14-RT)") (class "Default")
      (node (ref "R101") (pin "2") (pinfunction "2_2") (pintype "passive"))
      (node (ref "U14") (pin "2") (pinfunction "RT_2") (pintype "passive"))
    )
    (net (code "283") (name "Net-(U14-VB)") (class "Default")
      (node (ref "C17") (pin "1") (pinfunction "1_1") (pintype "passive"))
      (node (ref "R136") (pin "1") (pinfunction "1_1") (pintype "passive"))
      (node (ref "U14") (pin "1") (pinfunction "VCC_1") (pintype "power_in"))
      (node (ref "U14") (pin "8") (pinfunction "VB_8") (pintype "power_in"))
    )
    (net (code "284") (name "Net-(U15-BS)") (class "Default")
      (node (ref "C21") (pin "2") (pinfunction "2_2") (pintype "passive"))
      (node (ref "U15") (pin "1") (pinfunction "BS_1") (pintype "passive"))
    )
    (net (code "285") (name "Net-(U15-COMP)") (class "Default")
      (node (ref "R113") (pin "2") (pinfunction "2_2") (pintype "passive"))
      (node (ref "U15") (pin "6") (pinfunction "COMP_6") (pintype "passive"))
    )
    (net (code "286") (name "Net-(U15-EN)") (class "Default")
      (node (ref "R112") (pin "2") (pinfunction "2_2") (pintype "passive"))
      (node (ref "U15") (pin "7") (pinfunction "EN_7") (pintype "passive"))
    )
    (net (code "287") (name "Net-(U15-FB)") (class "Default")
      (node (ref "R114") (pin "2") (pinfunction "2_2") (pintype "passive"))
      (node (ref "R115") (pin "2") (pinfunction "2_2") (pintype "passive"))
      (node (ref "U15") (pin "5") (pinfunction "FB_5") (pintype "passive"))
    )
    (net (code "288") (name "Net-(U15-SS)") (class "Default")
      (node (ref "C22") (pin "1") (pinfunction "1_1") (pintype "passive"))
      (node (ref "U15") (pin "8") (pinfunction "SS_8") (pintype "passive"))
    )
    (net (code "289") (name "Net-(U15-SW)") (class "Default")
      (node (ref "C21") (pin "1") (pinfunction "1_1") (pintype "passive"))
      (node (ref "L1") (pin "2") (pinfunction "2_2") (pintype "passive"))
      (node (ref "U15") (pin "3") (pinfunction "SW_3") (pintype "passive"))
    )
    (net (code "290") (name "Net-(U16A-A)") (class "Default")
      (node (ref "C32") (pin "2") (pinfunction "2_2") (pintype "passive"))
      (node (ref "R123") (pin "2") (pinfunction "2_2") (pintype "passive"))
      (node (ref "U16") (pin "1") (pinfunction "A_1") (pintype "input"))
    )
    (net (code "291") (name "Net-(U16A-Y)") (class "Default")
      (node (ref "R123") (pin "1") (pinfunction "1_1") (pintype "passive"))
      (node (ref "U16") (pin "2") (pinfunction "Y_2") (pintype "output"))
      (node (ref "U16") (pin "3") (pinfunction "A_3") (pintype "input"))
    )
    (net (code "292") (name "Net-(U16B-Y)") (class "Default")
      (node (ref "U16") (pin "4") (pinfunction "Y_4") (pintype "output"))
      (node (ref "U16") (pin "5") (pinfunction "A_5") (pintype "input"))
    )
    (net (code "293") (name "Net-(U16C-Y)") (class "Default")
      (node (ref "R122") (pin "2") (pinfunction "2_2") (pintype "passive"))
      (node (ref "U16") (pin "6") (pinfunction "Y_6") (pintype "output"))
    )
    (net (code "294") (name "Net-(U16D-A)") (class "Default")
      (node (ref "R118") (pin "1") (pinfunction "1_1") (pintype "passive"))
      (node (ref "U16") (pin "10") (pinfunction "Y_10") (pintype "output"))
      (node (ref "U16") (pin "9") (pinfunction "A_9") (pintype "input"))
    )
    (net (code "295") (name "Net-(U16D-Y)") (class "Default")
      (node (ref "R121") (pin "2") (pinfunction "2_2") (pintype "passive"))
      (node (ref "U16") (pin "8") (pinfunction "Y_8") (pintype "output"))
    )
    (net (code "296") (name "Net-(U16E-A)") (class "Default")
      (node (ref "R120") (pin "1") (pinfunction "1_1") (pintype "passive"))
      (node (ref "U16") (pin "11") (pinfunction "A_11") (pintype "input"))
      (node (ref "U16") (pin "12") (pinfunction "Y_12") (pintype "output"))
    )
    (net (code "297") (name "Net-(U16F-A)") (class "Default")
      (node (ref "R118") (pin "2") (pinfunction "2_2") (pintype "passive"))
      (node (ref "R119") (pin "1") (pinfunction "1_1") (pintype "passive"))
      (node (ref "U16") (pin "13") (pinfunction "A_13") (pintype "input"))
    )
    (net (code "298") (name "Net-(U17-SCL)") (class "Default")
      (node (ref "R125") (pin "1") (pinfunction "1_1") (pintype "passive"))
      (node (ref "U17") (pin "16") (pinfunction "SCL_16") (pintype "passive"))
      (node (ref "U18") (pin "42") (pinfunction "PB6_42") (pintype "bidirectional"))
    )
    (net (code "299") (name "Net-(U17-SDA)") (class "Default")
      (node (ref "R124") (pin "1") (pinfunction "1_1") (pintype "passive"))
      (node (ref "U17") (pin "15") (pinfunction "SDA_15") (pintype "passive"))
      (node (ref "U18") (pin "43") (pinfunction "PB7_43") (pintype "bidirectional"))
    )
    (net (code "300") (name "Net-(U18A-BOOT0)") (class "Default")
      (node (ref "R127") (pin "1") (pinfunction "1_1") (pintype "passive"))
      (node (ref "U18") (pin "44") (pinfunction "BOOT0_44") (pintype "input"))
    )
    (net (code "301") (name "Net-(U18A-NRST)") (class "Default")
      (node (ref "C40") (pin "1") (pinfunction "1_1") (pintype "passive"))
      (node (ref "R128") (pin "1") (pinfunction "1_1") (pintype "passive"))
      (node (ref "U18") (pin "7") (pinfunction "NRST_7") (pintype "bidirectional"))
    )
    (net (code "302") (name "Net-(U18A-PA0-WKUP)") (class "Default")
      (node (ref "C44") (pin "2") (pinfunction "2_2") (pintype "passive"))
      (node (ref "R129") (pin "1") (pinfunction "1_1") (pintype "passive"))
      (node (ref "SB1") (pin "2") (pinfunction "2_2") (pintype "passive"))
      (node (ref "U18") (pin "10") (pinfunction "PA0-WKUP_10") (pintype "bidirectional"))
    )
    (net (code "303") (name "Net-(U18A-PA1)") (class "Default")
      (node (ref "C43") (pin "2") (pinfunction "2_2") (pintype "passive"))
      (node (ref "R130") (pin "1") (pinfunction "1_1") (pintype "passive"))
      (node (ref "SB2") (pin "2") (pinfunction "2_2") (pintype "passive"))
      (node (ref "U18") (pin "11") (pinfunction "PA1_11") (pintype "bidirectional"))
    )
    (net (code "304") (name "Net-(U18A-PA2)") (class "Default")
      (node (ref "C42") (pin "2") (pinfunction "2_2") (pintype "passive"))
      (node (ref "R131") (pin "1") (pinfunction "1_1") (pintype "passive"))
      (node (ref "SB3") (pin "2") (pinfunction "2_2") (pintype "passive"))
      (node (ref "U18") (pin "12") (pinfunction "PA2_12") (pintype "bidirectional"))
    )
    (net (code "305") (name "Net-(U18A-PA5)") (class "Default")
      (node (ref "C45") (pin "1") (pinfunction "1_1") (pintype "passive"))
      (node (ref "R132") (pin "2") (pinfunction "2_2") (pintype "passive"))
      (node (ref "U18") (pin "15") (pinfunction "PA5_15") (pintype "bidirectional"))
    )
    (net (code "306") (name "Net-(U18A-PA13)") (class "Default")
      (node (ref "J2") (pin "3") (pinfunction "3_3") (pintype "passive"))
      (node (ref "U18") (pin "34") (pinfunction "PA13_34") (pintype "bidirectional"))
    )
    (net (code "307") (name "Net-(U18A-PA14)") (class "Default")
      (node (ref "J2") (pin "2") (pinfunction "2_2") (pintype "passive"))
      (node (ref "U18") (pin "37") (pinfunction "PA14_37") (pintype "bidirectional"))
    )
    (net (code "308") (name "Net-(U18A-PB2)") (class "Default")
      (node (ref "R133") (pin "1") (pinfunction "1_1") (pintype "passive"))
      (node (ref "U18") (pin "20") (pinfunction "PB2_20") (pintype "bidirectional"))
    )
    (net (code "309") (name "Net-(U18A-PD0-OSC_IN)") (class "Default")
      (node (ref "C36") (pin "1") (pinfunction "1_1") (pintype "passive"))
      (node (ref "U18") (pin "5") (pinfunction "PD0-OSC_IN_5") (pintype "bidirectional"))
      (node (ref "ZQ1") (pin "2") (pinfunction "2_2") (pintype "passive"))
    )
    (net (code "310") (name "Net-(U18A-PD1-OSC_OUT)") (class "Default")
      (node (ref "C39") (pin "1") (pinfunction "1_1") (pintype "passive"))
      (node (ref "U18") (pin "6") (pinfunction "PD1-OSC_OUT_6") (pintype "bidirectional"))
      (node (ref "ZQ1") (pin "1") (pinfunction "1_1") (pintype "passive"))
    )
    (net (code "311") (name "Net-(VD8-K)") (class "Default")
      (node (ref "VD8") (pin "2") (pinfunction "K_2") (pintype "passive"))
      (node (ref "VD9") (pin "1") (pinfunction "A_1") (pintype "passive"))
    )
    (net (code "312") (name "Net-(VD10-A)") (class "Default")
      (node (ref "R116") (pin "1") (pinfunction "1_1") (pintype "passive"))
      (node (ref "VD10") (pin "1") (pinfunction "A_1") (pintype "passive"))
      (node (ref "VD8") (pin "1") (pinfunction "A_1") (pintype "passive"))
    )
    (net (code "313") (name "Net-(VD11-K)") (class "Default")
      (node (ref "C27") (pin "2") (pinfunction "2_2") (pintype "passive"))
      (node (ref "C29") (pin "1") (pinfunction "1_1") (pintype "passive"))
      (node (ref "VD11") (pin "2") (pinfunction "K_2") (pintype "passive"))
      (node (ref "VD12") (pin "1") (pinfunction "A_1") (pintype "passive"))
    )
    (net (code "314") (name "Net-(VL1-A)") (class "Default")
      (node (ref "R3") (pin "2") (pinfunction "2_2") (pintype "passive"))
      (node (ref "VL1") (pin "1") (pinfunction "A_1") (pintype "passive"))
    )
    (net (code "315") (name "VDD") (class "Default")
      (node (ref "C27") (pin "1") (pinfunction "1_1") (pintype "passive"))
      (node (ref "C28") (pin "1") (pinfunction "1_1") (pintype "passive"))
      (node (ref "C33") (pin "2") (pinfunction "2_2") (pintype "passive"))
      (node (ref "Q67") (pin "3") (pinfunction "S_3") (pintype "passive"))
      (node (ref "R117") (pin "2") (pinfunction "2_2") (pintype "passive"))
      (node (ref "U16") (pin "14") (pinfunction "VDD_14") (pintype "power_in"))
      (node (ref "U17") (pin "14") (pinfunction "Vbatt_14") (pintype "passive"))
      (node (ref "VD10") (pin "2") (pinfunction "K_2") (pintype "passive"))
      (node (ref "VD11") (pin "1") (pinfunction "A_1") (pintype "passive"))
    )
    (net (code "316") (name "unconnected-(U1-QA-Pad15)") (class "Default")
      (node (ref "U1") (pin "15") (pinfunction "QA_15") (pintype "tri_state"))
    )
    (net (code "317") (name "unconnected-(U1-QD-Pad3)") (class "Default")
      (node (ref "U1") (pin "3") (pinfunction "QD_3") (pintype "tri_state"))
    )
    (net (code "318") (name "unconnected-(U1-QG-Pad6)") (class "Default")
      (node (ref "U1") (pin "6") (pinfunction "QG_6") (pintype "tri_state"))
    )
    (net (code "319") (name "unconnected-(U1-SDO-Pad9)") (class "Default")
      (node (ref "U1") (pin "9") (pinfunction "SDO_9") (pintype "output"))
    )
    (net (code "320") (name "unconnected-(U2-QA-Pad15)") (class "Default")
      (node (ref "U2") (pin "15") (pinfunction "QA_15") (pintype "tri_state"))
    )
    (net (code "321") (name "unconnected-(U2-QD-Pad3)") (class "Default")
      (node (ref "U2") (pin "3") (pinfunction "QD_3") (pintype "tri_state"))
    )
    (net (code "322") (name "unconnected-(U2-QG-Pad6)") (class "Default")
      (node (ref "U2") (pin "6") (pinfunction "QG_6") (pintype "tri_state"))
    )
    (net (code "323") (name "unconnected-(U3-QA-Pad15)") (class "Default")
      (node (ref "U3") (pin "15") (pinfunction "QA_15") (pintype "tri_state"))
    )
    (net (code "324") (name "unconnected-(U3-QD-Pad3)") (class "Default")
      (node (ref "U3") (pin "3") (pinfunction "QD_3") (pintype "tri_state"))
    )
    (net (code "325") (name "unconnected-(U3-QG-Pad6)") (class "Default")
      (node (ref "U3") (pin "6") (pinfunction "QG_6") (pintype "tri_state"))
    )
    (net (code "326") (name "unconnected-(U4-QA-Pad15)") (class "Default")
      (node (ref "U4") (pin "15") (pinfunction "QA_15") (pintype "tri_state"))
    )
    (net (code "327") (name "unconnected-(U4-QD-Pad3)") (class "Default")
      (node (ref "U4") (pin "3") (pinfunction "QD_3") (pintype "tri_state"))
    )
    (net (code "328") (name "unconnected-(U4-QG-Pad6)") (class "Default")
      (node (ref "U4") (pin "6") (pinfunction "QG_6") (pintype "tri_state"))
    )
    (net (code "329") (name "unconnected-(U5-QA-Pad15)") (class "Default")
      (node (ref "U5") (pin "15") (pinfunction "QA_15") (pintype "tri_state"))
    )
    (net (code "330") (name "unconnected-(U5-QD-Pad3)") (class "Default")
      (node (ref "U5") (pin "3") (pinfunction "QD_3") (pintype "tri_state"))
    )
    (net (code "331") (name "unconnected-(U5-QG-Pad6)") (class "Default")
      (node (ref "U5") (pin "6") (pinfunction "QG_6") (pintype "tri_state"))
    )
    (net (code "332") (name "unconnected-(U6-QA-Pad15)") (class "Default")
      (node (ref "U6") (pin "15") (pinfunction "QA_15") (pintype "tri_state"))
    )
    (net (code "333") (name "unconnected-(U6-QD-Pad3)") (class "Default")
      (node (ref "U6") (pin "3") (pinfunction "QD_3") (pintype "tri_state"))
    )
    (net (code "334") (name "unconnected-(U6-QG-Pad6)") (class "Default")
      (node (ref "U6") (pin "6") (pinfunction "QG_6") (pintype "tri_state"))
    )
    (net (code "335") (name "unconnected-(U7-QA-Pad15)") (class "Default")
      (node (ref "U7") (pin "15") (pinfunction "QA_15") (pintype "tri_state"))
    )
    (net (code "336") (name "unconnected-(U7-QD-Pad3)") (class "Default")
      (node (ref "U7") (pin "3") (pinfunction "QD_3") (pintype "tri_state"))
    )
    (net (code "337") (name "unconnected-(U7-QG-Pad6)") (class "Default")
      (node (ref "U7") (pin "6") (pinfunction "QG_6") (pintype "tri_state"))
    )
    (net (code "338") (name "unconnected-(U8-QA-Pad15)") (class "Default")
      (node (ref "U8") (pin "15") (pinfunction "QA_15") (pintype "tri_state"))
    )
    (net (code "339") (name "unconnected-(U8-QD-Pad3)") (class "Default")
      (node (ref "U8") (pin "3") (pinfunction "QD_3") (pintype "tri_state"))
    )
    (net (code "340") (name "unconnected-(U8-QG-Pad6)") (class "Default")
      (node (ref "U8") (pin "6") (pinfunction "QG_6") (pintype "tri_state"))
    )
    (net (code "341") (name "unconnected-(U9-QA-Pad15)") (class "Default")
      (node (ref "U9") (pin "15") (pinfunction "QA_15") (pintype "tri_state"))
    )
    (net (code "342") (name "unconnected-(U9-QD-Pad3)") (class "Default")
      (node (ref "U9") (pin "3") (pinfunction "QD_3") (pintype "tri_state"))
    )
    (net (code "343") (name "unconnected-(U9-QG-Pad6)") (class "Default")
      (node (ref "U9") (pin "6") (pinfunction "QG_6") (pintype "tri_state"))
    )
    (net (code "344") (name "unconnected-(U10-QA-Pad15)") (class "Default")
      (node (ref "U10") (pin "15") (pinfunction "QA_15") (pintype "tri_state"))
    )
    (net (code "345") (name "unconnected-(U10-QD-Pad3)") (class "Default")
      (node (ref "U10") (pin "3") (pinfunction "QD_3") (pintype "tri_state"))
    )
    (net (code "346") (name "unconnected-(U10-QG-Pad6)") (class "Default")
      (node (ref "U10") (pin "6") (pinfunction "QG_6") (pintype "tri_state"))
    )
    (net (code "347") (name "unconnected-(U11-QA-Pad15)") (class "Default")
      (node (ref "U11") (pin "15") (pinfunction "QA_15") (pintype "tri_state"))
    )
    (net (code "348") (name "unconnected-(U11-QD-Pad3)") (class "Default")
      (node (ref "U11") (pin "3") (pinfunction "QD_3") (pintype "tri_state"))
    )
    (net (code "349") (name "unconnected-(U11-QG-Pad6)") (class "Default")
      (node (ref "U11") (pin "6") (pinfunction "QG_6") (pintype "tri_state"))
    )
    (net (code "350") (name "unconnected-(U12-QA-Pad15)") (class "Default")
      (node (ref "U12") (pin "15") (pinfunction "QA_15") (pintype "tri_state"))
    )
    (net (code "351") (name "unconnected-(U12-QD-Pad3)") (class "Default")
      (node (ref "U12") (pin "3") (pinfunction "QD_3") (pintype "tri_state"))
    )
    (net (code "352") (name "unconnected-(U12-QG-Pad6)") (class "Default")
      (node (ref "U12") (pin "6") (pinfunction "QG_6") (pintype "tri_state"))
    )
    (net (code "353") (name "unconnected-(U13-QA-Pad15)") (class "Default")
      (node (ref "U13") (pin "15") (pinfunction "QA_15") (pintype "tri_state"))
    )
    (net (code "354") (name "unconnected-(U13-QC-Pad2)") (class "Default")
      (node (ref "U13") (pin "2") (pinfunction "QC_2") (pintype "tri_state"))
    )
    (net (code "355") (name "unconnected-(U13-QE-Pad4)") (class "Default")
      (node (ref "U13") (pin "4") (pinfunction "QE_4") (pintype "tri_state"))
    )
    (net (code "356") (name "unconnected-(U13-QG-Pad6)") (class "Default")
      (node (ref "U13") (pin "6") (pinfunction "QG_6") (pintype "tri_state"))
    )
    (net (code "357") (name "unconnected-(U13-QH-Pad7)") (class "Default")
      (node (ref "U13") (pin "7") (pinfunction "QH_7") (pintype "tri_state"))
    )
    (net (code "358") (name "unconnected-(U17-32K-Pad1)") (class "Default")
      (node (ref "U17") (pin "1") (pinfunction "32K_1") (pintype "passive"))
    )
    (net (code "359") (name "unconnected-(U17-_RST_-Pad4)") (class "Default")
      (node (ref "U17") (pin "4") (pinfunction "_RST__4") (pintype "passive"))
    )
    (net (code "360") (name "unconnected-(U18A-PA3-Pad13)") (class "Default")
      (node (ref "U18") (pin "13") (pinfunction "PA3_13") (pintype "bidirectional"))
    )
    (net (code "361") (name "unconnected-(U18A-PA4-Pad14)") (class "Default")
      (node (ref "U18") (pin "14") (pinfunction "PA4_14") (pintype "bidirectional"))
    )
    (net (code "362") (name "unconnected-(U18A-PA6-Pad16)") (class "Default")
      (node (ref "U18") (pin "16") (pinfunction "PA6_16") (pintype "bidirectional"))
    )
    (net (code "363") (name "unconnected-(U18A-PA7-Pad17)") (class "Default")
      (node (ref "U18") (pin "17") (pinfunction "PA7_17") (pintype "bidirectional"))
    )
    (net (code "364") (name "unconnected-(U18A-PA8-Pad29)") (class "Default")
      (node (ref "U18") (pin "29") (pinfunction "PA8_29") (pintype "bidirectional"))
    )
    (net (code "365") (name "unconnected-(U18A-PA11-Pad32)") (class "Default")
      (node (ref "U18") (pin "32") (pinfunction "PA11_32") (pintype "bidirectional"))
    )
    (net (code "366") (name "unconnected-(U18A-PA12-Pad33)") (class "Default")
      (node (ref "U18") (pin "33") (pinfunction "PA12_33") (pintype "bidirectional"))
    )
    (net (code "367") (name "unconnected-(U18A-PA15-Pad38)") (class "Default")
      (node (ref "U18") (pin "38") (pinfunction "PA15_38") (pintype "bidirectional"))
    )
    (net (code "368") (name "unconnected-(U18A-PB0-Pad18)") (class "Default")
      (node (ref "U18") (pin "18") (pinfunction "PB0_18") (pintype "bidirectional"))
    )
    (net (code "369") (name "unconnected-(U18A-PB3-Pad39)") (class "Default")
      (node (ref "U18") (pin "39") (pinfunction "PB3_39") (pintype "bidirectional"))
    )
    (net (code "370") (name "unconnected-(U18A-PB4-Pad40)") (class "Default")
      (node (ref "U18") (pin "40") (pinfunction "PB4_40") (pintype "bidirectional"))
    )
    (net (code "371") (name "unconnected-(U18A-PB8-Pad45)") (class "Default")
      (node (ref "U18") (pin "45") (pinfunction "PB8_45") (pintype "bidirectional"))
    )
    (net (code "372") (name "unconnected-(U18A-PB9-Pad46)") (class "Default")
      (node (ref "U18") (pin "46") (pinfunction "PB9_46") (pintype "bidirectional"))
    )
    (net (code "373") (name "unconnected-(U18A-PB10-Pad21)") (class "Default")
      (node (ref "U18") (pin "21") (pinfunction "PB10_21") (pintype "bidirectional"))
    )
    (net (code "374") (name "unconnected-(U18A-PB11-Pad22)") (class "Default")
      (node (ref "U18") (pin "22") (pinfunction "PB11_22") (pintype "bidirectional"))
    )
    (net (code "375") (name "unconnected-(U18A-PB15-Pad28)") (class "Default")
      (node (ref "U18") (pin "28") (pinfunction "PB15_28") (pintype "bidirectional"))
    )
    (net (code "376") (name "unconnected-(U18A-PC13-TAMPER-RTC-Pad2)") (class "Default")
      (node (ref "U18") (pin "2") (pinfunction "PC13-TAMPER-RTC_2") (pintype "bidirectional"))
    )
    (net (code "377") (name "unconnected-(U18A-PC14-OSC32_IN-Pad3)") (class "Default")
      (node (ref "U18") (pin "3") (pinfunction "PC14-OSC32_IN_3") (pintype "bidirectional"))
    )
    (net (code "378") (name "unconnected-(U18A-PC15-OSC32_OUT-Pad4)") (class "Default")
      (node (ref "U18") (pin "4") (pinfunction "PC15-OSC32_OUT_4") (pintype "bidirectional"))
    )
    (net (code "379") (name "unconnected-(VL1-NC-Pad2)") (class "Default")
      (node (ref "VL1") (pin "2") (pinfunction "NC_2") (pintype "passive"))
    )
    (net (code "380") (name "unconnected-(VL1-NC-Pad3)") (class "Default")
      (node (ref "VL1") (pin "3") (pinfunction "NC_3") (pintype "passive"))
    )
    (net (code "381") (name "unconnected-(VL1-NC-Pad4)") (class "Default")
      (node (ref "VL1") (pin "4") (pinfunction "NC_4") (pintype "passive"))
    )
    (net (code "382") (name "unconnected-(VL1-NC-Pad5)") (class "Default")
      (node (ref "VL1") (pin "5") (pinfunction "NC_5") (pintype "passive"))
    )
    (net (code "383") (name "unconnected-(VL1-NC-Pad6)") (class "Default")
      (node (ref "VL1") (pin "6") (pinfunction "NC_6") (pintype "passive"))
    )
    (net (code "384") (name "unconnected-(VL1-NC-Pad7)") (class "Default")
      (node (ref "VL1") (pin "7") (pinfunction "NC_7") (pintype "passive"))
    )
    (net (code "385") (name "unconnected-(VL1-NC-Pad9)") (class "Default")
      (node (ref "VL1") (pin "9") (pinfunction "NC_9") (pintype "passive"))
    )
    (net (code "386") (name "unconnected-(VL1-NC-Pad11)") (class "Default")
      (node (ref "VL1") (pin "11") (pinfunction "NC_11") (pintype "passive"))
    )
    (net (code "387") (name "unconnected-(VL2-NC-Pad1)") (class "Default")
      (node (ref "VL2") (pin "1") (pinfunction "NC_1") (pintype "passive"))
    )
    (net (code "388") (name "unconnected-(VL2-NC-Pad8)") (class "Default")
      (node (ref "VL2") (pin "8") (pinfunction "NC_8") (pintype "passive"))
    )
    (net (code "389") (name "unconnected-(VL3-NC-Pad1)") (class "Default")
      (node (ref "VL3") (pin "1") (pinfunction "NC_1") (pintype "passive"))
    )
    (net (code "390") (name "unconnected-(VL3-NC-Pad8)") (class "Default")
      (node (ref "VL3") (pin "8") (pinfunction "NC_8") (pintype "passive"))
    )
    (net (code "391") (name "unconnected-(VL5-NC-Pad1)") (class "Default")
      (node (ref "VL5") (pin "1") (pinfunction "NC_1") (pintype "passive"))
    )
    (net (code "392") (name "unconnected-(VL5-NC-Pad8)") (class "Default")
      (node (ref "VL5") (pin "8") (pinfunction "NC_8") (pintype "passive"))
    )
    (net (code "393") (name "unconnected-(VL6-NC-Pad1)") (class "Default")
      (node (ref "VL6") (pin "1") (pinfunction "NC_1") (pintype "passive"))
    )
    (net (code "394") (name "unconnected-(VL6-NC-Pad8)") (class "Default")
      (node (ref "VL6") (pin "8") (pinfunction "NC_8") (pintype "passive"))
    )
    (net (code "395") (name "unconnected-(VL8-NC-Pad1)") (class "Default")
      (node (ref "VL8") (pin "1") (pinfunction "NC_1") (pintype "passive"))
    )
    (net (code "396") (name "unconnected-(VL8-NC-Pad8)") (class "Default")
      (node (ref "VL8") (pin "8") (pinfunction "NC_8") (pintype "passive"))
    )
    (net (code "397") (name "unconnected-(VL9-NC-Pad1)") (class "Default")
      (node (ref "VL9") (pin "1") (pinfunction "NC_1") (pintype "passive"))
    )
    (net (code "398") (name "unconnected-(VL9-NC-Pad8)") (class "Default")
      (node (ref "VL9") (pin "8") (pinfunction "NC_8") (pintype "passive"))
    )
  )
)
